# MotionDetectorCamera.net
KiCad netlist of a schematic drawn in EAGLE
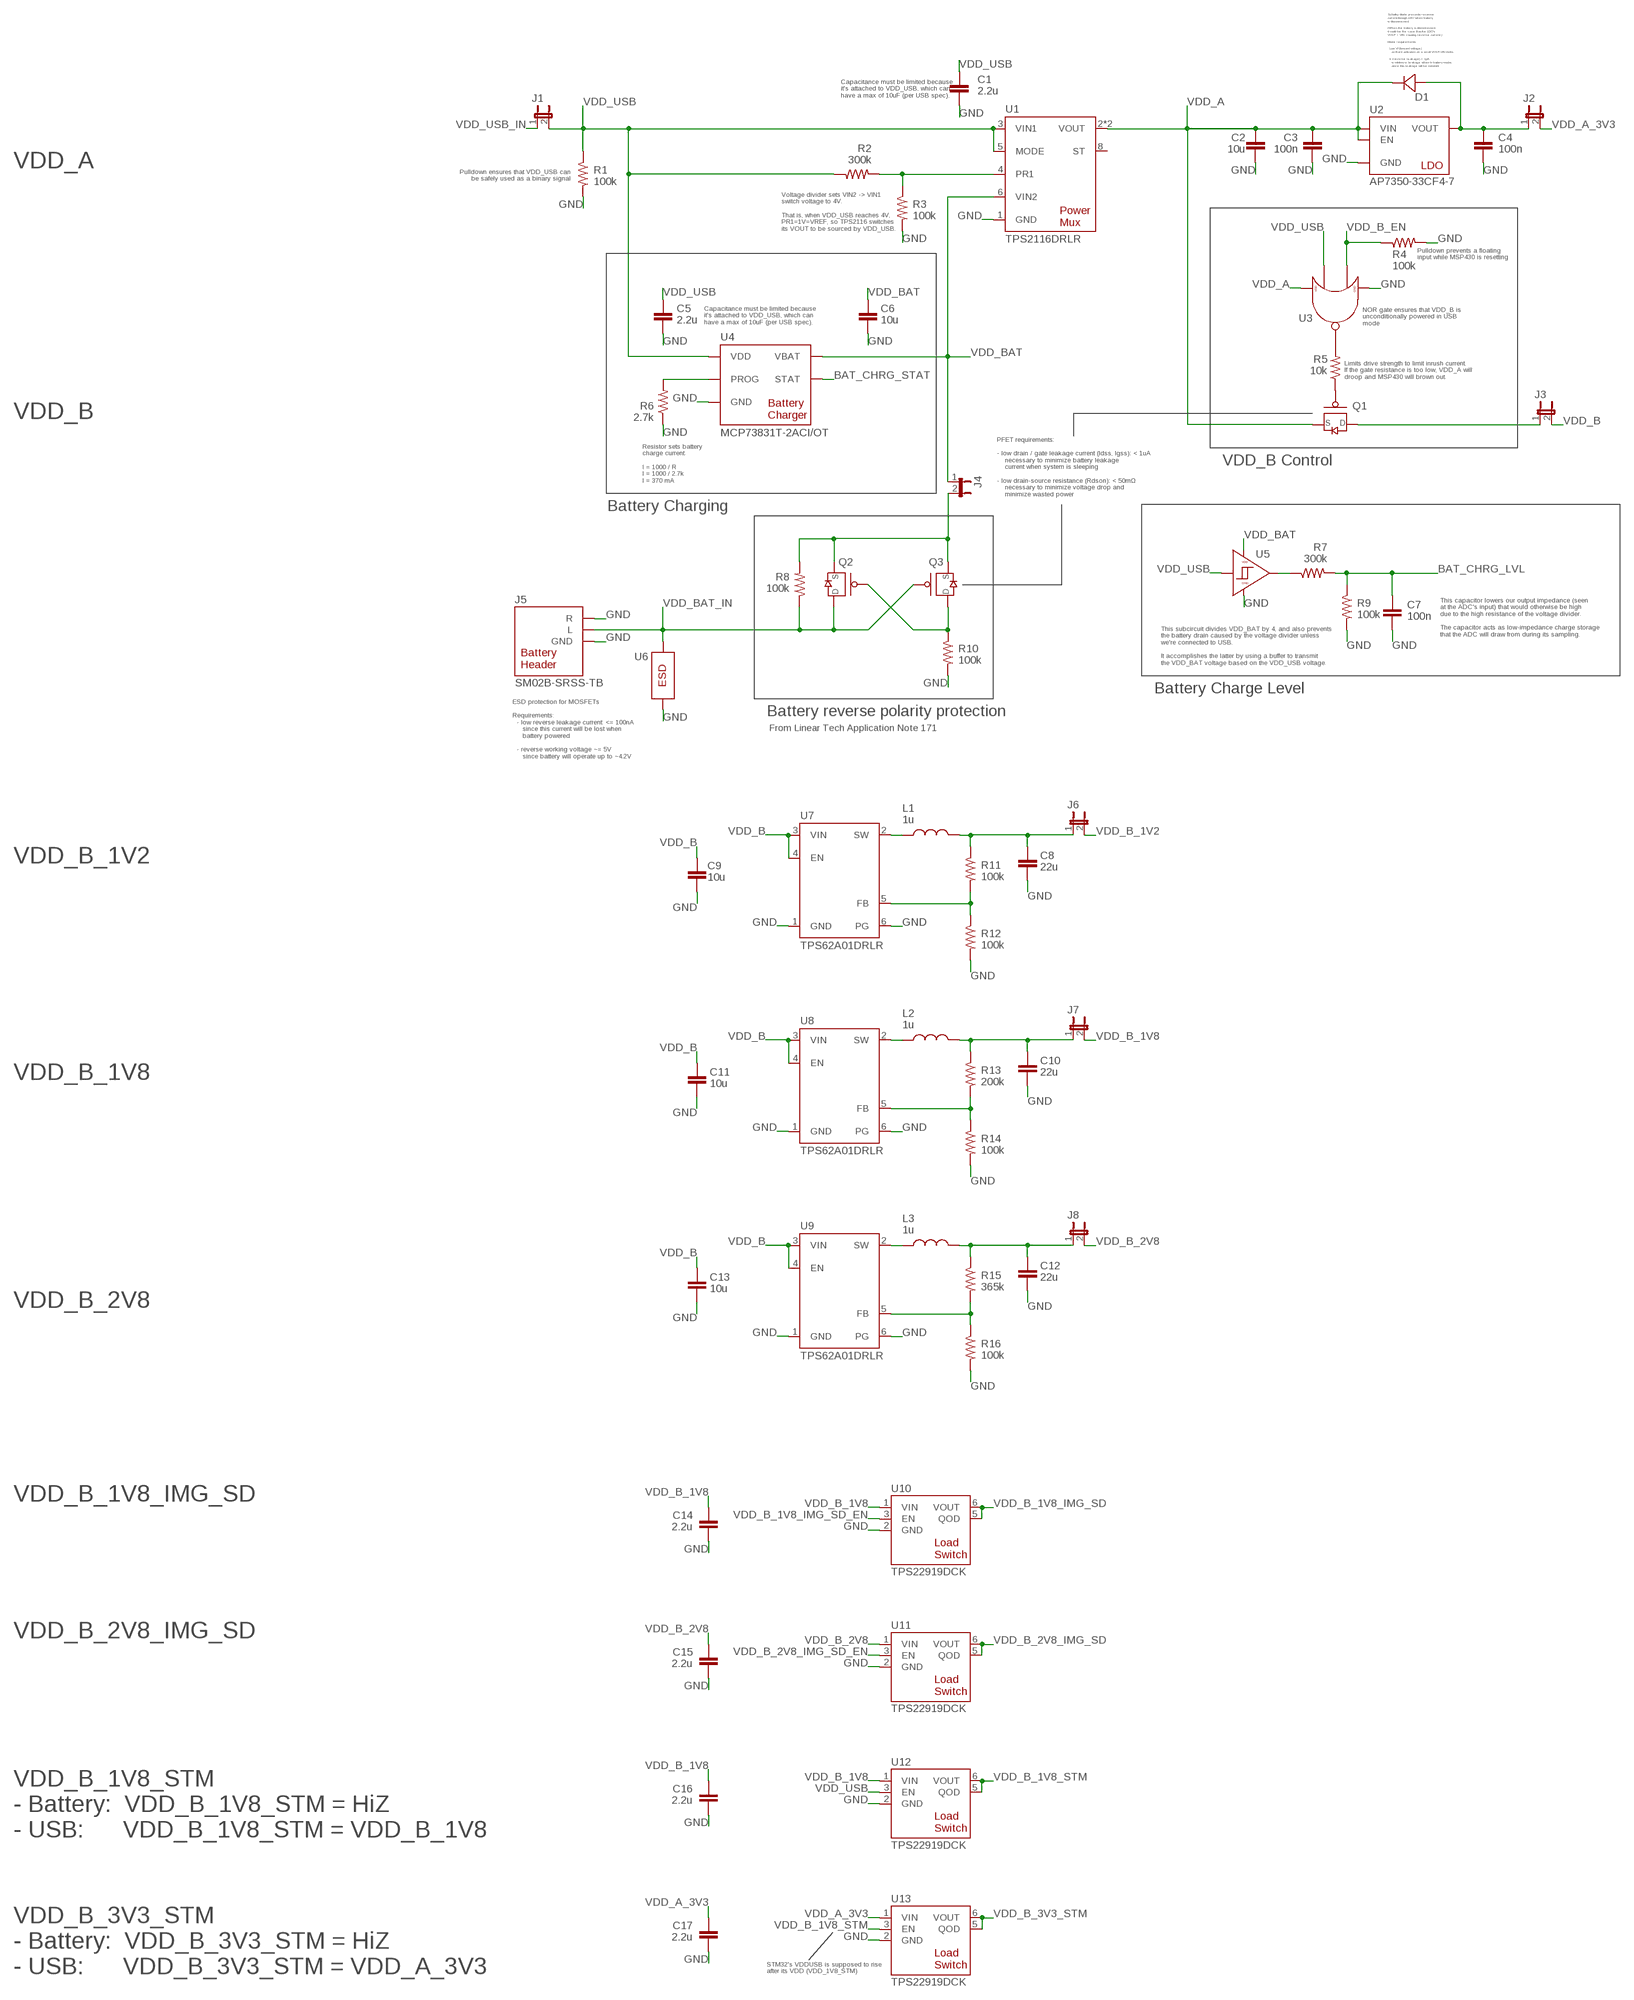
[diagram p0: schematic, sheet 1]
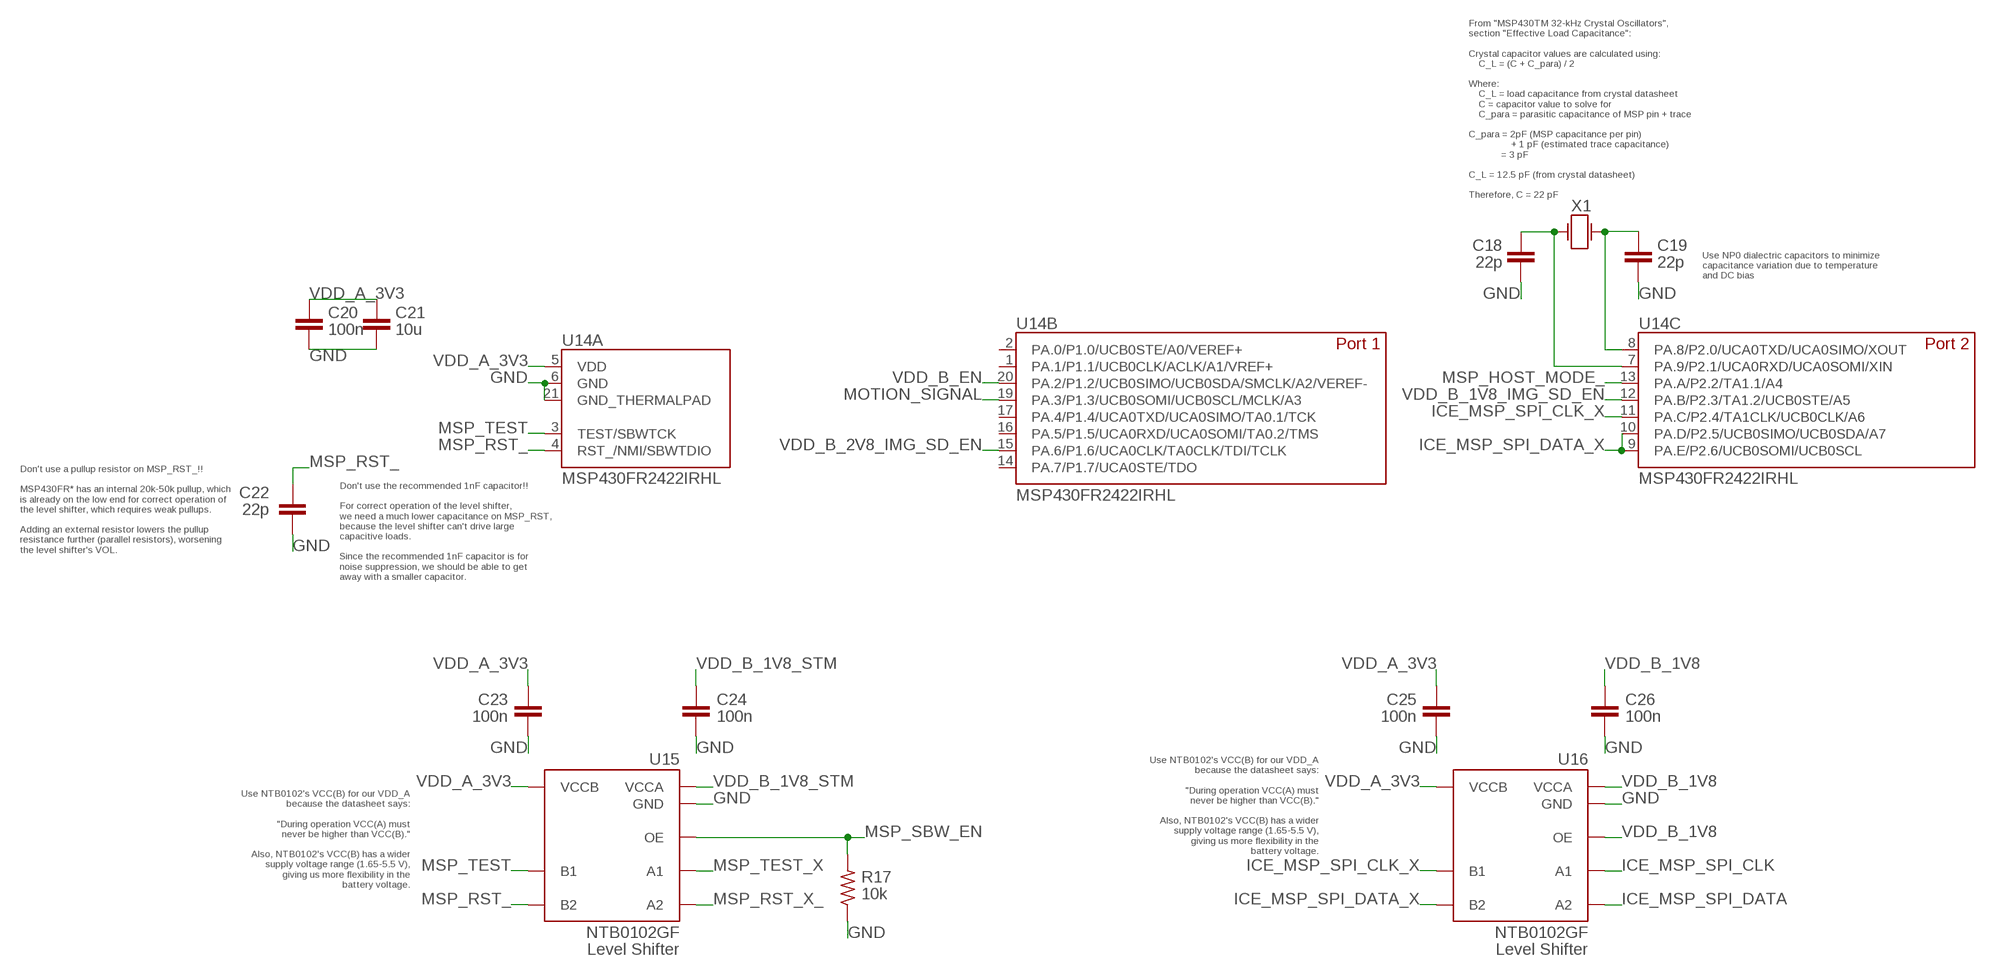
[diagram p1: schematic, sheet 2]
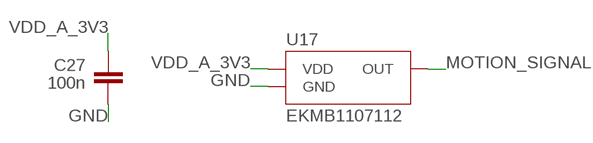
[diagram p2: schematic, sheet 3]
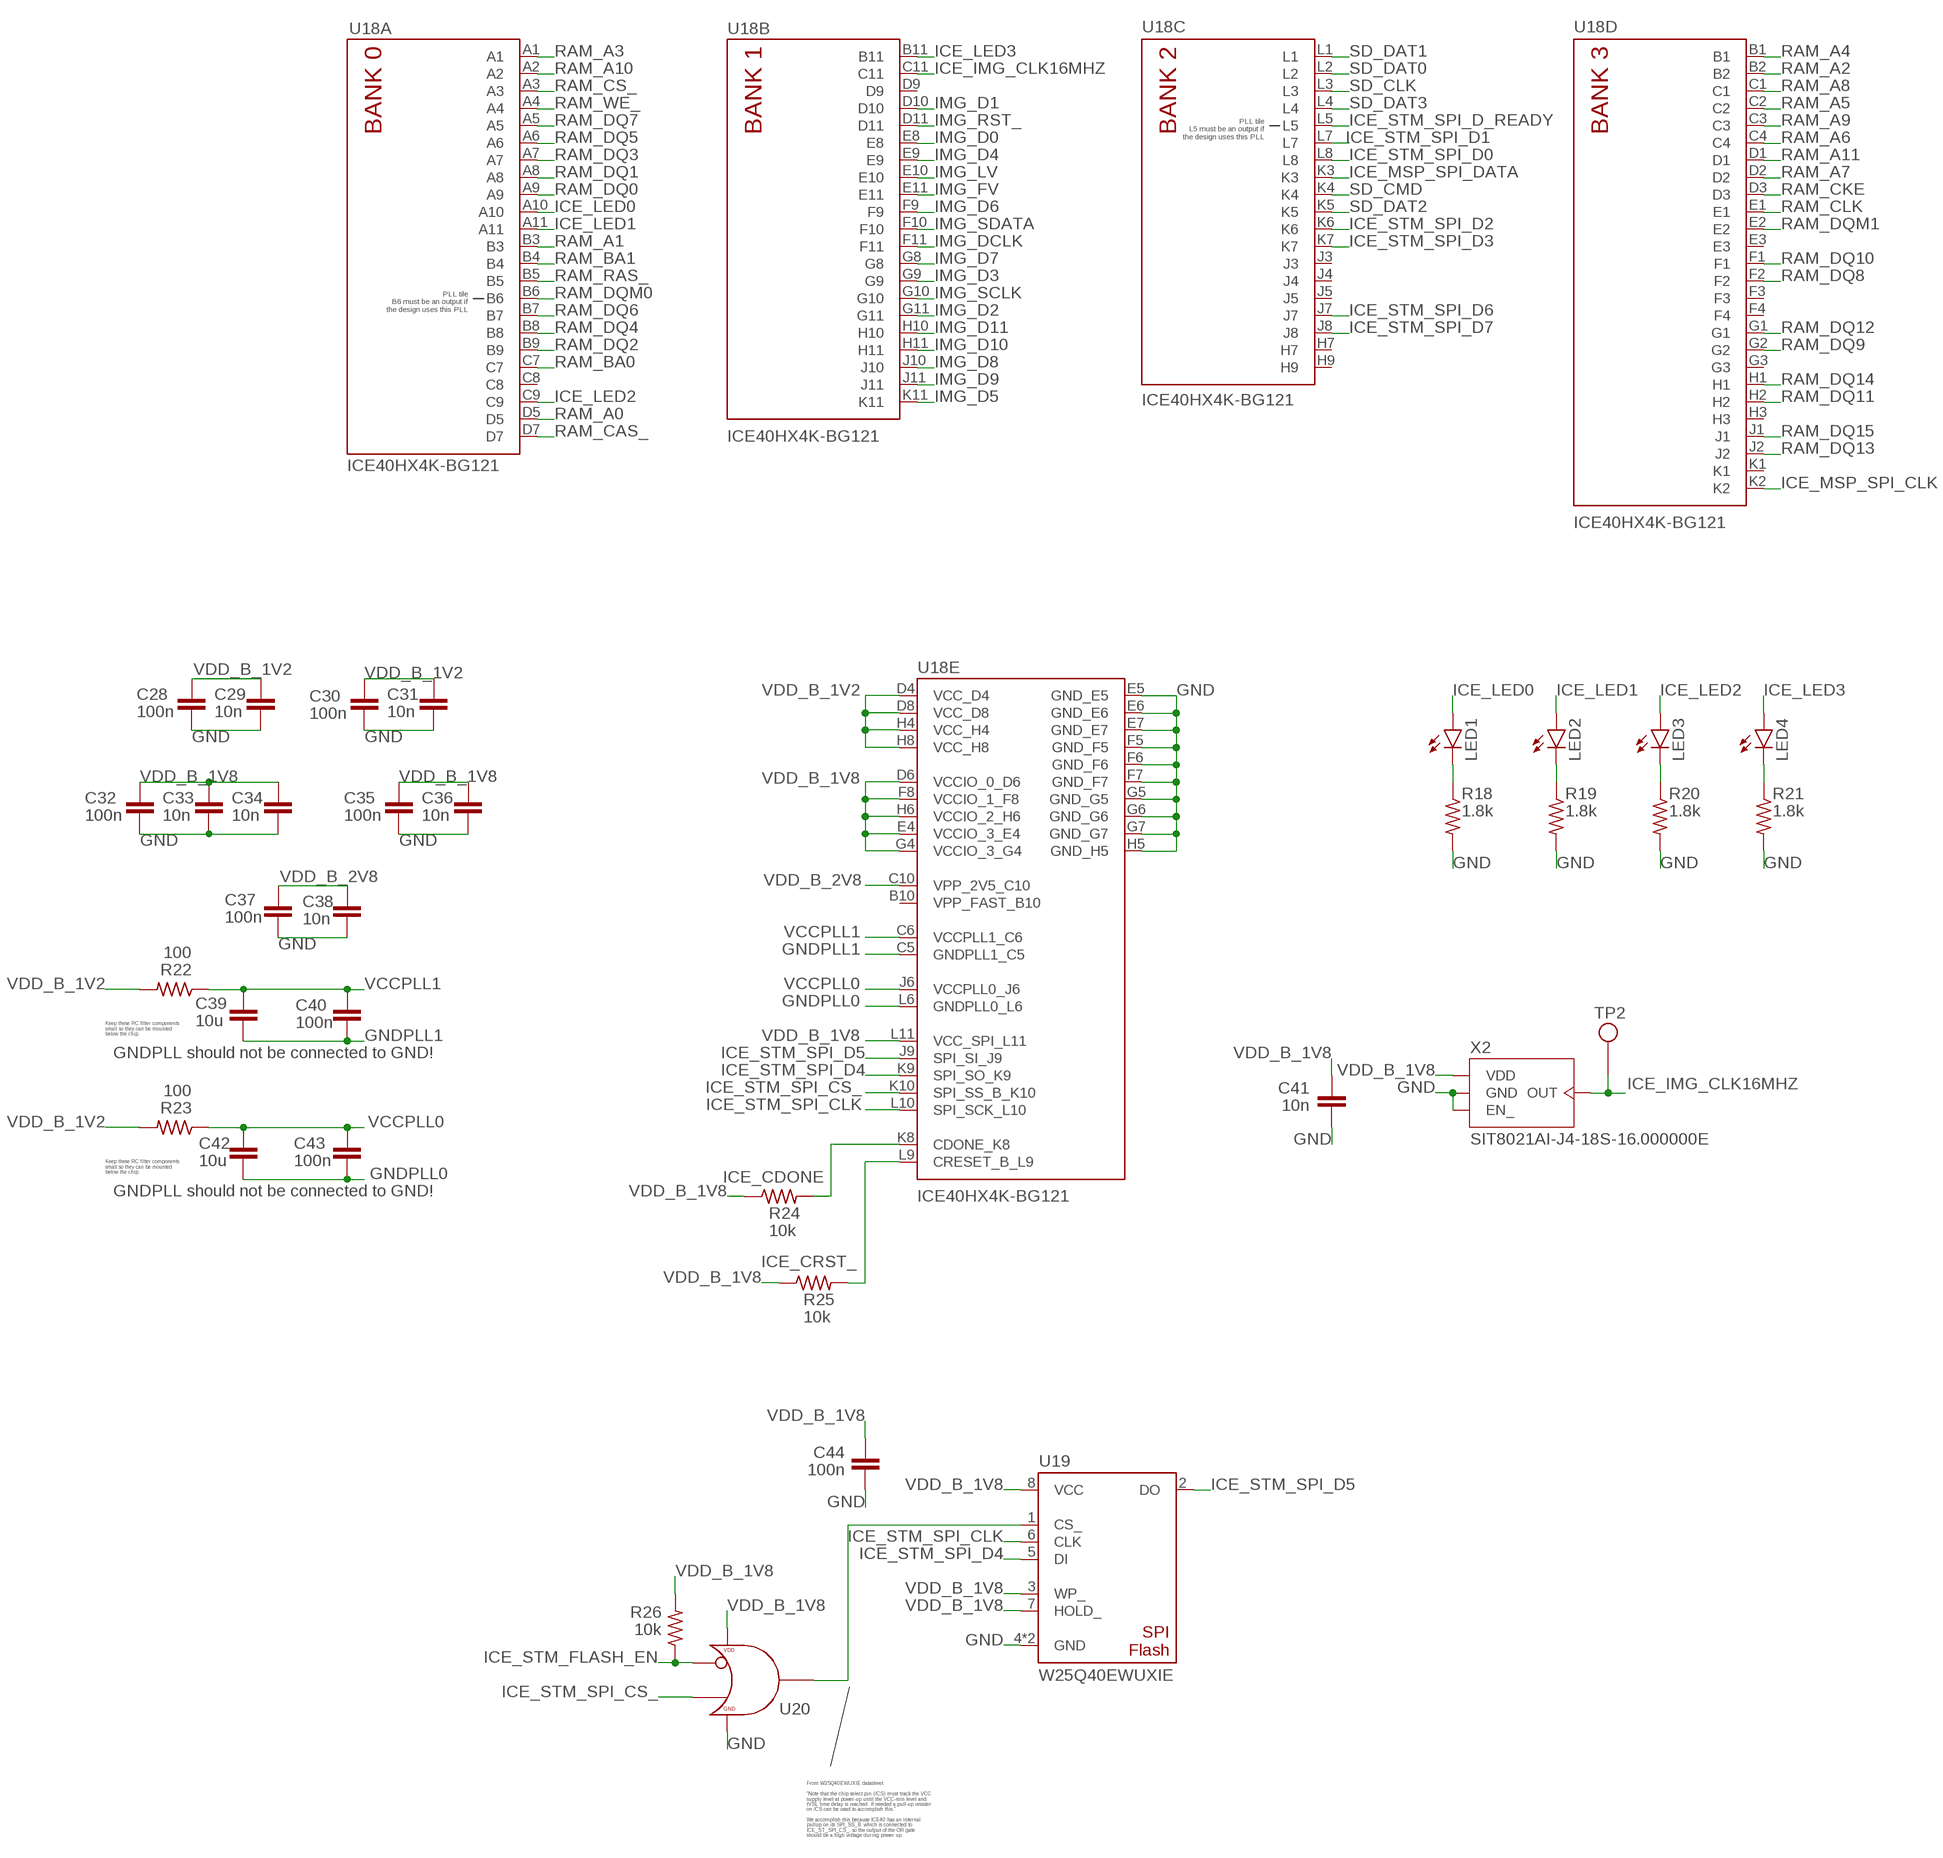
[diagram p3: schematic, sheet 4]
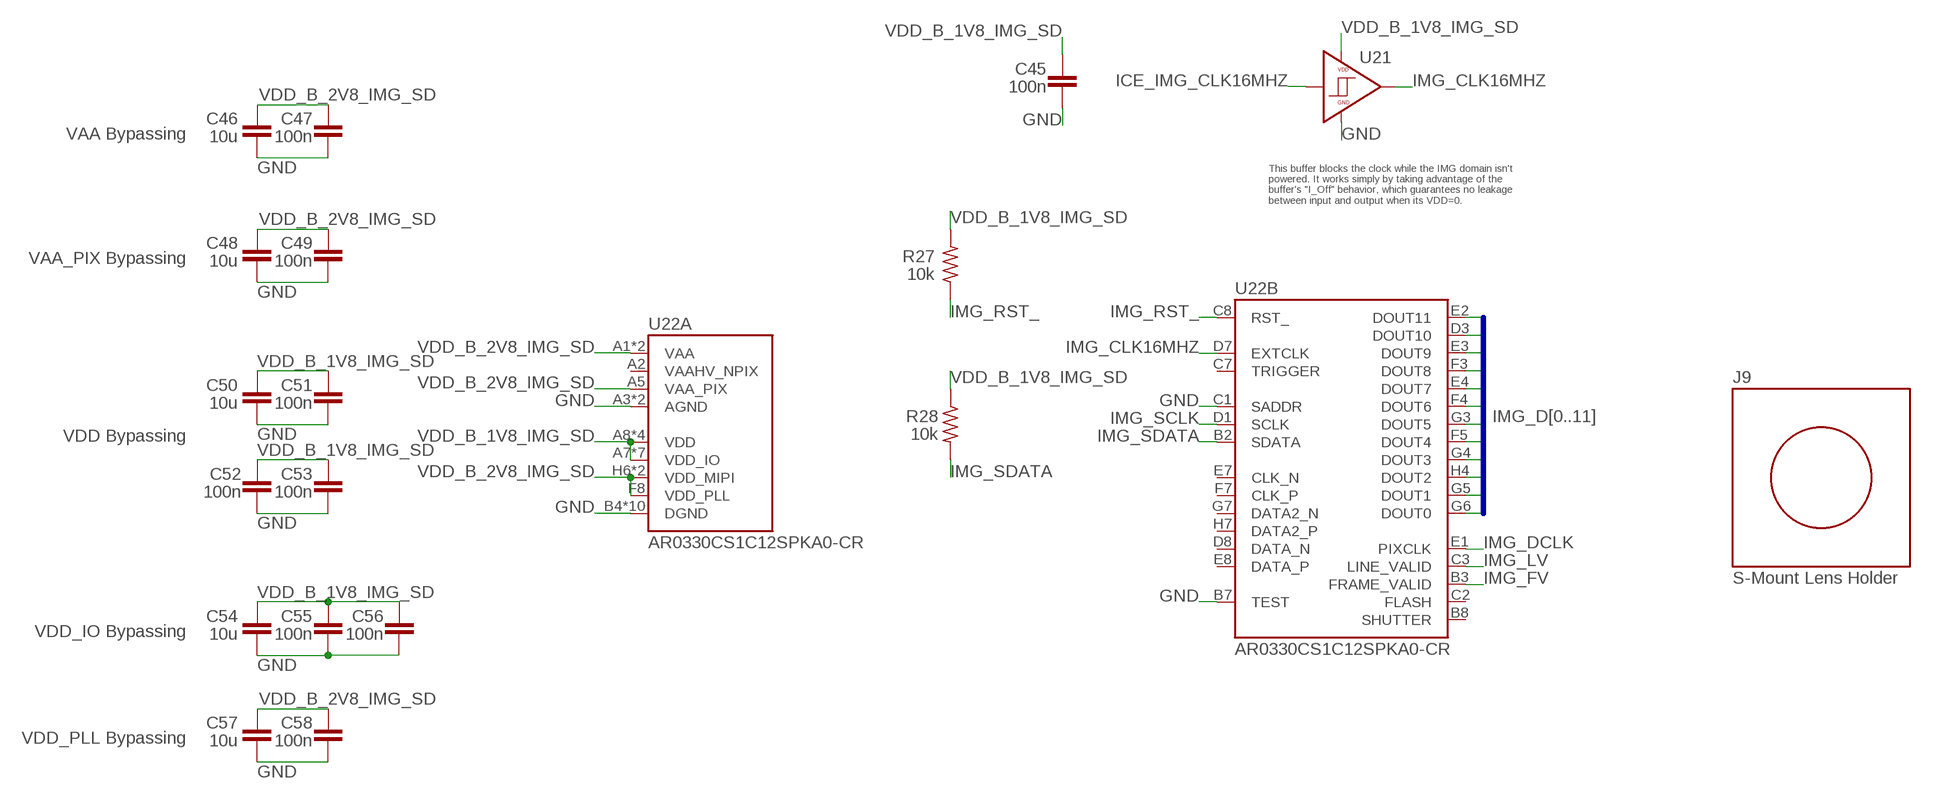
[diagram p4: schematic, sheet 5]
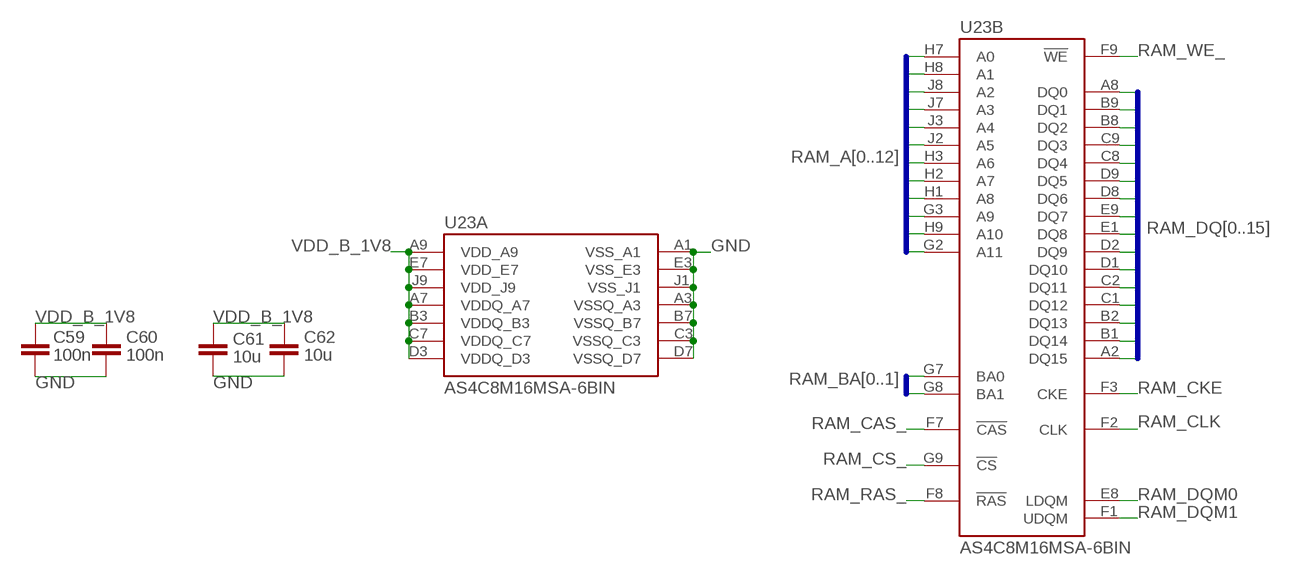
[diagram p5: schematic, sheet 6]
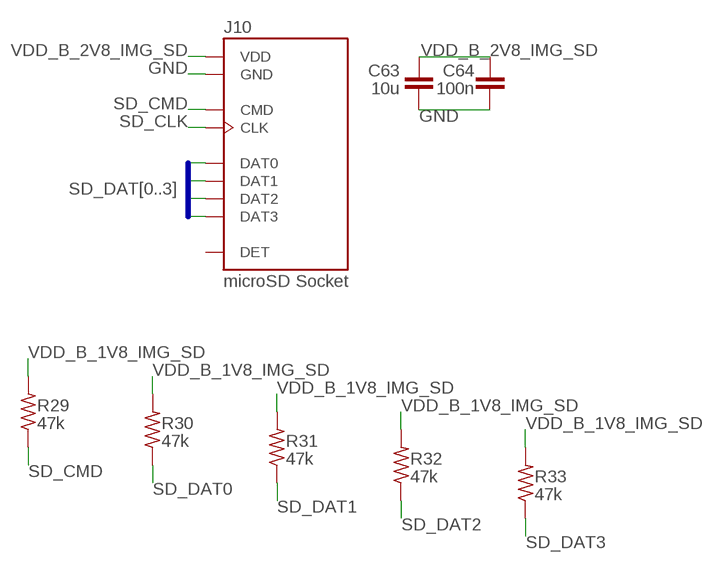
[diagram p6: schematic, sheet 7]
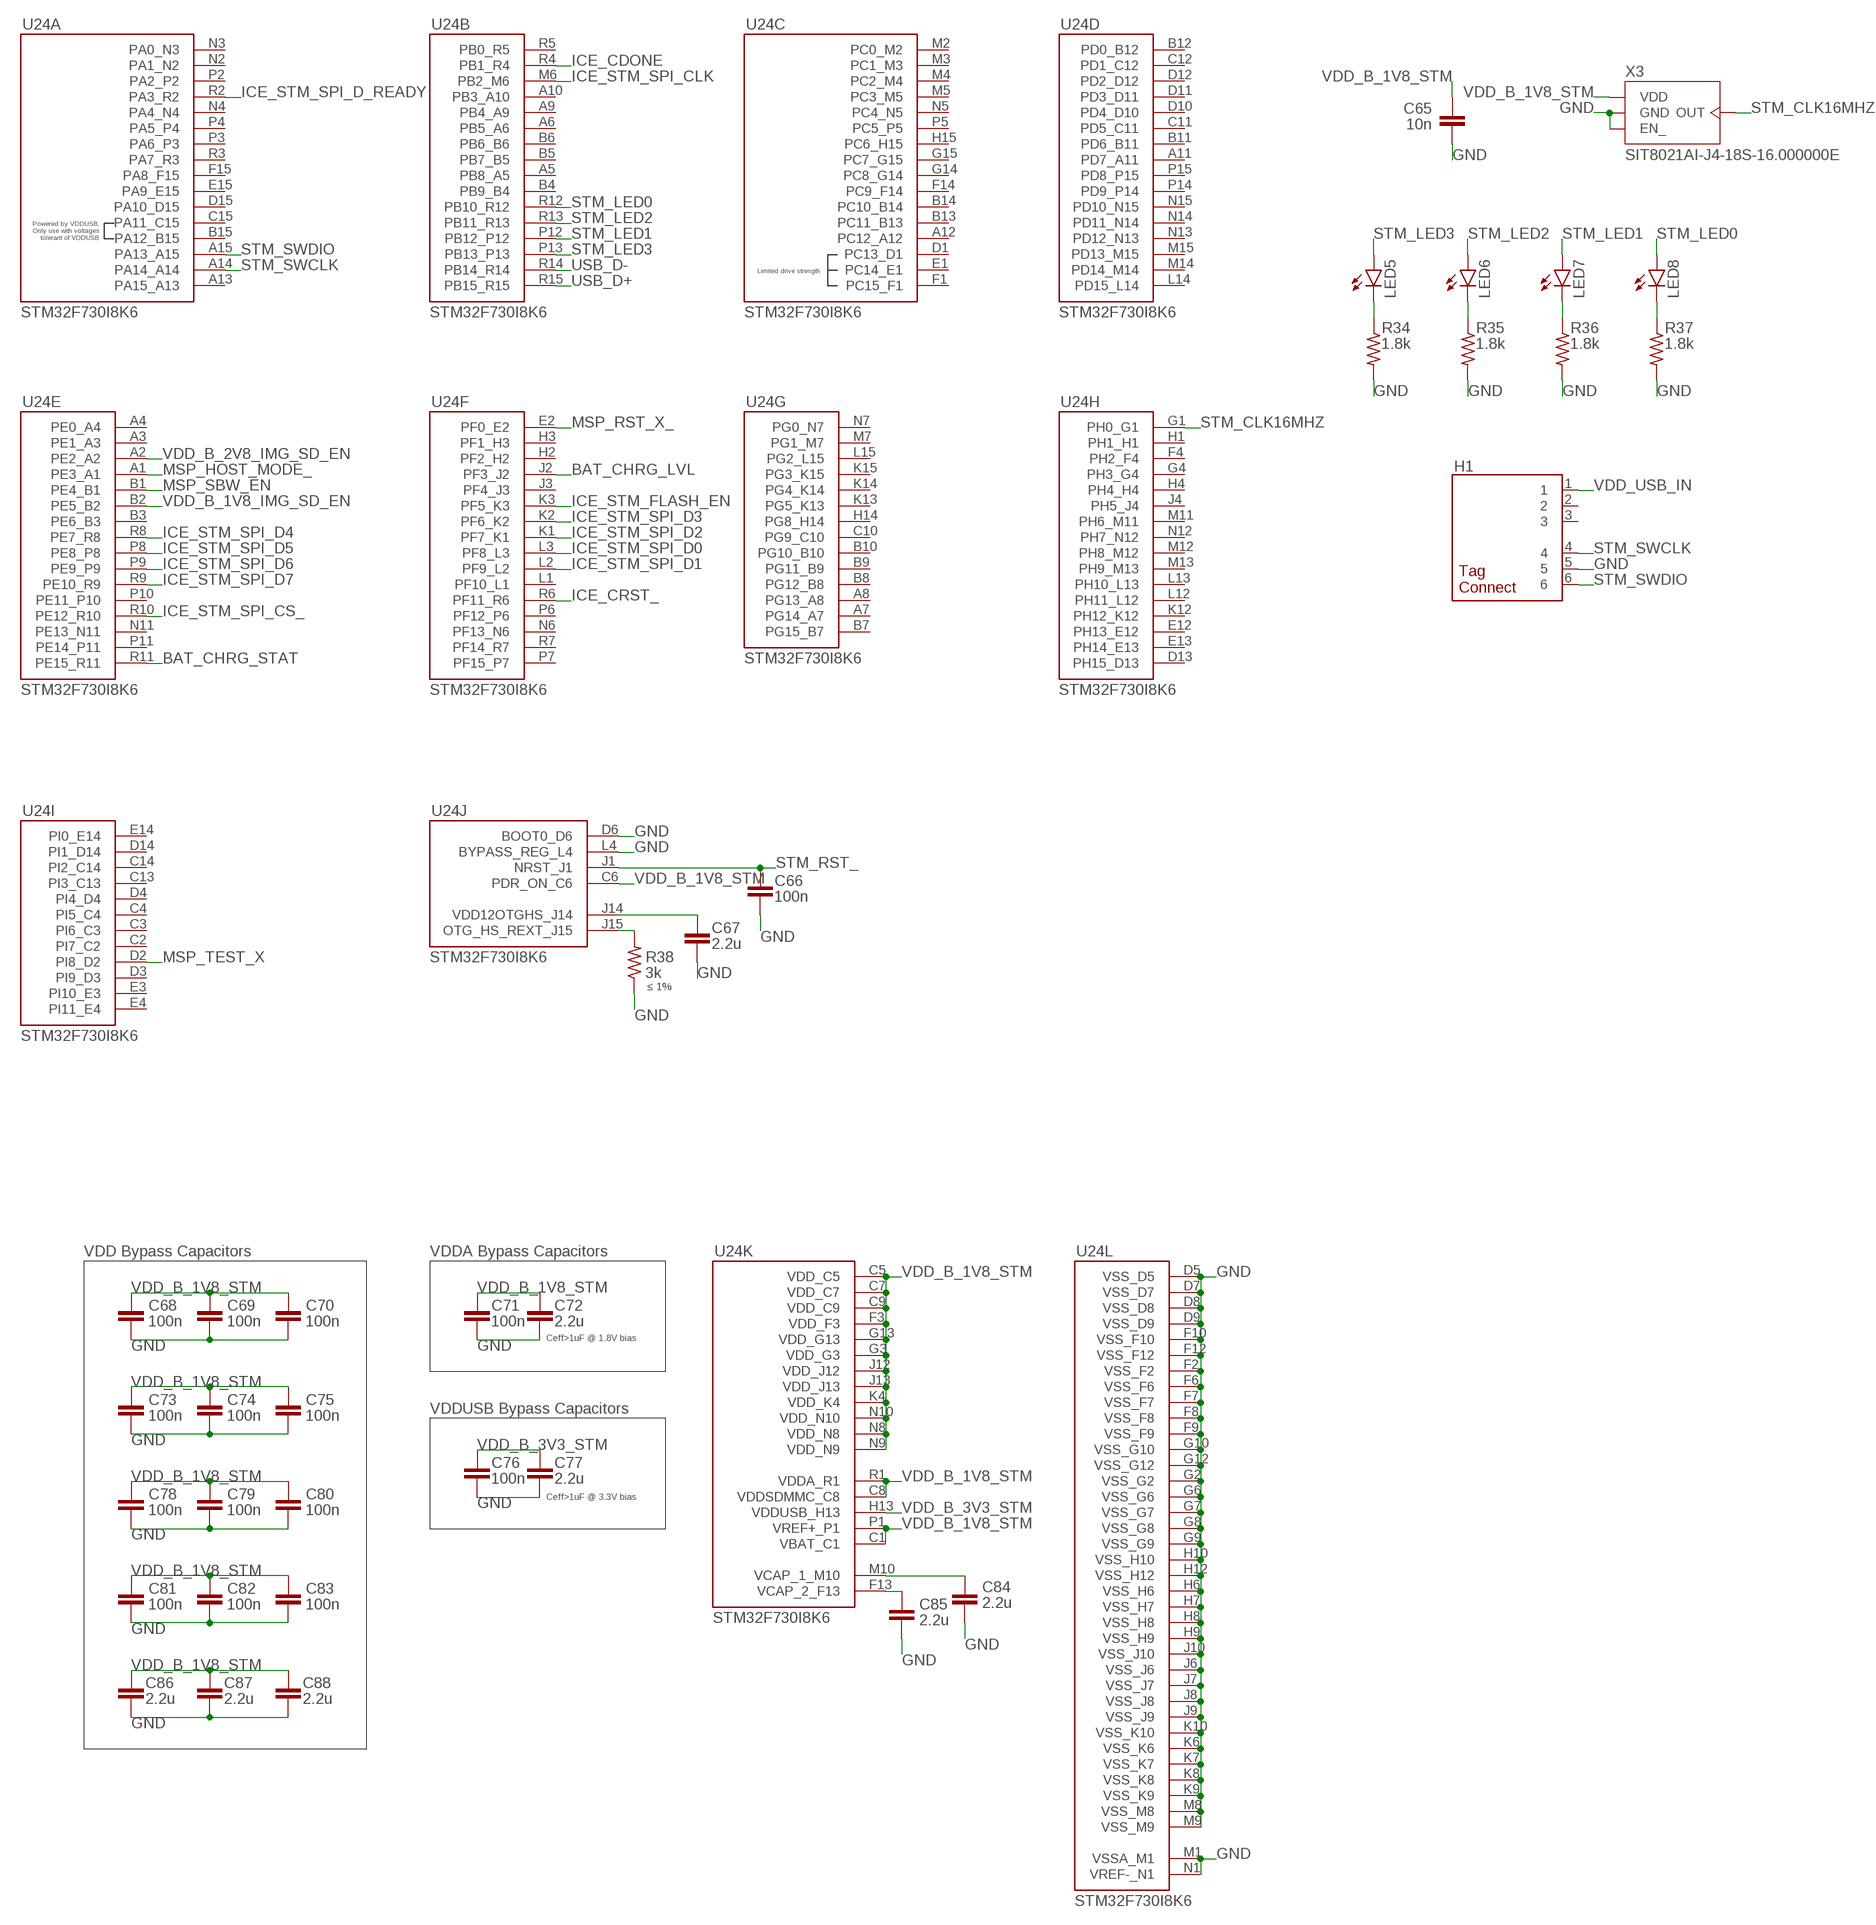
[diagram p7: schematic, sheet 8]
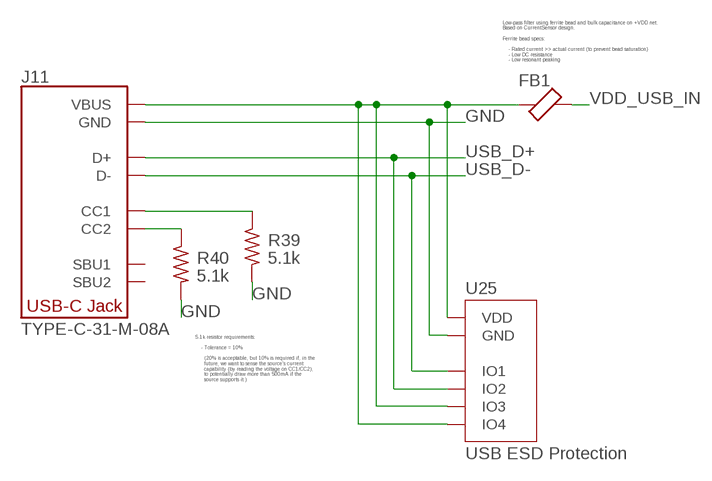
[diagram p8: schematic, sheet 9]

(export (version "E")
  (design (tool "Eeschema 10.0.6"))
  (components
    (comp (ref "C28")
      (value "100n")
      (footprint "eagle-import:0402")
      (fields (field (name "MFG") "Murata"))
      (libsource (lib "eagle-import") (part "CAPACITOR0402"))
    )
    (comp (ref "C29")
      (value "10n")
      (footprint "eagle-import:0402")
      (fields (field (name "MFG") "Samsung"))
      (libsource (lib "eagle-import") (part "CAPACITOR0402"))
    )
    (comp (ref "C30")
      (value "100n")
      (footprint "eagle-import:0402")
      (fields (field (name "MFG") "Murata"))
      (libsource (lib "eagle-import") (part "CAPACITOR0402"))
    )
    (comp (ref "C31")
      (value "10n")
      (footprint "eagle-import:0402")
      (fields (field (name "MFG") "Samsung"))
      (libsource (lib "eagle-import") (part "CAPACITOR0402"))
    )
    (comp (ref "C32")
      (value "100n")
      (footprint "eagle-import:0402")
      (fields (field (name "MFG") "Murata"))
      (libsource (lib "eagle-import") (part "CAPACITOR0402"))
    )
    (comp (ref "C33")
      (value "10n")
      (footprint "eagle-import:0402")
      (fields (field (name "MFG") "Samsung"))
      (libsource (lib "eagle-import") (part "CAPACITOR0402"))
    )
    (comp (ref "C34")
      (value "10n")
      (footprint "eagle-import:0402")
      (fields (field (name "MFG") "Samsung"))
      (libsource (lib "eagle-import") (part "CAPACITOR0402"))
    )
    (comp (ref "C35")
      (value "100n")
      (footprint "eagle-import:0402")
      (fields (field (name "MFG") "Murata"))
      (libsource (lib "eagle-import") (part "CAPACITOR0402"))
    )
    (comp (ref "C36")
      (value "10n")
      (footprint "eagle-import:0402")
      (fields (field (name "MFG") "Samsung"))
      (libsource (lib "eagle-import") (part "CAPACITOR0402"))
    )
    (comp (ref "C37")
      (value "100n")
      (footprint "eagle-import:0402")
      (fields (field (name "MFG") "Murata"))
      (libsource (lib "eagle-import") (part "CAPACITOR0402"))
    )
    (comp (ref "C38")
      (value "10n")
      (footprint "eagle-import:0402")
      (fields (field (name "MFG") "Samsung"))
      (libsource (lib "eagle-import") (part "CAPACITOR0402"))
    )
    (comp (ref "C39")
      (value "10u")
      (footprint "eagle-import:0805")
      (fields (field (name "MFG") "Samsung"))
      (libsource (lib "eagle-import") (part "CAPACITOR0805"))
    )
    (comp (ref "C40")
      (value "100n")
      (footprint "eagle-import:0402")
      (fields (field (name "MFG") "Murata"))
      (libsource (lib "eagle-import") (part "CAPACITOR0402"))
    )
    (comp (ref "C41")
      (value "10n")
      (footprint "eagle-import:0402")
      (fields (field (name "MFG") "Samsung"))
      (libsource (lib "eagle-import") (part "CAPACITOR0402"))
    )
    (comp (ref "C42")
      (value "10u")
      (footprint "eagle-import:0805")
      (fields (field (name "MFG") "Samsung"))
      (libsource (lib "eagle-import") (part "CAPACITOR0805"))
    )
    (comp (ref "C43")
      (value "100n")
      (footprint "eagle-import:0402")
      (fields (field (name "MFG") "Murata"))
      (libsource (lib "eagle-import") (part "CAPACITOR0402"))
    )
    (comp (ref "C44")
      (value "100n")
      (footprint "eagle-import:0402")
      (fields (field (name "MFG") "Murata"))
      (libsource (lib "eagle-import") (part "CAPACITOR0402"))
    )
    (comp (ref "LED1")
      (value "LED")
      (footprint "eagle-import:LED-0603")
      (fields (field (name "MFG") "OSRAM"))
      (libsource (lib "eagle-import") (part "LED"))
    )
    (comp (ref "LED2")
      (value "LED")
      (footprint "eagle-import:LED-0603")
      (fields (field (name "MFG") "OSRAM"))
      (libsource (lib "eagle-import") (part "LED"))
    )
    (comp (ref "LED3")
      (value "LED")
      (footprint "eagle-import:LED-0603")
      (fields (field (name "MFG") "OSRAM"))
      (libsource (lib "eagle-import") (part "LED"))
    )
    (comp (ref "LED4")
      (value "LED")
      (footprint "eagle-import:LED-0603")
      (fields (field (name "MFG") "OSRAM"))
      (libsource (lib "eagle-import") (part "LED"))
    )
    (comp (ref "R18")
      (value "1.8k")
      (footprint "eagle-import:0402")
      (fields (field (name "MFG") "Yageo"))
      (libsource (lib "eagle-import") (part "RESISTOR0402"))
    )
    (comp (ref "R19")
      (value "1.8k")
      (footprint "eagle-import:0402")
      (fields (field (name "MFG") "Yageo"))
      (libsource (lib "eagle-import") (part "RESISTOR0402"))
    )
    (comp (ref "R20")
      (value "1.8k")
      (footprint "eagle-import:0402")
      (fields (field (name "MFG") "Yageo"))
      (libsource (lib "eagle-import") (part "RESISTOR0402"))
    )
    (comp (ref "R21")
      (value "1.8k")
      (footprint "eagle-import:0402")
      (fields (field (name "MFG") "Yageo"))
      (libsource (lib "eagle-import") (part "RESISTOR0402"))
    )
    (comp (ref "R22")
      (value "100")
      (footprint "eagle-import:0402")
      (fields (field (name "MFG") "Walsin"))
      (libsource (lib "eagle-import") (part "RESISTOR0402"))
    )
    (comp (ref "R23")
      (value "100")
      (footprint "eagle-import:0402")
      (fields (field (name "MFG") "Walsin"))
      (libsource (lib "eagle-import") (part "RESISTOR0402"))
    )
    (comp (ref "R24")
      (value "10k")
      (footprint "eagle-import:0402")
      (fields (field (name "MFG") "Yageo"))
      (libsource (lib "eagle-import") (part "RESISTOR0402"))
    )
    (comp (ref "R25")
      (value "10k")
      (footprint "eagle-import:0402")
      (fields (field (name "MFG") "Yageo"))
      (libsource (lib "eagle-import") (part "RESISTOR0402"))
    )
    (comp (ref "R26")
      (value "10k")
      (footprint "eagle-import:0402")
      (fields (field (name "MFG") "Yageo"))
      (libsource (lib "eagle-import") (part "RESISTOR0402"))
    )
    (comp (ref "TP2")
      (value "TEST-POINT")
      (footprint "eagle-import:TEST-POINT")
      (libsource (lib "eagle-import") (part "TEST-POINT"))
    )
    (comp (ref "U18")
      (value "LATTICE-ICE40HX4K-BG121")
      (footprint "eagle-import:LATTICE-ICE40HX4K-BG121")
      (fields (field (name "MFG") "Lattice"))
      (libsource (lib "eagle-import") (part "LATTICE-ICE40HX4K-BG121"))
    )
    (comp (ref "U19")
      (value "WINBOND-W25Q40EW")
      (footprint "eagle-import:WINBOND-W25Q40EWUXIE")
      (fields (field (name "MFG") "Winbond") (field (name "PN") "W25Q40EWUXIE"))
      (libsource (lib "eagle-import") (part "WINBOND-W25Q40EW"))
    )
    (comp (ref "U20")
      (value "NEXPERIA-74LVC1G98-OR-INV-INPUT")
      (footprint "eagle-import:NEXPERIA-SOT363")
      (fields (field (name "MFG") "Nexperia"))
      (libsource (lib "eagle-import") (part "NEXPERIA-74LVC1G98-OR-INV-INPUT"))
    )
    (comp (ref "X2")
      (value "SITIME-SIT8021")
      (footprint "eagle-import:SITIME-SIT8021")
      (fields (field (name "MFG") "SiTime") (field (name "PN") "SIT8021AI-J4-18S-16.000000E"))
      (libsource (lib "eagle-import") (part "SITIME-SIT8021"))
    )
    (comp (ref "C59")
      (value "100n")
      (footprint "eagle-import:0402")
      (fields (field (name "MFG") "Murata"))
      (libsource (lib "eagle-import") (part "CAPACITOR0402"))
    )
    (comp (ref "C60")
      (value "100n")
      (footprint "eagle-import:0402")
      (fields (field (name "MFG") "Murata"))
      (libsource (lib "eagle-import") (part "CAPACITOR0402"))
    )
    (comp (ref "C61")
      (value "10u")
      (footprint "eagle-import:0805")
      (fields (field (name "MFG") "Samsung"))
      (libsource (lib "eagle-import") (part "CAPACITOR0805"))
    )
    (comp (ref "C62")
      (value "10u")
      (footprint "eagle-import:0805")
      (fields (field (name "MFG") "Samsung"))
      (libsource (lib "eagle-import") (part "CAPACITOR0805"))
    )
    (comp (ref "U23")
      (value "ALLIANCE-AS4C8M16MSA-6BIN")
      (footprint "eagle-import:ALLIANCE-AS4C8M16MSA-6BIN")
      (fields (field (name "PN") "AS4C8M16MSA-6BIN") (field (name "MFG") "Alliance Memory"))
      (libsource (lib "eagle-import") (part "ALLIANCE-AS4C8M16MSA-6BIN"))
    )
    (comp (ref "C1")
      (value "2.2u")
      (footprint "eagle-import:0402")
      (fields (field (name "MFG") "Taiyo Yuden"))
      (libsource (lib "eagle-import") (part "CAPACITOR0402"))
    )
    (comp (ref "C2")
      (value "10u")
      (footprint "eagle-import:0805")
      (fields (field (name "MFG") "Samsung"))
      (libsource (lib "eagle-import") (part "CAPACITOR0805"))
    )
    (comp (ref "C3")
      (value "100n")
      (footprint "eagle-import:0402")
      (fields (field (name "MFG") "Murata"))
      (libsource (lib "eagle-import") (part "CAPACITOR0402"))
    )
    (comp (ref "C4")
      (value "100n")
      (footprint "eagle-import:0402")
      (fields (field (name "MFG") "Murata"))
      (libsource (lib "eagle-import") (part "CAPACITOR0402"))
    )
    (comp (ref "C5")
      (value "2.2u")
      (footprint "eagle-import:0402")
      (fields (field (name "MFG") "Taiyo Yuden"))
      (libsource (lib "eagle-import") (part "CAPACITOR0402"))
    )
    (comp (ref "C6")
      (value "10u")
      (footprint "eagle-import:0805")
      (fields (field (name "MFG") "Samsung"))
      (libsource (lib "eagle-import") (part "CAPACITOR0805"))
    )
    (comp (ref "C7")
      (value "100n")
      (footprint "eagle-import:0402")
      (fields (field (name "MFG") "Murata"))
      (libsource (lib "eagle-import") (part "CAPACITOR0402"))
    )
    (comp (ref "C8")
      (value "22u")
      (footprint "eagle-import:0805")
      (fields (field (name "MFG") "Samsung"))
      (libsource (lib "eagle-import") (part "CAPACITOR0805"))
    )
    (comp (ref "C9")
      (value "10u")
      (footprint "eagle-import:0805")
      (fields (field (name "MFG") "Samsung"))
      (libsource (lib "eagle-import") (part "CAPACITOR0805"))
    )
    (comp (ref "C10")
      (value "22u")
      (footprint "eagle-import:0805")
      (fields (field (name "MFG") "Samsung"))
      (libsource (lib "eagle-import") (part "CAPACITOR0805"))
    )
    (comp (ref "C11")
      (value "10u")
      (footprint "eagle-import:0805")
      (fields (field (name "MFG") "Samsung"))
      (libsource (lib "eagle-import") (part "CAPACITOR0805"))
    )
    (comp (ref "C12")
      (value "22u")
      (footprint "eagle-import:0805")
      (fields (field (name "MFG") "Samsung"))
      (libsource (lib "eagle-import") (part "CAPACITOR0805"))
    )
    (comp (ref "C13")
      (value "10u")
      (footprint "eagle-import:0805")
      (fields (field (name "MFG") "Samsung"))
      (libsource (lib "eagle-import") (part "CAPACITOR0805"))
    )
    (comp (ref "C14")
      (value "2.2u")
      (footprint "eagle-import:0402")
      (fields (field (name "MFG") "Taiyo Yuden"))
      (libsource (lib "eagle-import") (part "CAPACITOR0402"))
    )
    (comp (ref "C15")
      (value "2.2u")
      (footprint "eagle-import:0402")
      (fields (field (name "MFG") "Taiyo Yuden"))
      (libsource (lib "eagle-import") (part "CAPACITOR0402"))
    )
    (comp (ref "C16")
      (value "2.2u")
      (footprint "eagle-import:0402")
      (fields (field (name "MFG") "Taiyo Yuden"))
      (libsource (lib "eagle-import") (part "CAPACITOR0402"))
    )
    (comp (ref "C17")
      (value "2.2u")
      (footprint "eagle-import:0402")
      (fields (field (name "MFG") "Taiyo Yuden"))
      (libsource (lib "eagle-import") (part "CAPACITOR0402"))
    )
    (comp (ref "D1")
      (value "ROHM-RB168MM-40")
      (footprint "eagle-import:ROHM-SOD-123FL")
      (fields (field (name "MFG") "ROHM"))
      (libsource (lib "eagle-import") (part "ROHM-RB168MM-40"))
    )
    (comp (ref "J1")
      (value "JUMPER-SOLDER")
      (footprint "eagle-import:JUMPER-SOLDER")
      (libsource (lib "eagle-import") (part "JUMPER-SOLDER"))
    )
    (comp (ref "J2")
      (value "JUMPER-SOLDER")
      (footprint "eagle-import:JUMPER-SOLDER")
      (libsource (lib "eagle-import") (part "JUMPER-SOLDER"))
    )
    (comp (ref "J3")
      (value "JUMPER-SOLDER")
      (footprint "eagle-import:JUMPER-SOLDER")
      (libsource (lib "eagle-import") (part "JUMPER-SOLDER"))
    )
    (comp (ref "J4")
      (value "JUMPER-SOLDER")
      (footprint "eagle-import:JUMPER-SOLDER")
      (libsource (lib "eagle-import") (part "JUMPER-SOLDER"))
    )
    (comp (ref "J5")
      (value "JST-SM02B-SRSS-TB")
      (footprint "eagle-import:JST-SM02B-SRSS-TB")
      (fields (field (name "PN") "SM02B-SRSS-TB") (field (name "MFG") "JST"))
      (libsource (lib "eagle-import") (part "JST-SM02B-SRSS-TB"))
    )
    (comp (ref "J6")
      (value "JUMPER-SOLDER")
      (footprint "eagle-import:JUMPER-SOLDER")
      (libsource (lib "eagle-import") (part "JUMPER-SOLDER"))
    )
    (comp (ref "J7")
      (value "JUMPER-SOLDER")
      (footprint "eagle-import:JUMPER-SOLDER")
      (libsource (lib "eagle-import") (part "JUMPER-SOLDER"))
    )
    (comp (ref "J8")
      (value "JUMPER-SOLDER")
      (footprint "eagle-import:JUMPER-SOLDER")
      (libsource (lib "eagle-import") (part "JUMPER-SOLDER"))
    )
    (comp (ref "L1")
      (value "1u")
      (footprint "eagle-import:0806")
      (fields (field (name "MFG") "Samsung"))
      (libsource (lib "eagle-import") (part "INDUCTOR0806"))
    )
    (comp (ref "L2")
      (value "1u")
      (footprint "eagle-import:0806")
      (fields (field (name "MFG") "Samsung"))
      (libsource (lib "eagle-import") (part "INDUCTOR0806"))
    )
    (comp (ref "L3")
      (value "1u")
      (footprint "eagle-import:0806")
      (fields (field (name "MFG") "Samsung"))
      (libsource (lib "eagle-import") (part "INDUCTOR0806"))
    )
    (comp (ref "Q1")
      (value "PMOS-NEXPERIA-SOT1220")
      (footprint "eagle-import:NEXPERIA-SOT1220")
      (fields (field (name "MFG") "Nexperia"))
      (libsource (lib "eagle-import") (part "PMOS-NEXPERIA-SOT1220"))
    )
    (comp (ref "Q2")
      (value "PMOS-NEXPERIA-SOT1220")
      (footprint "eagle-import:NEXPERIA-SOT1220")
      (fields (field (name "MFG") "Nexperia"))
      (libsource (lib "eagle-import") (part "PMOS-NEXPERIA-SOT1220"))
    )
    (comp (ref "Q3")
      (value "PMOS-NEXPERIA-SOT1220")
      (footprint "eagle-import:NEXPERIA-SOT1220")
      (fields (field (name "MFG") "Nexperia"))
      (libsource (lib "eagle-import") (part "PMOS-NEXPERIA-SOT1220"))
    )
    (comp (ref "R1")
      (value "100k")
      (footprint "eagle-import:0402")
      (fields (field (name "MFG") "Yageo"))
      (libsource (lib "eagle-import") (part "RESISTOR0402"))
    )
    (comp (ref "R2")
      (value "300k")
      (footprint "eagle-import:0402")
      (fields (field (name "MFG") "Walsin"))
      (libsource (lib "eagle-import") (part "RESISTOR0402"))
    )
    (comp (ref "R3")
      (value "100k")
      (footprint "eagle-import:0402")
      (fields (field (name "MFG") "Yageo"))
      (libsource (lib "eagle-import") (part "RESISTOR0402"))
    )
    (comp (ref "R4")
      (value "100k")
      (footprint "eagle-import:0402")
      (fields (field (name "MFG") "Yageo"))
      (libsource (lib "eagle-import") (part "RESISTOR0402"))
    )
    (comp (ref "R5")
      (value "10k")
      (footprint "eagle-import:0402")
      (fields (field (name "MFG") "Yageo"))
      (libsource (lib "eagle-import") (part "RESISTOR0402"))
    )
    (comp (ref "R6")
      (value "2.7k")
      (footprint "eagle-import:0402")
      (fields (field (name "MFG") "Bourns"))
      (libsource (lib "eagle-import") (part "RESISTOR0402"))
    )
    (comp (ref "R7")
      (value "300k")
      (footprint "eagle-import:0402")
      (fields (field (name "MFG") "Walsin"))
      (libsource (lib "eagle-import") (part "RESISTOR0402"))
    )
    (comp (ref "R8")
      (value "100k")
      (footprint "eagle-import:0402")
      (fields (field (name "MFG") "Yageo"))
      (libsource (lib "eagle-import") (part "RESISTOR0402"))
    )
    (comp (ref "R9")
      (value "100k")
      (footprint "eagle-import:0402")
      (fields (field (name "MFG") "Yageo"))
      (libsource (lib "eagle-import") (part "RESISTOR0402"))
    )
    (comp (ref "R10")
      (value "100k")
      (footprint "eagle-import:0402")
      (fields (field (name "MFG") "Yageo"))
      (libsource (lib "eagle-import") (part "RESISTOR0402"))
    )
    (comp (ref "R11")
      (value "100k")
      (footprint "eagle-import:0402")
      (fields (field (name "MFG") "Yageo"))
      (libsource (lib "eagle-import") (part "RESISTOR0402"))
    )
    (comp (ref "R12")
      (value "100k")
      (footprint "eagle-import:0402")
      (fields (field (name "MFG") "Yageo"))
      (libsource (lib "eagle-import") (part "RESISTOR0402"))
    )
    (comp (ref "R13")
      (value "200k")
      (footprint "eagle-import:0402")
      (fields (field (name "MFG") "Yageo"))
      (libsource (lib "eagle-import") (part "RESISTOR0402"))
    )
    (comp (ref "R14")
      (value "100k")
      (footprint "eagle-import:0402")
      (fields (field (name "MFG") "Yageo"))
      (libsource (lib "eagle-import") (part "RESISTOR0402"))
    )
    (comp (ref "R15")
      (value "365k")
      (footprint "eagle-import:0402")
      (fields (field (name "MFG") "Walsin"))
      (libsource (lib "eagle-import") (part "RESISTOR0402"))
    )
    (comp (ref "R16")
      (value "100k")
      (footprint "eagle-import:0402")
      (fields (field (name "MFG") "Yageo"))
      (libsource (lib "eagle-import") (part "RESISTOR0402"))
    )
    (comp (ref "U1")
      (value "TI-TPS2116")
      (footprint "eagle-import:TI-TPS2116DRLR")
      (fields (field (name "MFG") "Texas Instruments") (field (name "PN") "TPS2116DRLR"))
      (libsource (lib "eagle-import") (part "TI-TPS2116"))
    )
    (comp (ref "U2")
      (value "DIODESINC-AP7350")
      (footprint "eagle-import:DIODESINC-AP7350")
      (fields (field (name "MFG") "Diodes Incorporated") (field (name "PN") "AP7350-33CF4-7"))
      (libsource (lib "eagle-import") (part "DIODESINC-AP7350"))
    )
    (comp (ref "U3")
      (value "NEXPERIA-74LVC1G98-NOR")
      (footprint "eagle-import:NEXPERIA-SOT363")
      (fields (field (name "MFG") "Nexperia"))
      (libsource (lib "eagle-import") (part "NEXPERIA-74LVC1G98-NOR"))
    )
    (comp (ref "U4")
      (value "MICROCHIP-MCP7383X")
      (footprint "eagle-import:MICROCHIP-MIC550X-SOT23-5")
      (fields (field (name "MFG") "Microchip") (field (name "PN") "MCP73831T-2ACI/OT"))
      (libsource (lib "eagle-import") (part "MICROCHIP-MCP7383X"))
    )
    (comp (ref "U5")
      (value "NEXPERIA-74LVC1G98-BUFFER")
      (footprint "eagle-import:NEXPERIA-SOT363")
      (fields (field (name "MFG") "Nexperia"))
      (libsource (lib "eagle-import") (part "NEXPERIA-74LVC1G98-BUFFER"))
    )
    (comp (ref "U6")
      (value "EATON-STN101")
      (footprint "eagle-import:EATON-STN101")
      (fields (field (name "MFG") "Eaton"))
      (libsource (lib "eagle-import") (part "EATON-STN101"))
    )
    (comp (ref "U7")
      (value "TI-TPS62A01")
      (footprint "eagle-import:TI-TPS62A01DRLR")
      (fields (field (name "PN") "TPS62A01DRLR") (field (name "MFG") "Texas Instruments"))
      (libsource (lib "eagle-import") (part "TI-TPS62A01"))
    )
    (comp (ref "U8")
      (value "TI-TPS62A01")
      (footprint "eagle-import:TI-TPS62A01DRLR")
      (fields (field (name "PN") "TPS62A01DRLR") (field (name "MFG") "Texas Instruments"))
      (libsource (lib "eagle-import") (part "TI-TPS62A01"))
    )
    (comp (ref "U9")
      (value "TI-TPS62A01")
      (footprint "eagle-import:TI-TPS62A01DRLR")
      (fields (field (name "PN") "TPS62A01DRLR") (field (name "MFG") "Texas Instruments"))
      (libsource (lib "eagle-import") (part "TI-TPS62A01"))
    )
    (comp (ref "U10")
      (value "TI-TPS22919DCK")
      (footprint "eagle-import:TI-TPS22919DCK")
      (fields (field (name "PN") "TPS22919DCK") (field (name "MFG") "Texas Instruments"))
      (libsource (lib "eagle-import") (part "TI-TPS22919DCK"))
    )
    (comp (ref "U11")
      (value "TI-TPS22919DCK")
      (footprint "eagle-import:TI-TPS22919DCK")
      (fields (field (name "PN") "TPS22919DCK") (field (name "MFG") "Texas Instruments"))
      (libsource (lib "eagle-import") (part "TI-TPS22919DCK"))
    )
    (comp (ref "U12")
      (value "TI-TPS22919DCK")
      (footprint "eagle-import:TI-TPS22919DCK")
      (fields (field (name "PN") "TPS22919DCK") (field (name "MFG") "Texas Instruments"))
      (libsource (lib "eagle-import") (part "TI-TPS22919DCK"))
    )
    (comp (ref "U13")
      (value "TI-TPS22919DCK")
      (footprint "eagle-import:TI-TPS22919DCK")
      (fields (field (name "PN") "TPS22919DCK") (field (name "MFG") "Texas Instruments"))
      (libsource (lib "eagle-import") (part "TI-TPS22919DCK"))
    )
    (comp (ref "FB1")
      (value "FERRITE-BEAD0402")
      (footprint "eagle-import:0402")
      (fields (field (name "MFG") "Taiyo Yuden"))
      (libsource (lib "eagle-import") (part "FERRITE-BEAD0402"))
    )
    (comp (ref "J11")
      (value "USB-C-RECEPTACLE-KOREANHRO")
      (footprint "eagle-import:KOREANHRO-TYPE-C-31-M-08A")
      (fields (field (name "PN") "TYPE-C-31-M-08A") (field (name "MFG") "Korean Hroparts Electronics"))
      (libsource (lib "eagle-import") (part "USB-C-RECEPTACLE-KOREANHRO"))
    )
    (comp (ref "R39")
      (value "5.1k")
      (footprint "eagle-import:0402")
      (fields (field (name "MFG") "Yageo"))
      (libsource (lib "eagle-import") (part "RESISTOR0402"))
    )
    (comp (ref "R40")
      (value "5.1k")
      (footprint "eagle-import:0402")
      (fields (field (name "MFG") "Yageo"))
      (libsource (lib "eagle-import") (part "RESISTOR0402"))
    )
    (comp (ref "U25")
      (value "DIODESINC-DT1446-04V-7")
      (footprint "eagle-import:DIODESINC-DT1446-04V-7")
      (fields (field (name "MFG") "Diodes Incorporated"))
      (libsource (lib "eagle-import") (part "DIODESINC-DT1446-04V-7"))
    )
    (comp (ref "C27")
      (value "100n")
      (footprint "eagle-import:0402")
      (fields (field (name "MFG") "Murata"))
      (libsource (lib "eagle-import") (part "CAPACITOR0402"))
    )
    (comp (ref "U17")
      (value "PANASONIC-EKMB110711X")
      (footprint "eagle-import:PANASONIC-EKMB110711X")
      (fields (field (name "MFG") "Panasonic") (field (name "PN") "EKMB1107112"))
      (libsource (lib "eagle-import") (part "PANASONIC-EKMB110711X"))
    )
    (comp (ref "C63")
      (value "10u")
      (footprint "eagle-import:0805")
      (fields (field (name "MFG") "Samsung"))
      (libsource (lib "eagle-import") (part "CAPACITOR0805"))
    )
    (comp (ref "C64")
      (value "100n")
      (footprint "eagle-import:0402")
      (fields (field (name "MFG") "Murata"))
      (libsource (lib "eagle-import") (part "CAPACITOR0402"))
    )
    (comp (ref "J10")
      (value "MICROSD-SOCKET")
      (footprint "eagle-import:MOLEX-1051620001")
      (fields (field (name "MFG") "Molex"))
      (libsource (lib "eagle-import") (part "MICROSD-SOCKET"))
    )
    (comp (ref "R29")
      (value "47k")
      (footprint "eagle-import:0402")
      (fields (field (name "MFG") "Walsin"))
      (libsource (lib "eagle-import") (part "RESISTOR0402"))
    )
    (comp (ref "R30")
      (value "47k")
      (footprint "eagle-import:0402")
      (fields (field (name "MFG") "Walsin"))
      (libsource (lib "eagle-import") (part "RESISTOR0402"))
    )
    (comp (ref "R31")
      (value "47k")
      (footprint "eagle-import:0402")
      (fields (field (name "MFG") "Walsin"))
      (libsource (lib "eagle-import") (part "RESISTOR0402"))
    )
    (comp (ref "R32")
      (value "47k")
      (footprint "eagle-import:0402")
      (fields (field (name "MFG") "Walsin"))
      (libsource (lib "eagle-import") (part "RESISTOR0402"))
    )
    (comp (ref "R33")
      (value "47k")
      (footprint "eagle-import:0402")
      (fields (field (name "MFG") "Walsin"))
      (libsource (lib "eagle-import") (part "RESISTOR0402"))
    )
    (comp (ref "C18")
      (value "22p")
      (footprint "eagle-import:0402")
      (fields (field (name "MFG") "Murata"))
      (libsource (lib "eagle-import") (part "CAPACITOR0402"))
    )
    (comp (ref "C19")
      (value "22p")
      (footprint "eagle-import:0402")
      (fields (field (name "MFG") "Murata"))
      (libsource (lib "eagle-import") (part "CAPACITOR0402"))
    )
    (comp (ref "C20")
      (value "100n")
      (footprint "eagle-import:0402")
      (fields (field (name "MFG") "Murata"))
      (libsource (lib "eagle-import") (part "CAPACITOR0402"))
    )
    (comp (ref "C21")
      (value "10u")
      (footprint "eagle-import:0805")
      (fields (field (name "MFG") "Samsung"))
      (libsource (lib "eagle-import") (part "CAPACITOR0805"))
    )
    (comp (ref "C22")
      (value "22p")
      (footprint "eagle-import:0402")
      (fields (field (name "MFG") "Murata"))
      (libsource (lib "eagle-import") (part "CAPACITOR0402"))
    )
    (comp (ref "C23")
      (value "100n")
      (footprint "eagle-import:0402")
      (fields (field (name "MFG") "Murata"))
      (libsource (lib "eagle-import") (part "CAPACITOR0402"))
    )
    (comp (ref "C24")
      (value "100n")
      (footprint "eagle-import:0402")
      (fields (field (name "MFG") "Murata"))
      (libsource (lib "eagle-import") (part "CAPACITOR0402"))
    )
    (comp (ref "C25")
      (value "100n")
      (footprint "eagle-import:0402")
      (fields (field (name "MFG") "Murata"))
      (libsource (lib "eagle-import") (part "CAPACITOR0402"))
    )
    (comp (ref "C26")
      (value "100n")
      (footprint "eagle-import:0402")
      (fields (field (name "MFG") "Murata"))
      (libsource (lib "eagle-import") (part "CAPACITOR0402"))
    )
    (comp (ref "R17")
      (value "10k")
      (footprint "eagle-import:0402")
      (fields (field (name "MFG") "Yageo"))
      (libsource (lib "eagle-import") (part "RESISTOR0402"))
    )
    (comp (ref "U14")
      (value "TI-MSP430FR2422IRHL")
      (footprint "eagle-import:TI-MSP430FR2422IRHL")
      (fields (field (name "PN") "MSP430FR2422IRHL") (field (name "MFG") "Texas Instruments"))
      (libsource (lib "eagle-import") (part "TI-MSP430FR2422IRHL"))
    )
    (comp (ref "U15")
      (value "NXP-NTB0102")
      (footprint "eagle-import:NXP-NTB0102GF")
      (fields (field (name "PN") "NTB0102GF") (field (name "MFG") "NXP"))
      (libsource (lib "eagle-import") (part "NXP-NTB0102"))
    )
    (comp (ref "U16")
      (value "NXP-NTB0102")
      (footprint "eagle-import:NXP-NTB0102GF")
      (fields (field (name "PN") "NTB0102GF") (field (name "MFG") "NXP"))
      (libsource (lib "eagle-import") (part "NXP-NTB0102"))
    )
    (comp (ref "X1")
      (value "EPSON-FC-135")
      (footprint "eagle-import:EPSON-FC-135")
      (fields (field (name "MFG") "Epson") (field (name "PN") "Q13FC13500005"))
      (libsource (lib "eagle-import") (part "EPSON-FC-135"))
    )
    (comp (ref "C45")
      (value "100n")
      (footprint "eagle-import:0402")
      (fields (field (name "MFG") "Murata"))
      (libsource (lib "eagle-import") (part "CAPACITOR0402"))
    )
    (comp (ref "C46")
      (value "10u")
      (footprint "eagle-import:0805")
      (fields (field (name "MFG") "Samsung"))
      (libsource (lib "eagle-import") (part "CAPACITOR0805"))
    )
    (comp (ref "C47")
      (value "100n")
      (footprint "eagle-import:0402")
      (fields (field (name "MFG") "Murata"))
      (libsource (lib "eagle-import") (part "CAPACITOR0402"))
    )
    (comp (ref "C48")
      (value "10u")
      (footprint "eagle-import:0805")
      (fields (field (name "MFG") "Samsung"))
      (libsource (lib "eagle-import") (part "CAPACITOR0805"))
    )
    (comp (ref "C49")
      (value "100n")
      (footprint "eagle-import:0402")
      (fields (field (name "MFG") "Murata"))
      (libsource (lib "eagle-import") (part "CAPACITOR0402"))
    )
    (comp (ref "C50")
      (value "10u")
      (footprint "eagle-import:0805")
      (fields (field (name "MFG") "Samsung"))
      (libsource (lib "eagle-import") (part "CAPACITOR0805"))
    )
    (comp (ref "C51")
      (value "100n")
      (footprint "eagle-import:0402")
      (fields (field (name "MFG") "Murata"))
      (libsource (lib "eagle-import") (part "CAPACITOR0402"))
    )
    (comp (ref "C52")
      (value "100n")
      (footprint "eagle-import:0402")
      (fields (field (name "MFG") "Murata"))
      (libsource (lib "eagle-import") (part "CAPACITOR0402"))
    )
    (comp (ref "C53")
      (value "100n")
      (footprint "eagle-import:0402")
      (fields (field (name "MFG") "Murata"))
      (libsource (lib "eagle-import") (part "CAPACITOR0402"))
    )
    (comp (ref "C54")
      (value "10u")
      (footprint "eagle-import:0805")
      (fields (field (name "MFG") "Samsung"))
      (libsource (lib "eagle-import") (part "CAPACITOR0805"))
    )
    (comp (ref "C55")
      (value "100n")
      (footprint "eagle-import:0402")
      (fields (field (name "MFG") "Murata"))
      (libsource (lib "eagle-import") (part "CAPACITOR0402"))
    )
    (comp (ref "C56")
      (value "100n")
      (footprint "eagle-import:0402")
      (fields (field (name "MFG") "Murata"))
      (libsource (lib "eagle-import") (part "CAPACITOR0402"))
    )
    (comp (ref "C57")
      (value "10u")
      (footprint "eagle-import:0805")
      (fields (field (name "MFG") "Samsung"))
      (libsource (lib "eagle-import") (part "CAPACITOR0805"))
    )
    (comp (ref "C58")
      (value "100n")
      (footprint "eagle-import:0402")
      (fields (field (name "MFG") "Murata"))
      (libsource (lib "eagle-import") (part "CAPACITOR0402"))
    )
    (comp (ref "J9")
      (value "S-MOUNT-LENS-HOLDERM12LENSES-PT-LH008P")
      (footprint "eagle-import:M12LENSES-PT-LH008P")
      (fields (field (name "MFG") "M12 Lenses"))
      (libsource (lib "eagle-import") (part "S-MOUNT-LENS-HOLDERM12LENSES-PT-LH008P"))
    )
    (comp (ref "R27")
      (value "10k")
      (footprint "eagle-import:0402")
      (fields (field (name "MFG") "Yageo"))
      (libsource (lib "eagle-import") (part "RESISTOR0402"))
    )
    (comp (ref "R28")
      (value "10k")
      (footprint "eagle-import:0402")
      (fields (field (name "MFG") "Yageo"))
      (libsource (lib "eagle-import") (part "RESISTOR0402"))
    )
    (comp (ref "U21")
      (value "NEXPERIA-74LVC1G98-BUFFER")
      (footprint "eagle-import:NEXPERIA-SOT363")
      (fields (field (name "MFG") "Nexperia"))
      (libsource (lib "eagle-import") (part "NEXPERIA-74LVC1G98-BUFFER"))
    )
    (comp (ref "U22")
      (value "ON-AR0330CS1C12SPKA0")
      (footprint "eagle-import:ON-AR0330CS1C12SPKA0")
      (fields (field (name "MFG") "ON Semiconductor") (field (name "PN") "AR0330CS1C12SPKA0-CR"))
      (libsource (lib "eagle-import") (part "ON-AR0330CS1C12SPKA0"))
    )
    (comp (ref "C65")
      (value "10n")
      (footprint "eagle-import:0402")
      (fields (field (name "MFG") "Samsung"))
      (libsource (lib "eagle-import") (part "CAPACITOR0402"))
    )
    (comp (ref "C66")
      (value "100n")
      (footprint "eagle-import:0402")
      (fields (field (name "MFG") "Murata"))
      (libsource (lib "eagle-import") (part "CAPACITOR0402"))
    )
    (comp (ref "C67")
      (value "2.2u")
      (footprint "eagle-import:0402")
      (fields (field (name "MFG") "Taiyo Yuden"))
      (libsource (lib "eagle-import") (part "CAPACITOR0402"))
    )
    (comp (ref "C68")
      (value "100n")
      (footprint "eagle-import:0402")
      (fields (field (name "MFG") "Murata"))
      (libsource (lib "eagle-import") (part "CAPACITOR0402"))
    )
    (comp (ref "C69")
      (value "100n")
      (footprint "eagle-import:0402")
      (fields (field (name "MFG") "Murata"))
      (libsource (lib "eagle-import") (part "CAPACITOR0402"))
    )
    (comp (ref "C70")
      (value "100n")
      (footprint "eagle-import:0402")
      (fields (field (name "MFG") "Murata"))
      (libsource (lib "eagle-import") (part "CAPACITOR0402"))
    )
    (comp (ref "C71")
      (value "100n")
      (footprint "eagle-import:0402")
      (fields (field (name "MFG") "Murata"))
      (libsource (lib "eagle-import") (part "CAPACITOR0402"))
    )
    (comp (ref "C72")
      (value "2.2u")
      (footprint "eagle-import:0402")
      (fields (field (name "MFG") "Taiyo Yuden"))
      (libsource (lib "eagle-import") (part "CAPACITOR0402"))
    )
    (comp (ref "C73")
      (value "100n")
      (footprint "eagle-import:0402")
      (fields (field (name "MFG") "Murata"))
      (libsource (lib "eagle-import") (part "CAPACITOR0402"))
    )
    (comp (ref "C74")
      (value "100n")
      (footprint "eagle-import:0402")
      (fields (field (name "MFG") "Murata"))
      (libsource (lib "eagle-import") (part "CAPACITOR0402"))
    )
    (comp (ref "C75")
      (value "100n")
      (footprint "eagle-import:0402")
      (fields (field (name "MFG") "Murata"))
      (libsource (lib "eagle-import") (part "CAPACITOR0402"))
    )
    (comp (ref "C76")
      (value "100n")
      (footprint "eagle-import:0402")
      (fields (field (name "MFG") "Murata"))
      (libsource (lib "eagle-import") (part "CAPACITOR0402"))
    )
    (comp (ref "C77")
      (value "2.2u")
      (footprint "eagle-import:0402")
      (fields (field (name "MFG") "Taiyo Yuden"))
      (libsource (lib "eagle-import") (part "CAPACITOR0402"))
    )
    (comp (ref "C78")
      (value "100n")
      (footprint "eagle-import:0402")
      (fields (field (name "MFG") "Murata"))
      (libsource (lib "eagle-import") (part "CAPACITOR0402"))
    )
    (comp (ref "C79")
      (value "100n")
      (footprint "eagle-import:0402")
      (fields (field (name "MFG") "Murata"))
      (libsource (lib "eagle-import") (part "CAPACITOR0402"))
    )
    (comp (ref "C80")
      (value "100n")
      (footprint "eagle-import:0402")
      (fields (field (name "MFG") "Murata"))
      (libsource (lib "eagle-import") (part "CAPACITOR0402"))
    )
    (comp (ref "C81")
      (value "100n")
      (footprint "eagle-import:0402")
      (fields (field (name "MFG") "Murata"))
      (libsource (lib "eagle-import") (part "CAPACITOR0402"))
    )
    (comp (ref "C82")
      (value "100n")
      (footprint "eagle-import:0402")
      (fields (field (name "MFG") "Murata"))
      (libsource (lib "eagle-import") (part "CAPACITOR0402"))
    )
    (comp (ref "C83")
      (value "100n")
      (footprint "eagle-import:0402")
      (fields (field (name "MFG") "Murata"))
      (libsource (lib "eagle-import") (part "CAPACITOR0402"))
    )
    (comp (ref "C84")
      (value "2.2u")
      (footprint "eagle-import:0402")
      (fields (field (name "MFG") "Taiyo Yuden"))
      (libsource (lib "eagle-import") (part "CAPACITOR0402"))
    )
    (comp (ref "C85")
      (value "2.2u")
      (footprint "eagle-import:0402")
      (fields (field (name "MFG") "Taiyo Yuden"))
      (libsource (lib "eagle-import") (part "CAPACITOR0402"))
    )
    (comp (ref "C86")
      (value "2.2u")
      (footprint "eagle-import:0402")
      (fields (field (name "MFG") "Taiyo Yuden"))
      (libsource (lib "eagle-import") (part "CAPACITOR0402"))
    )
    (comp (ref "C87")
      (value "2.2u")
      (footprint "eagle-import:0402")
      (fields (field (name "MFG") "Taiyo Yuden"))
      (libsource (lib "eagle-import") (part "CAPACITOR0402"))
    )
    (comp (ref "C88")
      (value "2.2u")
      (footprint "eagle-import:0402")
      (fields (field (name "MFG") "Taiyo Yuden"))
      (libsource (lib "eagle-import") (part "CAPACITOR0402"))
    )
    (comp (ref "H1")
      (value "TAGCONNECT-TC2030-NLEDGE")
      (footprint "eagle-import:TAGCONNECT-TC2030-NL-EDGE")
      (libsource (lib "eagle-import") (part "TAGCONNECT-TC2030-NLEDGE"))
    )
    (comp (ref "LED5")
      (value "LED")
      (footprint "eagle-import:LED-0603")
      (fields (field (name "MFG") "OSRAM"))
      (libsource (lib "eagle-import") (part "LED"))
    )
    (comp (ref "LED6")
      (value "LED")
      (footprint "eagle-import:LED-0603")
      (fields (field (name "MFG") "OSRAM"))
      (libsource (lib "eagle-import") (part "LED"))
    )
    (comp (ref "LED7")
      (value "LED")
      (footprint "eagle-import:LED-0603")
      (fields (field (name "MFG") "OSRAM"))
      (libsource (lib "eagle-import") (part "LED"))
    )
    (comp (ref "LED8")
      (value "LED")
      (footprint "eagle-import:LED-0603")
      (fields (field (name "MFG") "OSRAM"))
      (libsource (lib "eagle-import") (part "LED"))
    )
    (comp (ref "R34")
      (value "1.8k")
      (footprint "eagle-import:0402")
      (fields (field (name "MFG") "Yageo"))
      (libsource (lib "eagle-import") (part "RESISTOR0402"))
    )
    (comp (ref "R35")
      (value "1.8k")
      (footprint "eagle-import:0402")
      (fields (field (name "MFG") "Yageo"))
      (libsource (lib "eagle-import") (part "RESISTOR0402"))
    )
    (comp (ref "R36")
      (value "1.8k")
      (footprint "eagle-import:0402")
      (fields (field (name "MFG") "Yageo"))
      (libsource (lib "eagle-import") (part "RESISTOR0402"))
    )
    (comp (ref "R37")
      (value "1.8k")
      (footprint "eagle-import:0402")
      (fields (field (name "MFG") "Yageo"))
      (libsource (lib "eagle-import") (part "RESISTOR0402"))
    )
    (comp (ref "R38")
      (value "3k")
      (footprint "eagle-import:0402")
      (fields (field (name "MFG") "Yageo"))
      (libsource (lib "eagle-import") (part "RESISTOR0402"))
    )
    (comp (ref "U24")
      (value "STM-STM32F730")
      (footprint "eagle-import:STM-STM32F730I8")
      (fields (field (name "MFG") "STMicroelectronics") (field (name "PN") "STM32F730I8K6"))
      (libsource (lib "eagle-import") (part "STM-STM32F730"))
    )
    (comp (ref "X3")
      (value "SITIME-SIT8021")
      (footprint "eagle-import:SITIME-SIT8021")
      (fields (field (name "MFG") "SiTime") (field (name "PN") "SIT8021AI-J4-18S-16.000000E"))
      (libsource (lib "eagle-import") (part "SITIME-SIT8021"))
    )
  )
  (nets
    (net (code "7") (name "BAT_CHRG_LVL") (class "Default")
      (node (ref "C7") (pin "1") (pinfunction "1_1") (pintype "bidirectional"))
      (node (ref "R7") (pin "2") (pinfunction "2_2") (pintype "bidirectional"))
      (node (ref "R9") (pin "1") (pinfunction "1_1") (pintype "bidirectional"))
      (node (ref "U24") (pin "J2") (pinfunction "PF3_J2_J2") (pintype "bidirectional"))
    )
    (net (code "8") (name "BAT_CHRG_STAT") (class "Default")
      (node (ref "U24") (pin "R11") (pinfunction "PE15_R11_R11") (pintype "bidirectional"))
      (node (ref "U4") (pin "1") (pinfunction "STAT_1") (pintype "bidirectional"))
    )
    (net (code "9") (name "GND") (class "Default")
      (node (ref "C1") (pin "2") (pinfunction "2_2") (pintype "bidirectional"))
      (node (ref "C10") (pin "2") (pinfunction "2_2") (pintype "bidirectional"))
      (node (ref "C11") (pin "2") (pinfunction "2_2") (pintype "bidirectional"))
      (node (ref "C12") (pin "2") (pinfunction "2_2") (pintype "bidirectional"))
      (node (ref "C13") (pin "2") (pinfunction "2_2") (pintype "bidirectional"))
      (node (ref "C14") (pin "2") (pinfunction "2_2") (pintype "bidirectional"))
      (node (ref "C15") (pin "2") (pinfunction "2_2") (pintype "bidirectional"))
      (node (ref "C16") (pin "2") (pinfunction "2_2") (pintype "bidirectional"))
      (node (ref "C17") (pin "2") (pinfunction "2_2") (pintype "bidirectional"))
      (node (ref "C18") (pin "2") (pinfunction "2_2") (pintype "bidirectional"))
      (node (ref "C19") (pin "2") (pinfunction "2_2") (pintype "bidirectional"))
      (node (ref "C2") (pin "2") (pinfunction "2_2") (pintype "bidirectional"))
      (node (ref "C20") (pin "2") (pinfunction "2_2") (pintype "bidirectional"))
      (node (ref "C21") (pin "2") (pinfunction "2_2") (pintype "bidirectional"))
      (node (ref "C22") (pin "2") (pinfunction "2_2") (pintype "bidirectional"))
      (node (ref "C23") (pin "2") (pinfunction "2_2") (pintype "bidirectional"))
      (node (ref "C24") (pin "2") (pinfunction "2_2") (pintype "bidirectional"))
      (node (ref "C25") (pin "2") (pinfunction "2_2") (pintype "bidirectional"))
      (node (ref "C26") (pin "2") (pinfunction "2_2") (pintype "bidirectional"))
      (node (ref "C27") (pin "2") (pinfunction "2_2") (pintype "bidirectional"))
      (node (ref "C28") (pin "2") (pinfunction "2_2") (pintype "bidirectional"))
      (node (ref "C29") (pin "2") (pinfunction "2_2") (pintype "bidirectional"))
      (node (ref "C3") (pin "2") (pinfunction "2_2") (pintype "bidirectional"))
      (node (ref "C30") (pin "2") (pinfunction "2_2") (pintype "bidirectional"))
      (node (ref "C31") (pin "2") (pinfunction "2_2") (pintype "bidirectional"))
      (node (ref "C32") (pin "2") (pinfunction "2_2") (pintype "bidirectional"))
      (node (ref "C33") (pin "2") (pinfunction "2_2") (pintype "bidirectional"))
      (node (ref "C34") (pin "2") (pinfunction "2_2") (pintype "bidirectional"))
      (node (ref "C35") (pin "2") (pinfunction "2_2") (pintype "bidirectional"))
      (node (ref "C36") (pin "2") (pinfunction "2_2") (pintype "bidirectional"))
      (node (ref "C37") (pin "2") (pinfunction "2_2") (pintype "bidirectional"))
      (node (ref "C38") (pin "2") (pinfunction "2_2") (pintype "bidirectional"))
      (node (ref "C4") (pin "2") (pinfunction "2_2") (pintype "bidirectional"))
      (node (ref "C41") (pin "2") (pinfunction "2_2") (pintype "bidirectional"))
      (node (ref "C44") (pin "2") (pinfunction "2_2") (pintype "bidirectional"))
      (node (ref "C45") (pin "2") (pinfunction "2_2") (pintype "bidirectional"))
      (node (ref "C46") (pin "2") (pinfunction "2_2") (pintype "bidirectional"))
      (node (ref "C47") (pin "2") (pinfunction "2_2") (pintype "bidirectional"))
      (node (ref "C48") (pin "2") (pinfunction "2_2") (pintype "bidirectional"))
      (node (ref "C49") (pin "2") (pinfunction "2_2") (pintype "bidirectional"))
      (node (ref "C5") (pin "2") (pinfunction "2_2") (pintype "bidirectional"))
      (node (ref "C50") (pin "2") (pinfunction "2_2") (pintype "bidirectional"))
      (node (ref "C51") (pin "2") (pinfunction "2_2") (pintype "bidirectional"))
      (node (ref "C52") (pin "2") (pinfunction "2_2") (pintype "bidirectional"))
      (node (ref "C53") (pin "2") (pinfunction "2_2") (pintype "bidirectional"))
      (node (ref "C54") (pin "2") (pinfunction "2_2") (pintype "bidirectional"))
      (node (ref "C55") (pin "2") (pinfunction "2_2") (pintype "bidirectional"))
      (node (ref "C56") (pin "2") (pinfunction "2_2") (pintype "bidirectional"))
      (node (ref "C57") (pin "2") (pinfunction "2_2") (pintype "bidirectional"))
      (node (ref "C58") (pin "2") (pinfunction "2_2") (pintype "bidirectional"))
      (node (ref "C59") (pin "2") (pinfunction "2_2") (pintype "bidirectional"))
      (node (ref "C6") (pin "2") (pinfunction "2_2") (pintype "bidirectional"))
      (node (ref "C60") (pin "2") (pinfunction "2_2") (pintype "bidirectional"))
      (node (ref "C61") (pin "2") (pinfunction "2_2") (pintype "bidirectional"))
      (node (ref "C62") (pin "2") (pinfunction "2_2") (pintype "bidirectional"))
      (node (ref "C63") (pin "2") (pinfunction "2_2") (pintype "bidirectional"))
      (node (ref "C64") (pin "2") (pinfunction "2_2") (pintype "bidirectional"))
      (node (ref "C65") (pin "2") (pinfunction "2_2") (pintype "bidirectional"))
      (node (ref "C66") (pin "2") (pinfunction "2_2") (pintype "bidirectional"))
      (node (ref "C67") (pin "2") (pinfunction "2_2") (pintype "bidirectional"))
      (node (ref "C68") (pin "2") (pinfunction "2_2") (pintype "bidirectional"))
      (node (ref "C69") (pin "2") (pinfunction "2_2") (pintype "bidirectional"))
      (node (ref "C7") (pin "2") (pinfunction "2_2") (pintype "bidirectional"))
      (node (ref "C70") (pin "2") (pinfunction "2_2") (pintype "bidirectional"))
      (node (ref "C71") (pin "2") (pinfunction "2_2") (pintype "bidirectional"))
      (node (ref "C72") (pin "2") (pinfunction "2_2") (pintype "bidirectional"))
      (node (ref "C73") (pin "2") (pinfunction "2_2") (pintype "bidirectional"))
      (node (ref "C74") (pin "2") (pinfunction "2_2") (pintype "bidirectional"))
      (node (ref "C75") (pin "2") (pinfunction "2_2") (pintype "bidirectional"))
      (node (ref "C76") (pin "2") (pinfunction "2_2") (pintype "bidirectional"))
      (node (ref "C77") (pin "2") (pinfunction "2_2") (pintype "bidirectional"))
      (node (ref "C78") (pin "2") (pinfunction "2_2") (pintype "bidirectional"))
      (node (ref "C79") (pin "2") (pinfunction "2_2") (pintype "bidirectional"))
      (node (ref "C8") (pin "2") (pinfunction "2_2") (pintype "bidirectional"))
      (node (ref "C80") (pin "2") (pinfunction "2_2") (pintype "bidirectional"))
      (node (ref "C81") (pin "2") (pinfunction "2_2") (pintype "bidirectional"))
      (node (ref "C82") (pin "2") (pinfunction "2_2") (pintype "bidirectional"))
      (node (ref "C83") (pin "2") (pinfunction "2_2") (pintype "bidirectional"))
      (node (ref "C84") (pin "2") (pinfunction "2_2") (pintype "bidirectional"))
      (node (ref "C85") (pin "2") (pinfunction "2_2") (pintype "bidirectional"))
      (node (ref "C86") (pin "2") (pinfunction "2_2") (pintype "bidirectional"))
      (node (ref "C87") (pin "2") (pinfunction "2_2") (pintype "bidirectional"))
      (node (ref "C88") (pin "2") (pinfunction "2_2") (pintype "bidirectional"))
      (node (ref "C9") (pin "2") (pinfunction "2_2") (pintype "bidirectional"))
      (node (ref "H1") (pin "5") (pinfunction "5_5") (pintype "bidirectional"))
      (node (ref "J10") (pin "GND1") (pinfunction "GND_GND1") (pintype "bidirectional"))
      (node (ref "J10") (pin "GND2") (pinfunction "GND_GND2") (pintype "bidirectional"))
      (node (ref "J10") (pin "GND3") (pinfunction "GND_GND3") (pintype "bidirectional"))
      (node (ref "J10") (pin "GND4") (pinfunction "GND_GND4") (pintype "bidirectional"))
      (node (ref "J10") (pin "VSS") (pinfunction "GND_VSS") (pintype "bidirectional"))
      (node (ref "J11") (pin "A1") (pinfunction "GND_A1") (pintype "bidirectional"))
      (node (ref "J11") (pin "A12") (pinfunction "GND_A12") (pintype "bidirectional"))
      (node (ref "J11") (pin "B1") (pinfunction "GND_B1") (pintype "bidirectional"))
      (node (ref "J11") (pin "B12") (pinfunction "GND_B12") (pintype "bidirectional"))
      (node (ref "J11") (pin "GND1") (pinfunction "GND_GND1") (pintype "bidirectional"))
      (node (ref "J11") (pin "GND2") (pinfunction "GND_GND2") (pintype "bidirectional"))
      (node (ref "J11") (pin "GND3") (pinfunction "GND_GND3") (pintype "bidirectional"))
      (node (ref "J11") (pin "GND4") (pinfunction "GND_GND4") (pintype "bidirectional"))
      (node (ref "J11") (pin "GND5") (pinfunction "GND_GND5") (pintype "bidirectional"))
      (node (ref "J11") (pin "GND6") (pinfunction "GND_GND6") (pintype "bidirectional"))
      (node (ref "J11") (pin "GND7") (pinfunction "GND_GND7") (pintype "bidirectional"))
      (node (ref "J11") (pin "GND8") (pinfunction "GND_GND8") (pintype "bidirectional"))
      (node (ref "J5") (pin "GND1") (pinfunction "GND_GND1") (pintype "bidirectional"))
      (node (ref "J5") (pin "GND2") (pinfunction "GND_GND2") (pintype "bidirectional"))
      (node (ref "J5") (pin "R") (pinfunction "R_R") (pintype "bidirectional"))
      (node (ref "R1") (pin "2") (pinfunction "2_2") (pintype "bidirectional"))
      (node (ref "R10") (pin "2") (pinfunction "2_2") (pintype "bidirectional"))
      (node (ref "R12") (pin "2") (pinfunction "2_2") (pintype "bidirectional"))
      (node (ref "R14") (pin "2") (pinfunction "2_2") (pintype "bidirectional"))
      (node (ref "R16") (pin "2") (pinfunction "2_2") (pintype "bidirectional"))
      (node (ref "R17") (pin "1") (pinfunction "1_1") (pintype "bidirectional"))
      (node (ref "R18") (pin "2") (pinfunction "2_2") (pintype "bidirectional"))
      (node (ref "R19") (pin "2") (pinfunction "2_2") (pintype "bidirectional"))
      (node (ref "R20") (pin "2") (pinfunction "2_2") (pintype "bidirectional"))
      (node (ref "R21") (pin "2") (pinfunction "2_2") (pintype "bidirectional"))
      (node (ref "R3") (pin "2") (pinfunction "2_2") (pintype "bidirectional"))
      (node (ref "R34") (pin "2") (pinfunction "2_2") (pintype "bidirectional"))
      (node (ref "R35") (pin "2") (pinfunction "2_2") (pintype "bidirectional"))
      (node (ref "R36") (pin "2") (pinfunction "2_2") (pintype "bidirectional"))
      (node (ref "R37") (pin "2") (pinfunction "2_2") (pintype "bidirectional"))
      (node (ref "R38") (pin "1") (pinfunction "1_1") (pintype "bidirectional"))
      (node (ref "R39") (pin "2") (pinfunction "2_2") (pintype "bidirectional"))
      (node (ref "R4") (pin "2") (pinfunction "2_2") (pintype "bidirectional"))
      (node (ref "R40") (pin "2") (pinfunction "2_2") (pintype "bidirectional"))
      (node (ref "R6") (pin "1") (pinfunction "1_1") (pintype "bidirectional"))
      (node (ref "R9") (pin "2") (pinfunction "2_2") (pintype "bidirectional"))
      (node (ref "U1") (pin "1") (pinfunction "GND_1") (pintype "bidirectional"))
      (node (ref "U10") (pin "2") (pinfunction "GND_2") (pintype "bidirectional"))
      (node (ref "U11") (pin "2") (pinfunction "GND_2") (pintype "bidirectional"))
      (node (ref "U12") (pin "2") (pinfunction "GND_2") (pintype "bidirectional"))
      (node (ref "U13") (pin "2") (pinfunction "GND_2") (pintype "bidirectional"))
      (node (ref "U14") (pin "21") (pinfunction "GND_THERMALPAD_21") (pintype "bidirectional"))
      (node (ref "U14") (pin "6") (pinfunction "GND_6") (pintype "bidirectional"))
      (node (ref "U15") (pin "2") (pinfunction "GND_2") (pintype "bidirectional"))
      (node (ref "U16") (pin "2") (pinfunction "GND_2") (pintype "bidirectional"))
      (node (ref "U17") (pin "3") (pinfunction "GND_3") (pintype "bidirectional"))
      (node (ref "U18") (pin "E5") (pinfunction "GND_E5_E5") (pintype "bidirectional"))
      (node (ref "U18") (pin "E6") (pinfunction "GND_E6_E6") (pintype "bidirectional"))
      (node (ref "U18") (pin "E7") (pinfunction "GND_E7_E7") (pintype "bidirectional"))
      (node (ref "U18") (pin "F5") (pinfunction "GND_F5_F5") (pintype "bidirectional"))
      (node (ref "U18") (pin "F6") (pinfunction "GND_F6_F6") (pintype "bidirectional"))
      (node (ref "U18") (pin "F7") (pinfunction "GND_F7_F7") (pintype "bidirectional"))
      (node (ref "U18") (pin "G5") (pinfunction "GND_G5_G5") (pintype "bidirectional"))
      (node (ref "U18") (pin "G6") (pinfunction "GND_G6_G6") (pintype "bidirectional"))
      (node (ref "U18") (pin "G7") (pinfunction "GND_G7_G7") (pintype "bidirectional"))
      (node (ref "U18") (pin "H5") (pinfunction "GND_H5_H5") (pintype "bidirectional"))
      (node (ref "U19") (pin "4") (pinfunction "GND_4") (pintype "bidirectional"))
      (node (ref "U19") (pin "9") (pinfunction "GND_9") (pintype "bidirectional"))
      (node (ref "U2") (pin "2") (pinfunction "GND_2") (pintype "bidirectional"))
      (node (ref "U20") (pin "2") (pinfunction "GND_2") (pintype "bidirectional"))
      (node (ref "U20") (pin "3") (pinfunction "GND_3") (pintype "bidirectional"))
      (node (ref "U21") (pin "2") (pinfunction "GND_2") (pintype "bidirectional"))
      (node (ref "U21") (pin "3") (pinfunction "GND_3") (pintype "bidirectional"))
      (node (ref "U22") (pin "A3") (pinfunction "AGND_A3") (pintype "bidirectional"))
      (node (ref "U22") (pin "B4") (pinfunction "DGND_B4") (pintype "bidirectional"))
      (node (ref "U22") (pin "B5") (pinfunction "AGND_B5") (pintype "bidirectional"))
      (node (ref "U22") (pin "B6") (pinfunction "DGND_B6") (pintype "bidirectional"))
      (node (ref "U22") (pin "B7") (pinfunction "TEST_B7") (pintype "bidirectional"))
      (node (ref "U22") (pin "C1") (pinfunction "SADDR_C1") (pintype "bidirectional"))
      (node (ref "U22") (pin "C4") (pinfunction "DGND_C4") (pintype "bidirectional"))
      (node (ref "U22") (pin "C5") (pinfunction "DGND_C5") (pintype "bidirectional"))
      (node (ref "U22") (pin "C6") (pinfunction "DGND_C6") (pintype "bidirectional"))
      (node (ref "U22") (pin "D4") (pinfunction "DGND_D4") (pintype "bidirectional"))
      (node (ref "U22") (pin "E6") (pinfunction "DGND_E6") (pintype "bidirectional"))
      (node (ref "U22") (pin "G1") (pinfunction "DGND_G1") (pintype "bidirectional"))
      (node (ref "U22") (pin "H2") (pinfunction "DGND_H2") (pintype "bidirectional"))
      (node (ref "U22") (pin "H3") (pinfunction "DGND_H3") (pintype "bidirectional"))
      (node (ref "U23") (pin "A1") (pinfunction "VSS_A1_A1") (pintype "bidirectional"))
      (node (ref "U23") (pin "A3") (pinfunction "VSSQ_A3_A3") (pintype "bidirectional"))
      (node (ref "U23") (pin "B7") (pinfunction "VSSQ_B7_B7") (pintype "bidirectional"))
      (node (ref "U23") (pin "C3") (pinfunction "VSSQ_C3_C3") (pintype "bidirectional"))
      (node (ref "U23") (pin "D7") (pinfunction "VSSQ_D7_D7") (pintype "bidirectional"))
      (node (ref "U23") (pin "E3") (pinfunction "VSS_E3_E3") (pintype "bidirectional"))
      (node (ref "U23") (pin "J1") (pinfunction "VSS_J1_J1") (pintype "bidirectional"))
      (node (ref "U24") (pin "D5") (pinfunction "VSS_D5_D5") (pintype "bidirectional"))
      (node (ref "U24") (pin "D6") (pinfunction "BOOT0_D6_D6") (pintype "bidirectional"))
      (node (ref "U24") (pin "D7") (pinfunction "VSS_D7_D7") (pintype "bidirectional"))
      (node (ref "U24") (pin "D8") (pinfunction "VSS_D8_D8") (pintype "bidirectional"))
      (node (ref "U24") (pin "D9") (pinfunction "VSS_D9_D9") (pintype "bidirectional"))
      (node (ref "U24") (pin "F10") (pinfunction "VSS_F10_F10") (pintype "bidirectional"))
      (node (ref "U24") (pin "F12") (pinfunction "VSS_F12_F12") (pintype "bidirectional"))
      (node (ref "U24") (pin "F2") (pinfunction "VSS_F2_F2") (pintype "bidirectional"))
      (node (ref "U24") (pin "F6") (pinfunction "VSS_F6_F6") (pintype "bidirectional"))
      (node (ref "U24") (pin "F7") (pinfunction "VSS_F7_F7") (pintype "bidirectional"))
      (node (ref "U24") (pin "F8") (pinfunction "VSS_F8_F8") (pintype "bidirectional"))
      (node (ref "U24") (pin "F9") (pinfunction "VSS_F9_F9") (pintype "bidirectional"))
      (node (ref "U24") (pin "G10") (pinfunction "VSS_G10_G10") (pintype "bidirectional"))
      (node (ref "U24") (pin "G12") (pinfunction "VSS_G12_G12") (pintype "bidirectional"))
      (node (ref "U24") (pin "G2") (pinfunction "VSS_G2_G2") (pintype "bidirectional"))
      (node (ref "U24") (pin "G6") (pinfunction "VSS_G6_G6") (pintype "bidirectional"))
      (node (ref "U24") (pin "G7") (pinfunction "VSS_G7_G7") (pintype "bidirectional"))
      (node (ref "U24") (pin "G8") (pinfunction "VSS_G8_G8") (pintype "bidirectional"))
      (node (ref "U24") (pin "G9") (pinfunction "VSS_G9_G9") (pintype "bidirectional"))
      (node (ref "U24") (pin "H10") (pinfunction "VSS_H10_H10") (pintype "bidirectional"))
      (node (ref "U24") (pin "H12") (pinfunction "VSS_H12_H12") (pintype "bidirectional"))
      (node (ref "U24") (pin "H6") (pinfunction "VSS_H6_H6") (pintype "bidirectional"))
      (node (ref "U24") (pin "H7") (pinfunction "VSS_H7_H7") (pintype "bidirectional"))
      (node (ref "U24") (pin "H8") (pinfunction "VSS_H8_H8") (pintype "bidirectional"))
      (node (ref "U24") (pin "H9") (pinfunction "VSS_H9_H9") (pintype "bidirectional"))
      (node (ref "U24") (pin "J10") (pinfunction "VSS_J10_J10") (pintype "bidirectional"))
      (node (ref "U24") (pin "J6") (pinfunction "VSS_J6_J6") (pintype "bidirectional"))
      (node (ref "U24") (pin "J7") (pinfunction "VSS_J7_J7") (pintype "bidirectional"))
      (node (ref "U24") (pin "J8") (pinfunction "VSS_J8_J8") (pintype "bidirectional"))
      (node (ref "U24") (pin "J9") (pinfunction "VSS_J9_J9") (pintype "bidirectional"))
      (node (ref "U24") (pin "K10") (pinfunction "VSS_K10_K10") (pintype "bidirectional"))
      (node (ref "U24") (pin "K6") (pinfunction "VSS_K6_K6") (pintype "bidirectional"))
      (node (ref "U24") (pin "K7") (pinfunction "VSS_K7_K7") (pintype "bidirectional"))
      (node (ref "U24") (pin "K8") (pinfunction "VSS_K8_K8") (pintype "bidirectional"))
      (node (ref "U24") (pin "K9") (pinfunction "VSS_K9_K9") (pintype "bidirectional"))
      (node (ref "U24") (pin "L4") (pinfunction "BYPASS_REG_L4_L4") (pintype "bidirectional"))
      (node (ref "U24") (pin "M1") (pinfunction "VSSA_M1_M1") (pintype "bidirectional"))
      (node (ref "U24") (pin "M8") (pinfunction "VSS_M8_M8") (pintype "bidirectional"))
      (node (ref "U24") (pin "M9") (pinfunction "VSS_M9_M9") (pintype "bidirectional"))
      (node (ref "U24") (pin "N1") (pinfunction "VREF-_N1_N1") (pintype "bidirectional"))
      (node (ref "U25") (pin "2") (pinfunction "GND_2") (pintype "bidirectional"))
      (node (ref "U3") (pin "2") (pinfunction "GND_2") (pintype "bidirectional"))
      (node (ref "U4") (pin "2") (pinfunction "GND_2") (pintype "bidirectional"))
      (node (ref "U5") (pin "2") (pinfunction "GND_2") (pintype "bidirectional"))
      (node (ref "U5") (pin "3") (pinfunction "GND_3") (pintype "bidirectional"))
      (node (ref "U6") (pin "2") (pinfunction "2_2") (pintype "bidirectional"))
      (node (ref "U7") (pin "1") (pinfunction "GND_1") (pintype "bidirectional"))
      (node (ref "U7") (pin "6") (pinfunction "PG_6") (pintype "bidirectional"))
      (node (ref "U8") (pin "1") (pinfunction "GND_1") (pintype "bidirectional"))
      (node (ref "U8") (pin "6") (pinfunction "PG_6") (pintype "bidirectional"))
      (node (ref "U9") (pin "1") (pinfunction "GND_1") (pintype "bidirectional"))
      (node (ref "U9") (pin "6") (pinfunction "PG_6") (pintype "bidirectional"))
      (node (ref "X2") (pin "1") (pinfunction "EN__1") (pintype "input"))
      (node (ref "X2") (pin "4") (pinfunction "GND_4") (pintype "bidirectional"))
      (node (ref "X3") (pin "1") (pinfunction "EN__1") (pintype "input"))
      (node (ref "X3") (pin "4") (pinfunction "GND_4") (pintype "bidirectional"))
    )
    (net (code "10") (name "GNDPLL0") (class "Default")
      (node (ref "C42") (pin "2") (pinfunction "2_2") (pintype "bidirectional"))
      (node (ref "C43") (pin "2") (pinfunction "2_2") (pintype "bidirectional"))
      (node (ref "U18") (pin "L6") (pinfunction "GNDPLL0_L6_L6") (pintype "bidirectional"))
    )
    (net (code "11") (name "GNDPLL1") (class "Default")
      (node (ref "C39") (pin "2") (pinfunction "2_2") (pintype "bidirectional"))
      (node (ref "C40") (pin "2") (pinfunction "2_2") (pintype "bidirectional"))
      (node (ref "U18") (pin "C5") (pinfunction "GNDPLL1_C5_C5") (pintype "bidirectional"))
    )
    (net (code "12") (name "ICE_CDONE") (class "Default")
      (node (ref "R24") (pin "2") (pinfunction "2_2") (pintype "bidirectional"))
      (node (ref "U18") (pin "K8") (pinfunction "CDONE_K8_K8") (pintype "bidirectional"))
      (node (ref "U24") (pin "R4") (pinfunction "PB1_R4_R4") (pintype "bidirectional"))
    )
    (net (code "13") (name "ICE_CRST_") (class "Default")
      (node (ref "R25") (pin "2") (pinfunction "2_2") (pintype "bidirectional"))
      (node (ref "U18") (pin "L9") (pinfunction "CRESET_B_L9_L9") (pintype "bidirectional"))
      (node (ref "U24") (pin "R6") (pinfunction "PF11_R6_R6") (pintype "bidirectional"))
    )
    (net (code "14") (name "ICE_IMG_CLK16MHZ") (class "Default")
      (node (ref "TP2") (pin "X") (pinfunction "X_X") (pintype "bidirectional"))
      (node (ref "U18") (pin "C11") (pinfunction "C11_C11") (pintype "bidirectional"))
      (node (ref "U21") (pin "6") (pinfunction "IN_6") (pintype "bidirectional"))
      (node (ref "X2") (pin "2") (pinfunction "OUT_2") (pintype "bidirectional"))
    )
    (net (code "15") (name "ICE_LED0") (class "Default")
      (node (ref "LED1") (pin "A") (pinfunction "A_A") (pintype "bidirectional"))
      (node (ref "U18") (pin "A10") (pinfunction "A10_A10") (pintype "bidirectional"))
    )
    (net (code "16") (name "ICE_LED1") (class "Default")
      (node (ref "LED2") (pin "A") (pinfunction "A_A") (pintype "bidirectional"))
      (node (ref "U18") (pin "A11") (pinfunction "A11_A11") (pintype "bidirectional"))
    )
    (net (code "17") (name "ICE_LED2") (class "Default")
      (node (ref "LED3") (pin "A") (pinfunction "A_A") (pintype "bidirectional"))
      (node (ref "U18") (pin "C9") (pinfunction "C9_C9") (pintype "bidirectional"))
    )
    (net (code "18") (name "ICE_LED3") (class "Default")
      (node (ref "LED4") (pin "A") (pinfunction "A_A") (pintype "bidirectional"))
      (node (ref "U18") (pin "B11") (pinfunction "B11_B11") (pintype "bidirectional"))
    )
    (net (code "19") (name "ICE_MSP_SPI_CLK") (class "Default")
      (node (ref "U16") (pin "5") (pinfunction "A1_5") (pintype "bidirectional"))
      (node (ref "U18") (pin "K2") (pinfunction "K2_K2") (pintype "bidirectional"))
    )
    (net (code "20") (name "ICE_MSP_SPI_CLK_X") (class "Default")
      (node (ref "U14") (pin "11") (pinfunction "PA.C/P2.4/TA1CLK/UCB0CLK/A6_11") (pintype "bidirectional"))
      (node (ref "U16") (pin "8") (pinfunction "B1_8") (pintype "bidirectional"))
    )
    (net (code "21") (name "ICE_MSP_SPI_DATA") (class "Default")
      (node (ref "U16") (pin "4") (pinfunction "A2_4") (pintype "bidirectional"))
      (node (ref "U18") (pin "K3") (pinfunction "K3_K3") (pintype "bidirectional"))
    )
    (net (code "22") (name "ICE_MSP_SPI_DATA_X") (class "Default")
      (node (ref "U14") (pin "10") (pinfunction "PA.D/P2.5/UCB0SIMO/UCB0SDA/A7_10") (pintype "bidirectional"))
      (node (ref "U14") (pin "9") (pinfunction "PA.E/P2.6/UCB0SOMI/UCB0SCL_9") (pintype "bidirectional"))
      (node (ref "U16") (pin "1") (pinfunction "B2_1") (pintype "bidirectional"))
    )
    (net (code "23") (name "ICE_STM_FLASH_EN") (class "Default")
      (node (ref "R26") (pin "1") (pinfunction "1_1") (pintype "bidirectional"))
      (node (ref "U20") (pin "1") (pinfunction "IN1_1") (pintype "bidirectional"))
      (node (ref "U24") (pin "K3") (pinfunction "PF5_K3_K3") (pintype "bidirectional"))
    )
    (net (code "24") (name "ICE_STM_SPI_CLK") (class "Default")
      (node (ref "U18") (pin "L10") (pinfunction "SPI_SCK_L10_L10") (pintype "bidirectional"))
      (node (ref "U19") (pin "6") (pinfunction "CLK_6") (pintype "bidirectional"))
      (node (ref "U24") (pin "M6") (pinfunction "PB2_M6_M6") (pintype "bidirectional"))
    )
    (net (code "25") (name "ICE_STM_SPI_CS_") (class "Default")
      (node (ref "U18") (pin "K10") (pinfunction "SPI_SS_B_K10_K10") (pintype "bidirectional"))
      (node (ref "U20") (pin "6") (pinfunction "IN2_6") (pintype "bidirectional"))
      (node (ref "U24") (pin "R10") (pinfunction "PE12_R10_R10") (pintype "bidirectional"))
    )
    (net (code "26") (name "ICE_STM_SPI_D0") (class "Default")
      (node (ref "U18") (pin "L8") (pinfunction "L8_L8") (pintype "bidirectional"))
      (node (ref "U24") (pin "L3") (pinfunction "PF8_L3_L3") (pintype "bidirectional"))
    )
    (net (code "27") (name "ICE_STM_SPI_D1") (class "Default")
      (node (ref "U18") (pin "L7") (pinfunction "L7_L7") (pintype "bidirectional"))
      (node (ref "U24") (pin "L2") (pinfunction "PF9_L2_L2") (pintype "bidirectional"))
    )
    (net (code "28") (name "ICE_STM_SPI_D2") (class "Default")
      (node (ref "U18") (pin "K6") (pinfunction "K6_K6") (pintype "bidirectional"))
      (node (ref "U24") (pin "K1") (pinfunction "PF7_K1_K1") (pintype "bidirectional"))
    )
    (net (code "29") (name "ICE_STM_SPI_D3") (class "Default")
      (node (ref "U18") (pin "K7") (pinfunction "K7_K7") (pintype "bidirectional"))
      (node (ref "U24") (pin "K2") (pinfunction "PF6_K2_K2") (pintype "bidirectional"))
    )
    (net (code "30") (name "ICE_STM_SPI_D4") (class "Default")
      (node (ref "U18") (pin "K9") (pinfunction "SPI_SO_K9_K9") (pintype "bidirectional"))
      (node (ref "U19") (pin "5") (pinfunction "DI_5") (pintype "bidirectional"))
      (node (ref "U24") (pin "R8") (pinfunction "PE7_R8_R8") (pintype "bidirectional"))
    )
    (net (code "31") (name "ICE_STM_SPI_D5") (class "Default")
      (node (ref "U18") (pin "J9") (pinfunction "SPI_SI_J9_J9") (pintype "bidirectional"))
      (node (ref "U19") (pin "2") (pinfunction "DO_2") (pintype "bidirectional"))
      (node (ref "U24") (pin "P8") (pinfunction "PE8_P8_P8") (pintype "bidirectional"))
    )
    (net (code "32") (name "ICE_STM_SPI_D6") (class "Default")
      (node (ref "U18") (pin "J7") (pinfunction "J7_J7") (pintype "bidirectional"))
      (node (ref "U24") (pin "P9") (pinfunction "PE9_P9_P9") (pintype "bidirectional"))
    )
    (net (code "33") (name "ICE_STM_SPI_D7") (class "Default")
      (node (ref "U18") (pin "J8") (pinfunction "J8_J8") (pintype "bidirectional"))
      (node (ref "U24") (pin "R9") (pinfunction "PE10_R9_R9") (pintype "bidirectional"))
    )
    (net (code "34") (name "ICE_STM_SPI_D_READY") (class "Default")
      (node (ref "U18") (pin "L5") (pinfunction "L5_L5") (pintype "bidirectional"))
      (node (ref "U24") (pin "R2") (pinfunction "PA3_R2_R2") (pintype "bidirectional"))
    )
    (net (code "35") (name "IMG_CLK16MHZ") (class "Default")
      (node (ref "U21") (pin "4") (pinfunction "OUT_4") (pintype "bidirectional"))
      (node (ref "U22") (pin "D7") (pinfunction "EXTCLK_D7") (pintype "bidirectional"))
    )
    (net (code "36") (name "IMG_D0") (class "Default")
      (node (ref "U18") (pin "E8") (pinfunction "E8_E8") (pintype "bidirectional"))
      (node (ref "U22") (pin "G6") (pinfunction "DOUT0_G6") (pintype "bidirectional"))
    )
    (net (code "37") (name "IMG_D1") (class "Default")
      (node (ref "U18") (pin "D10") (pinfunction "D10_D10") (pintype "bidirectional"))
      (node (ref "U22") (pin "G5") (pinfunction "DOUT1_G5") (pintype "bidirectional"))
    )
    (net (code "38") (name "IMG_D2") (class "Default")
      (node (ref "U18") (pin "G11") (pinfunction "G11_G11") (pintype "bidirectional"))
      (node (ref "U22") (pin "H4") (pinfunction "DOUT2_H4") (pintype "bidirectional"))
    )
    (net (code "39") (name "IMG_D3") (class "Default")
      (node (ref "U18") (pin "G9") (pinfunction "G9_G9") (pintype "bidirectional"))
      (node (ref "U22") (pin "G4") (pinfunction "DOUT3_G4") (pintype "bidirectional"))
    )
    (net (code "40") (name "IMG_D4") (class "Default")
      (node (ref "U18") (pin "E9") (pinfunction "E9_E9") (pintype "bidirectional"))
      (node (ref "U22") (pin "F5") (pinfunction "DOUT4_F5") (pintype "bidirectional"))
    )
    (net (code "41") (name "IMG_D5") (class "Default")
      (node (ref "U18") (pin "K11") (pinfunction "K11_K11") (pintype "bidirectional"))
      (node (ref "U22") (pin "G3") (pinfunction "DOUT5_G3") (pintype "bidirectional"))
    )
    (net (code "42") (name "IMG_D6") (class "Default")
      (node (ref "U18") (pin "F9") (pinfunction "F9_F9") (pintype "bidirectional"))
      (node (ref "U22") (pin "F4") (pinfunction "DOUT6_F4") (pintype "bidirectional"))
    )
    (net (code "43") (name "IMG_D7") (class "Default")
      (node (ref "U18") (pin "G8") (pinfunction "G8_G8") (pintype "bidirectional"))
      (node (ref "U22") (pin "E4") (pinfunction "DOUT7_E4") (pintype "bidirectional"))
    )
    (net (code "44") (name "IMG_D8") (class "Default")
      (node (ref "U18") (pin "J10") (pinfunction "J10_J10") (pintype "bidirectional"))
      (node (ref "U22") (pin "F3") (pinfunction "DOUT8_F3") (pintype "bidirectional"))
    )
    (net (code "45") (name "IMG_D9") (class "Default")
      (node (ref "U18") (pin "J11") (pinfunction "J11_J11") (pintype "bidirectional"))
      (node (ref "U22") (pin "E3") (pinfunction "DOUT9_E3") (pintype "bidirectional"))
    )
    (net (code "46") (name "IMG_D10") (class "Default")
      (node (ref "U18") (pin "H11") (pinfunction "H11_H11") (pintype "bidirectional"))
      (node (ref "U22") (pin "D3") (pinfunction "DOUT10_D3") (pintype "bidirectional"))
    )
    (net (code "47") (name "IMG_D11") (class "Default")
      (node (ref "U18") (pin "H10") (pinfunction "H10_H10") (pintype "bidirectional"))
      (node (ref "U22") (pin "E2") (pinfunction "DOUT11_E2") (pintype "bidirectional"))
    )
    (net (code "48") (name "IMG_DCLK") (class "Default")
      (node (ref "U18") (pin "F11") (pinfunction "F11_F11") (pintype "bidirectional"))
      (node (ref "U22") (pin "E1") (pinfunction "PIXCLK_E1") (pintype "bidirectional"))
    )
    (net (code "49") (name "IMG_FV") (class "Default")
      (node (ref "U18") (pin "E11") (pinfunction "E11_E11") (pintype "bidirectional"))
      (node (ref "U22") (pin "B3") (pinfunction "FRAME_VALID_B3") (pintype "bidirectional"))
    )
    (net (code "50") (name "IMG_LV") (class "Default")
      (node (ref "U18") (pin "E10") (pinfunction "E10_E10") (pintype "bidirectional"))
      (node (ref "U22") (pin "C3") (pinfunction "LINE_VALID_C3") (pintype "bidirectional"))
    )
    (net (code "51") (name "IMG_RST_") (class "Default")
      (node (ref "R27") (pin "1") (pinfunction "1_1") (pintype "bidirectional"))
      (node (ref "U18") (pin "D11") (pinfunction "D11_D11") (pintype "bidirectional"))
      (node (ref "U22") (pin "C8") (pinfunction "RST__C8") (pintype "bidirectional"))
    )
    (net (code "52") (name "IMG_SCLK") (class "Default")
      (node (ref "U18") (pin "G10") (pinfunction "G10_G10") (pintype "bidirectional"))
      (node (ref "U22") (pin "D1") (pinfunction "SCLK_D1") (pintype "bidirectional"))
    )
    (net (code "53") (name "IMG_SDATA") (class "Default")
      (node (ref "R28") (pin "2") (pinfunction "2_2") (pintype "bidirectional"))
      (node (ref "U18") (pin "F10") (pinfunction "F10_F10") (pintype "bidirectional"))
      (node (ref "U22") (pin "B2") (pinfunction "SDATA_B2") (pintype "bidirectional"))
    )
    (net (code "54") (name "MOTION_SIGNAL") (class "Default")
      (node (ref "U14") (pin "19") (pinfunction "PA.3/P1.3/UCB0SOMI/UCB0SCL/MCLK/A3_19") (pintype "bidirectional"))
      (node (ref "U17") (pin "2") (pinfunction "OUT_2") (pintype "bidirectional"))
    )
    (net (code "55") (name "MSP_HOST_MODE_") (class "Default")
      (node (ref "U14") (pin "13") (pinfunction "PA.A/P2.2/TA1.1/A4_13") (pintype "bidirectional"))
      (node (ref "U24") (pin "A1") (pinfunction "PE3_A1_A1") (pintype "bidirectional"))
    )
    (net (code "56") (name "MSP_RST_") (class "Default")
      (node (ref "C22") (pin "1") (pinfunction "1_1") (pintype "bidirectional"))
      (node (ref "U14") (pin "4") (pinfunction "RST_/NMI/SBWTDIO_4") (pintype "bidirectional"))
      (node (ref "U15") (pin "1") (pinfunction "B2_1") (pintype "bidirectional"))
    )
    (net (code "57") (name "MSP_RST_X_") (class "Default")
      (node (ref "U15") (pin "4") (pinfunction "A2_4") (pintype "bidirectional"))
      (node (ref "U24") (pin "E2") (pinfunction "PF0_E2_E2") (pintype "bidirectional"))
    )
    (net (code "58") (name "MSP_SBW_EN") (class "Default")
      (node (ref "R17") (pin "2") (pinfunction "2_2") (pintype "bidirectional"))
      (node (ref "U15") (pin "6") (pinfunction "OE_6") (pintype "bidirectional"))
      (node (ref "U24") (pin "B1") (pinfunction "PE4_B1_B1") (pintype "bidirectional"))
    )
    (net (code "59") (name "MSP_TEST") (class "Default")
      (node (ref "U14") (pin "3") (pinfunction "TEST/SBWTCK_3") (pintype "bidirectional"))
      (node (ref "U15") (pin "8") (pinfunction "B1_8") (pintype "bidirectional"))
    )
    (net (code "60") (name "MSP_TEST_X") (class "Default")
      (node (ref "U15") (pin "5") (pinfunction "A1_5") (pintype "bidirectional"))
      (node (ref "U24") (pin "D2") (pinfunction "PI8_D2_D2") (pintype "bidirectional"))
    )
    (net (code "61") (name "Net-(C8-Pad1)") (class "Default")
      (node (ref "C8") (pin "1") (pinfunction "1_1") (pintype "bidirectional"))
      (node (ref "J6") (pin "1") (pinfunction "1_1") (pintype "bidirectional"))
      (node (ref "L1") (pin "2") (pinfunction "2_2") (pintype "bidirectional"))
      (node (ref "R11") (pin "1") (pinfunction "1_1") (pintype "bidirectional"))
    )
    (net (code "62") (name "Net-(C10-Pad1)") (class "Default")
      (node (ref "C10") (pin "1") (pinfunction "1_1") (pintype "bidirectional"))
      (node (ref "J7") (pin "1") (pinfunction "1_1") (pintype "bidirectional"))
      (node (ref "L2") (pin "2") (pinfunction "2_2") (pintype "bidirectional"))
      (node (ref "R13") (pin "1") (pinfunction "1_1") (pintype "bidirectional"))
    )
    (net (code "63") (name "Net-(C12-Pad1)") (class "Default")
      (node (ref "C12") (pin "1") (pinfunction "1_1") (pintype "bidirectional"))
      (node (ref "J8") (pin "1") (pinfunction "1_1") (pintype "bidirectional"))
      (node (ref "L3") (pin "2") (pinfunction "2_2") (pintype "bidirectional"))
      (node (ref "R15") (pin "1") (pinfunction "1_1") (pintype "bidirectional"))
    )
    (net (code "64") (name "Net-(D1-A)") (class "Default")
      (node (ref "C4") (pin "1") (pinfunction "1_1") (pintype "bidirectional"))
      (node (ref "D1") (pin "1") (pinfunction "A_1") (pintype "bidirectional"))
      (node (ref "J2") (pin "1") (pinfunction "1_1") (pintype "bidirectional"))
      (node (ref "U2") (pin "3") (pinfunction "VOUT_3") (pintype "bidirectional"))
    )
    (net (code "65") (name "Net-(FB1-P$1)") (class "Default")
      (node (ref "FB1") (pin "1") (pinfunction "P$1_1") (pintype "bidirectional"))
      (node (ref "J11") (pin "A4") (pinfunction "VBUS_A4") (pintype "bidirectional"))
      (node (ref "J11") (pin "A9") (pinfunction "VBUS_A9") (pintype "bidirectional"))
      (node (ref "J11") (pin "B4") (pinfunction "VBUS_B4") (pintype "bidirectional"))
      (node (ref "J11") (pin "B9") (pinfunction "VBUS_B9") (pintype "bidirectional"))
      (node (ref "U25") (pin "4") (pinfunction "IO3_4") (pintype "bidirectional"))
      (node (ref "U25") (pin "5") (pinfunction "VDD_5") (pintype "bidirectional"))
      (node (ref "U25") (pin "6") (pinfunction "IO4_6") (pintype "bidirectional"))
    )
    (net (code "66") (name "Net-(J3-Pad1)") (class "Default")
      (node (ref "J3") (pin "1") (pinfunction "1_1") (pintype "bidirectional"))
      (node (ref "Q1") (pin "1") (pinfunction "D_1") (pintype "bidirectional"))
      (node (ref "Q1") (pin "2") (pinfunction "D_2") (pintype "bidirectional"))
      (node (ref "Q1") (pin "5") (pinfunction "D_5") (pintype "bidirectional"))
      (node (ref "Q1") (pin "6") (pinfunction "D_6") (pintype "bidirectional"))
      (node (ref "Q1") (pin "7") (pinfunction "D_7") (pintype "bidirectional"))
    )
    (net (code "67") (name "Net-(J4-Pad2)") (class "Default")
      (node (ref "J4") (pin "2") (pinfunction "2_2") (pintype "bidirectional"))
      (node (ref "Q2") (pin "4") (pinfunction "S_4") (pintype "bidirectional"))
      (node (ref "Q2") (pin "8") (pinfunction "S_8") (pintype "bidirectional"))
      (node (ref "Q3") (pin "4") (pinfunction "S_4") (pintype "bidirectional"))
      (node (ref "Q3") (pin "8") (pinfunction "S_8") (pintype "bidirectional"))
      (node (ref "R8") (pin "2") (pinfunction "2_2") (pintype "bidirectional"))
    )
    (net (code "68") (name "Net-(J11-CC1)") (class "Default")
      (node (ref "J11") (pin "A5") (pinfunction "CC1_A5") (pintype "bidirectional"))
      (node (ref "R39") (pin "1") (pinfunction "1_1") (pintype "bidirectional"))
    )
    (net (code "69") (name "Net-(J11-CC2)") (class "Default")
      (node (ref "J11") (pin "B5") (pinfunction "CC2_B5") (pintype "bidirectional"))
      (node (ref "R40") (pin "1") (pinfunction "1_1") (pintype "bidirectional"))
    )
    (net (code "70") (name "Net-(LED1-PadC)") (class "Default")
      (node (ref "LED1") (pin "C") (pinfunction "C_C") (pintype "bidirectional"))
      (node (ref "R18") (pin "1") (pinfunction "1_1") (pintype "bidirectional"))
    )
    (net (code "71") (name "Net-(LED2-PadC)") (class "Default")
      (node (ref "LED2") (pin "C") (pinfunction "C_C") (pintype "bidirectional"))
      (node (ref "R19") (pin "1") (pinfunction "1_1") (pintype "bidirectional"))
    )
    (net (code "72") (name "Net-(LED3-PadC)") (class "Default")
      (node (ref "LED3") (pin "C") (pinfunction "C_C") (pintype "bidirectional"))
      (node (ref "R20") (pin "1") (pinfunction "1_1") (pintype "bidirectional"))
    )
    (net (code "73") (name "Net-(LED4-PadC)") (class "Default")
      (node (ref "LED4") (pin "C") (pinfunction "C_C") (pintype "bidirectional"))
      (node (ref "R21") (pin "1") (pinfunction "1_1") (pintype "bidirectional"))
    )
    (net (code "74") (name "Net-(LED5-PadC)") (class "Default")
      (node (ref "LED5") (pin "C") (pinfunction "C_C") (pintype "bidirectional"))
      (node (ref "R34") (pin "1") (pinfunction "1_1") (pintype "bidirectional"))
    )
    (net (code "75") (name "Net-(LED6-PadC)") (class "Default")
      (node (ref "LED6") (pin "C") (pinfunction "C_C") (pintype "bidirectional"))
      (node (ref "R35") (pin "1") (pinfunction "1_1") (pintype "bidirectional"))
    )
    (net (code "76") (name "Net-(LED7-PadC)") (class "Default")
      (node (ref "LED7") (pin "C") (pinfunction "C_C") (pintype "bidirectional"))
      (node (ref "R36") (pin "1") (pinfunction "1_1") (pintype "bidirectional"))
    )
    (net (code "77") (name "Net-(LED8-PadC)") (class "Default")
      (node (ref "LED8") (pin "C") (pinfunction "C_C") (pintype "bidirectional"))
      (node (ref "R37") (pin "1") (pinfunction "1_1") (pintype "bidirectional"))
    )
    (net (code "78") (name "Net-(Q1-G)") (class "Default")
      (node (ref "Q1") (pin "3") (pinfunction "G_3") (pintype "bidirectional"))
      (node (ref "R5") (pin "1") (pinfunction "1_1") (pintype "bidirectional"))
    )
    (net (code "79") (name "Net-(Q2-G)") (class "Default")
      (node (ref "Q2") (pin "3") (pinfunction "G_3") (pintype "bidirectional"))
      (node (ref "Q3") (pin "1") (pinfunction "D_1") (pintype "bidirectional"))
      (node (ref "Q3") (pin "2") (pinfunction "D_2") (pintype "bidirectional"))
      (node (ref "Q3") (pin "5") (pinfunction "D_5") (pintype "bidirectional"))
      (node (ref "Q3") (pin "6") (pinfunction "D_6") (pintype "bidirectional"))
      (node (ref "Q3") (pin "7") (pinfunction "D_7") (pintype "bidirectional"))
      (node (ref "R10") (pin "1") (pinfunction "1_1") (pintype "bidirectional"))
    )
    (net (code "80") (name "Net-(U1-PR1)") (class "Default")
      (node (ref "R2") (pin "2") (pinfunction "2_2") (pintype "bidirectional"))
      (node (ref "R3") (pin "1") (pinfunction "1_1") (pintype "bidirectional"))
      (node (ref "U1") (pin "4") (pinfunction "PR1_4") (pintype "bidirectional"))
    )
    (net (code "81") (name "Net-(U3-OUT)") (class "Default")
      (node (ref "R5") (pin "2") (pinfunction "2_2") (pintype "bidirectional"))
      (node (ref "U3") (pin "4") (pinfunction "OUT_4") (pintype "bidirectional"))
    )
    (net (code "82") (name "Net-(U4-PROG)") (class "Default")
      (node (ref "R6") (pin "2") (pinfunction "2_2") (pintype "bidirectional"))
      (node (ref "U4") (pin "5") (pinfunction "PROG_5") (pintype "bidirectional"))
    )
    (net (code "83") (name "Net-(U5-OUT)") (class "Default")
      (node (ref "R7") (pin "1") (pinfunction "1_1") (pintype "bidirectional"))
      (node (ref "U5") (pin "4") (pinfunction "OUT_4") (pintype "bidirectional"))
    )
    (net (code "84") (name "Net-(U7-FB)") (class "Default")
      (node (ref "R11") (pin "2") (pinfunction "2_2") (pintype "bidirectional"))
      (node (ref "R12") (pin "1") (pinfunction "1_1") (pintype "bidirectional"))
      (node (ref "U7") (pin "5") (pinfunction "FB_5") (pintype "bidirectional"))
    )
    (net (code "85") (name "Net-(U7-SW)") (class "Default")
      (node (ref "L1") (pin "1") (pinfunction "1_1") (pintype "bidirectional"))
      (node (ref "U7") (pin "2") (pinfunction "SW_2") (pintype "bidirectional"))
    )
    (net (code "86") (name "Net-(U8-FB)") (class "Default")
      (node (ref "R13") (pin "2") (pinfunction "2_2") (pintype "bidirectional"))
      (node (ref "R14") (pin "1") (pinfunction "1_1") (pintype "bidirectional"))
      (node (ref "U8") (pin "5") (pinfunction "FB_5") (pintype "bidirectional"))
    )
    (net (code "87") (name "Net-(U8-SW)") (class "Default")
      (node (ref "L2") (pin "1") (pinfunction "1_1") (pintype "bidirectional"))
      (node (ref "U8") (pin "2") (pinfunction "SW_2") (pintype "bidirectional"))
    )
    (net (code "88") (name "Net-(U9-FB)") (class "Default")
      (node (ref "R15") (pin "2") (pinfunction "2_2") (pintype "bidirectional"))
      (node (ref "R16") (pin "1") (pinfunction "1_1") (pintype "bidirectional"))
      (node (ref "U9") (pin "5") (pinfunction "FB_5") (pintype "bidirectional"))
    )
    (net (code "89") (name "Net-(U9-SW)") (class "Default")
      (node (ref "L3") (pin "1") (pinfunction "1_1") (pintype "bidirectional"))
      (node (ref "U9") (pin "2") (pinfunction "SW_2") (pintype "bidirectional"))
    )
    (net (code "90") (name "Net-(U14C-PA.8{slash}P2.0{slash}UCA0TXD{slash}UCA0SIMO{slash}XOUT)") (class "Default")
      (node (ref "C19") (pin "1") (pinfunction "1_1") (pintype "bidirectional"))
      (node (ref "U14") (pin "8") (pinfunction "PA.8/P2.0/UCA0TXD/UCA0SIMO/XOUT_8") (pintype "bidirectional"))
      (node (ref "X1") (pin "2") (pinfunction "B_2") (pintype "bidirectional"))
    )
    (net (code "91") (name "Net-(U14C-PA.9{slash}P2.1{slash}UCA0RXD{slash}UCA0SOMI{slash}XIN)") (class "Default")
      (node (ref "C18") (pin "1") (pinfunction "1_1") (pintype "bidirectional"))
      (node (ref "U14") (pin "7") (pinfunction "PA.9/P2.1/UCA0RXD/UCA0SOMI/XIN_7") (pintype "bidirectional"))
      (node (ref "X1") (pin "1") (pinfunction "A_1") (pintype "bidirectional"))
    )
    (net (code "92") (name "Net-(U19-CS_)") (class "Default")
      (node (ref "U19") (pin "1") (pinfunction "CS__1") (pintype "bidirectional"))
      (node (ref "U20") (pin "4") (pinfunction "OUT_4") (pintype "bidirectional"))
    )
    (net (code "93") (name "Net-(U24J-OTG_HS_REXT_J15)") (class "Default")
      (node (ref "R38") (pin "2") (pinfunction "2_2") (pintype "bidirectional"))
      (node (ref "U24") (pin "J15") (pinfunction "OTG_HS_REXT_J15_J15") (pintype "bidirectional"))
    )
    (net (code "94") (name "Net-(U24J-VDD12OTGHS_J14)") (class "Default")
      (node (ref "C67") (pin "1") (pinfunction "1_1") (pintype "bidirectional"))
      (node (ref "U24") (pin "J14") (pinfunction "VDD12OTGHS_J14_J14") (pintype "bidirectional"))
    )
    (net (code "95") (name "Net-(U24K-VCAP_1_M10)") (class "Default")
      (node (ref "C84") (pin "1") (pinfunction "1_1") (pintype "bidirectional"))
      (node (ref "U24") (pin "M10") (pinfunction "VCAP_1_M10_M10") (pintype "bidirectional"))
    )
    (net (code "96") (name "Net-(U24K-VCAP_2_F13)") (class "Default")
      (node (ref "C85") (pin "1") (pinfunction "1_1") (pintype "bidirectional"))
      (node (ref "U24") (pin "F13") (pinfunction "VCAP_2_F13_F13") (pintype "bidirectional"))
    )
    (net (code "97") (name "RAM_A0") (class "Default")
      (node (ref "U18") (pin "D5") (pinfunction "D5_D5") (pintype "bidirectional"))
      (node (ref "U23") (pin "H7") (pinfunction "A0_H7") (pintype "bidirectional"))
    )
    (net (code "98") (name "RAM_A1") (class "Default")
      (node (ref "U18") (pin "B3") (pinfunction "B3_B3") (pintype "bidirectional"))
      (node (ref "U23") (pin "H8") (pinfunction "A1_H8") (pintype "bidirectional"))
    )
    (net (code "99") (name "RAM_A2") (class "Default")
      (node (ref "U18") (pin "B2") (pinfunction "B2_B2") (pintype "bidirectional"))
      (node (ref "U23") (pin "J8") (pinfunction "A2_J8") (pintype "bidirectional"))
    )
    (net (code "100") (name "RAM_A3") (class "Default")
      (node (ref "U18") (pin "A1") (pinfunction "A1_A1") (pintype "bidirectional"))
      (node (ref "U23") (pin "J7") (pinfunction "A3_J7") (pintype "bidirectional"))
    )
    (net (code "101") (name "RAM_A4") (class "Default")
      (node (ref "U18") (pin "B1") (pinfunction "B1_B1") (pintype "bidirectional"))
      (node (ref "U23") (pin "J3") (pinfunction "A4_J3") (pintype "bidirectional"))
    )
    (net (code "102") (name "RAM_A5") (class "Default")
      (node (ref "U18") (pin "C2") (pinfunction "C2_C2") (pintype "bidirectional"))
      (node (ref "U23") (pin "J2") (pinfunction "A5_J2") (pintype "bidirectional"))
    )
    (net (code "103") (name "RAM_A6") (class "Default")
      (node (ref "U18") (pin "C4") (pinfunction "C4_C4") (pintype "bidirectional"))
      (node (ref "U23") (pin "H3") (pinfunction "A6_H3") (pintype "bidirectional"))
    )
    (net (code "104") (name "RAM_A7") (class "Default")
      (node (ref "U18") (pin "D2") (pinfunction "D2_D2") (pintype "bidirectional"))
      (node (ref "U23") (pin "H2") (pinfunction "A7_H2") (pintype "bidirectional"))
    )
    (net (code "105") (name "RAM_A8") (class "Default")
      (node (ref "U18") (pin "C1") (pinfunction "C1_C1") (pintype "bidirectional"))
      (node (ref "U23") (pin "H1") (pinfunction "A8_H1") (pintype "bidirectional"))
    )
    (net (code "106") (name "RAM_A9") (class "Default")
      (node (ref "U18") (pin "C3") (pinfunction "C3_C3") (pintype "bidirectional"))
      (node (ref "U23") (pin "G3") (pinfunction "A9_G3") (pintype "bidirectional"))
    )
    (net (code "107") (name "RAM_A10") (class "Default")
      (node (ref "U18") (pin "A2") (pinfunction "A2_A2") (pintype "bidirectional"))
      (node (ref "U23") (pin "H9") (pinfunction "A10_H9") (pintype "bidirectional"))
    )
    (net (code "108") (name "RAM_A11") (class "Default")
      (node (ref "U18") (pin "D1") (pinfunction "D1_D1") (pintype "bidirectional"))
      (node (ref "U23") (pin "G2") (pinfunction "A11_G2") (pintype "bidirectional"))
    )
    (net (code "109") (name "RAM_BA0") (class "Default")
      (node (ref "U18") (pin "C7") (pinfunction "C7_C7") (pintype "bidirectional"))
      (node (ref "U23") (pin "G7") (pinfunction "BA0_G7") (pintype "bidirectional"))
    )
    (net (code "110") (name "RAM_BA1") (class "Default")
      (node (ref "U18") (pin "B4") (pinfunction "B4_B4") (pintype "bidirectional"))
      (node (ref "U23") (pin "G8") (pinfunction "BA1_G8") (pintype "bidirectional"))
    )
    (net (code "111") (name "RAM_CAS_") (class "Default")
      (node (ref "U18") (pin "D7") (pinfunction "D7_D7") (pintype "bidirectional"))
      (node (ref "U23") (pin "F7") (pinfunction "~{CAS}_F7") (pintype "bidirectional"))
    )
    (net (code "112") (name "RAM_CKE") (class "Default")
      (node (ref "U18") (pin "D3") (pinfunction "D3_D3") (pintype "bidirectional"))
      (node (ref "U23") (pin "F3") (pinfunction "CKE_F3") (pintype "bidirectional"))
    )
    (net (code "113") (name "RAM_CLK") (class "Default")
      (node (ref "U18") (pin "E1") (pinfunction "E1_E1") (pintype "bidirectional"))
      (node (ref "U23") (pin "F2") (pinfunction "CLK_F2") (pintype "bidirectional"))
    )
    (net (code "114") (name "RAM_CS_") (class "Default")
      (node (ref "U18") (pin "A3") (pinfunction "A3_A3") (pintype "bidirectional"))
      (node (ref "U23") (pin "G9") (pinfunction "~{CS}_G9") (pintype "bidirectional"))
    )
    (net (code "115") (name "RAM_DQ0") (class "Default")
      (node (ref "U18") (pin "A9") (pinfunction "A9_A9") (pintype "bidirectional"))
      (node (ref "U23") (pin "A8") (pinfunction "DQ0_A8") (pintype "bidirectional"))
    )
    (net (code "116") (name "RAM_DQ1") (class "Default")
      (node (ref "U18") (pin "A8") (pinfunction "A8_A8") (pintype "bidirectional"))
      (node (ref "U23") (pin "B9") (pinfunction "DQ1_B9") (pintype "bidirectional"))
    )
    (net (code "117") (name "RAM_DQ2") (class "Default")
      (node (ref "U18") (pin "B9") (pinfunction "B9_B9") (pintype "bidirectional"))
      (node (ref "U23") (pin "B8") (pinfunction "DQ2_B8") (pintype "bidirectional"))
    )
    (net (code "118") (name "RAM_DQ3") (class "Default")
      (node (ref "U18") (pin "A7") (pinfunction "A7_A7") (pintype "bidirectional"))
      (node (ref "U23") (pin "C9") (pinfunction "DQ3_C9") (pintype "bidirectional"))
    )
    (net (code "119") (name "RAM_DQ4") (class "Default")
      (node (ref "U18") (pin "B8") (pinfunction "B8_B8") (pintype "bidirectional"))
      (node (ref "U23") (pin "C8") (pinfunction "DQ4_C8") (pintype "bidirectional"))
    )
    (net (code "120") (name "RAM_DQ5") (class "Default")
      (node (ref "U18") (pin "A6") (pinfunction "A6_A6") (pintype "bidirectional"))
      (node (ref "U23") (pin "D9") (pinfunction "DQ5_D9") (pintype "bidirectional"))
    )
    (net (code "121") (name "RAM_DQ6") (class "Default")
      (node (ref "U18") (pin "B7") (pinfunction "B7_B7") (pintype "bidirectional"))
      (node (ref "U23") (pin "D8") (pinfunction "DQ6_D8") (pintype "bidirectional"))
    )
    (net (code "122") (name "RAM_DQ7") (class "Default")
      (node (ref "U18") (pin "A5") (pinfunction "A5_A5") (pintype "bidirectional"))
      (node (ref "U23") (pin "E9") (pinfunction "DQ7_E9") (pintype "bidirectional"))
    )
    (net (code "123") (name "RAM_DQ8") (class "Default")
      (node (ref "U18") (pin "F2") (pinfunction "F2_F2") (pintype "bidirectional"))
      (node (ref "U23") (pin "E1") (pinfunction "DQ8_E1") (pintype "bidirectional"))
    )
    (net (code "124") (name "RAM_DQ9") (class "Default")
      (node (ref "U18") (pin "G2") (pinfunction "G2_G2") (pintype "bidirectional"))
      (node (ref "U23") (pin "D2") (pinfunction "DQ9_D2") (pintype "bidirectional"))
    )
    (net (code "125") (name "RAM_DQ10") (class "Default")
      (node (ref "U18") (pin "F1") (pinfunction "F1_F1") (pintype "bidirectional"))
      (node (ref "U23") (pin "D1") (pinfunction "DQ10_D1") (pintype "bidirectional"))
    )
    (net (code "126") (name "RAM_DQ11") (class "Default")
      (node (ref "U18") (pin "H2") (pinfunction "H2_H2") (pintype "bidirectional"))
      (node (ref "U23") (pin "C2") (pinfunction "DQ11_C2") (pintype "bidirectional"))
    )
    (net (code "127") (name "RAM_DQ12") (class "Default")
      (node (ref "U18") (pin "G1") (pinfunction "G1_G1") (pintype "bidirectional"))
      (node (ref "U23") (pin "C1") (pinfunction "DQ12_C1") (pintype "bidirectional"))
    )
    (net (code "128") (name "RAM_DQ13") (class "Default")
      (node (ref "U18") (pin "J2") (pinfunction "J2_J2") (pintype "bidirectional"))
      (node (ref "U23") (pin "B2") (pinfunction "DQ13_B2") (pintype "bidirectional"))
    )
    (net (code "129") (name "RAM_DQ14") (class "Default")
      (node (ref "U18") (pin "H1") (pinfunction "H1_H1") (pintype "bidirectional"))
      (node (ref "U23") (pin "B1") (pinfunction "DQ14_B1") (pintype "bidirectional"))
    )
    (net (code "130") (name "RAM_DQ15") (class "Default")
      (node (ref "U18") (pin "J1") (pinfunction "J1_J1") (pintype "bidirectional"))
      (node (ref "U23") (pin "A2") (pinfunction "DQ15_A2") (pintype "bidirectional"))
    )
    (net (code "131") (name "RAM_DQM0") (class "Default")
      (node (ref "U18") (pin "B6") (pinfunction "B6_B6") (pintype "bidirectional"))
      (node (ref "U23") (pin "E8") (pinfunction "LDQM_E8") (pintype "bidirectional"))
    )
    (net (code "132") (name "RAM_DQM1") (class "Default")
      (node (ref "U18") (pin "E2") (pinfunction "E2_E2") (pintype "bidirectional"))
      (node (ref "U23") (pin "F1") (pinfunction "UDQM_F1") (pintype "bidirectional"))
    )
    (net (code "133") (name "RAM_RAS_") (class "Default")
      (node (ref "U18") (pin "B5") (pinfunction "B5_B5") (pintype "bidirectional"))
      (node (ref "U23") (pin "F8") (pinfunction "~{RAS}_F8") (pintype "bidirectional"))
    )
    (net (code "134") (name "RAM_WE_") (class "Default")
      (node (ref "U18") (pin "A4") (pinfunction "A4_A4") (pintype "bidirectional"))
      (node (ref "U23") (pin "F9") (pinfunction "~{WE}_F9") (pintype "bidirectional"))
    )
    (net (code "135") (name "SD_CLK") (class "Default")
      (node (ref "J10") (pin "CLK") (pinfunction "CLK_CLK") (pintype "bidirectional"))
      (node (ref "U18") (pin "L3") (pinfunction "L3_L3") (pintype "bidirectional"))
    )
    (net (code "136") (name "SD_CMD") (class "Default")
      (node (ref "J10") (pin "CMD") (pinfunction "CMD_CMD") (pintype "bidirectional"))
      (node (ref "R29") (pin "1") (pinfunction "1_1") (pintype "bidirectional"))
      (node (ref "U18") (pin "K4") (pinfunction "K4_K4") (pintype "bidirectional"))
    )
    (net (code "137") (name "SD_DAT0") (class "Default")
      (node (ref "J10") (pin "DAT0") (pinfunction "DAT0_DAT0") (pintype "bidirectional"))
      (node (ref "R30") (pin "1") (pinfunction "1_1") (pintype "bidirectional"))
      (node (ref "U18") (pin "L2") (pinfunction "L2_L2") (pintype "bidirectional"))
    )
    (net (code "138") (name "SD_DAT1") (class "Default")
      (node (ref "J10") (pin "DAT1") (pinfunction "DAT1_DAT1") (pintype "bidirectional"))
      (node (ref "R31") (pin "1") (pinfunction "1_1") (pintype "bidirectional"))
      (node (ref "U18") (pin "L1") (pinfunction "L1_L1") (pintype "bidirectional"))
    )
    (net (code "139") (name "SD_DAT2") (class "Default")
      (node (ref "J10") (pin "DAT2") (pinfunction "DAT2_DAT2") (pintype "bidirectional"))
      (node (ref "R32") (pin "1") (pinfunction "1_1") (pintype "bidirectional"))
      (node (ref "U18") (pin "K5") (pinfunction "K5_K5") (pintype "bidirectional"))
    )
    (net (code "140") (name "SD_DAT3") (class "Default")
      (node (ref "J10") (pin "DAT3") (pinfunction "DAT3_DAT3") (pintype "bidirectional"))
      (node (ref "R33") (pin "1") (pinfunction "1_1") (pintype "bidirectional"))
      (node (ref "U18") (pin "L4") (pinfunction "L4_L4") (pintype "bidirectional"))
    )
    (net (code "141") (name "STM_CLK16MHZ") (class "Default")
      (node (ref "U24") (pin "G1") (pinfunction "PH0_G1_G1") (pintype "bidirectional"))
      (node (ref "X3") (pin "2") (pinfunction "OUT_2") (pintype "bidirectional"))
    )
    (net (code "142") (name "STM_LED0") (class "Default")
      (node (ref "LED8") (pin "A") (pinfunction "A_A") (pintype "bidirectional"))
      (node (ref "U24") (pin "R12") (pinfunction "PB10_R12_R12") (pintype "bidirectional"))
    )
    (net (code "143") (name "STM_LED1") (class "Default")
      (node (ref "LED7") (pin "A") (pinfunction "A_A") (pintype "bidirectional"))
      (node (ref "U24") (pin "P12") (pinfunction "PB12_P12_P12") (pintype "bidirectional"))
    )
    (net (code "144") (name "STM_LED2") (class "Default")
      (node (ref "LED6") (pin "A") (pinfunction "A_A") (pintype "bidirectional"))
      (node (ref "U24") (pin "R13") (pinfunction "PB11_R13_R13") (pintype "bidirectional"))
    )
    (net (code "145") (name "STM_LED3") (class "Default")
      (node (ref "LED5") (pin "A") (pinfunction "A_A") (pintype "bidirectional"))
      (node (ref "U24") (pin "P13") (pinfunction "PB13_P13_P13") (pintype "bidirectional"))
    )
    (net (code "146") (name "STM_RST_") (class "Default")
      (node (ref "C66") (pin "1") (pinfunction "1_1") (pintype "bidirectional"))
      (node (ref "U24") (pin "J1") (pinfunction "NRST_J1_J1") (pintype "bidirectional"))
    )
    (net (code "147") (name "STM_SWCLK") (class "Default")
      (node (ref "H1") (pin "4") (pinfunction "4_4") (pintype "bidirectional"))
      (node (ref "U24") (pin "A14") (pinfunction "PA14_A14_A14") (pintype "bidirectional"))
    )
    (net (code "148") (name "STM_SWDIO") (class "Default")
      (node (ref "H1") (pin "6") (pinfunction "6_6") (pintype "bidirectional"))
      (node (ref "U24") (pin "A15") (pinfunction "PA13_A15_A15") (pintype "bidirectional"))
    )
    (net (code "149") (name "USB_D+") (class "Default")
      (node (ref "J11") (pin "A6") (pinfunction "D+_A6") (pintype "bidirectional"))
      (node (ref "J11") (pin "B6") (pinfunction "D+_B6") (pintype "bidirectional"))
      (node (ref "U24") (pin "R15") (pinfunction "PB15_R15_R15") (pintype "bidirectional"))
      (node (ref "U25") (pin "3") (pinfunction "IO2_3") (pintype "bidirectional"))
    )
    (net (code "150") (name "USB_D-") (class "Default")
      (node (ref "J11") (pin "A7") (pinfunction "D-_A7") (pintype "bidirectional"))
      (node (ref "J11") (pin "B7") (pinfunction "D-_B7") (pintype "bidirectional"))
      (node (ref "U24") (pin "R14") (pinfunction "PB14_R14_R14") (pintype "bidirectional"))
      (node (ref "U25") (pin "1") (pinfunction "IO1_1") (pintype "bidirectional"))
    )
    (net (code "151") (name "VCCPLL0") (class "Default")
      (node (ref "C42") (pin "1") (pinfunction "1_1") (pintype "bidirectional"))
      (node (ref "C43") (pin "1") (pinfunction "1_1") (pintype "bidirectional"))
      (node (ref "R23") (pin "1") (pinfunction "1_1") (pintype "bidirectional"))
      (node (ref "U18") (pin "J6") (pinfunction "VCCPLL0_J6_J6") (pintype "bidirectional"))
    )
    (net (code "152") (name "VCCPLL1") (class "Default")
      (node (ref "C39") (pin "1") (pinfunction "1_1") (pintype "bidirectional"))
      (node (ref "C40") (pin "1") (pinfunction "1_1") (pintype "bidirectional"))
      (node (ref "R22") (pin "1") (pinfunction "1_1") (pintype "bidirectional"))
      (node (ref "U18") (pin "C6") (pinfunction "VCCPLL1_C6_C6") (pintype "bidirectional"))
    )
    (net (code "153") (name "VDD_A") (class "Default")
      (node (ref "C2") (pin "1") (pinfunction "1_1") (pintype "bidirectional"))
      (node (ref "C3") (pin "1") (pinfunction "1_1") (pintype "bidirectional"))
      (node (ref "D1") (pin "2") (pinfunction "C_2") (pintype "bidirectional"))
      (node (ref "Q1") (pin "4") (pinfunction "S_4") (pintype "bidirectional"))
      (node (ref "Q1") (pin "8") (pinfunction "S_8") (pintype "bidirectional"))
      (node (ref "U1") (pin "2") (pinfunction "VOUT_2") (pintype "bidirectional"))
      (node (ref "U1") (pin "7") (pinfunction "VOUT_7") (pintype "bidirectional"))
      (node (ref "U2") (pin "1") (pinfunction "EN_1") (pintype "bidirectional"))
      (node (ref "U2") (pin "4") (pinfunction "VIN_4") (pintype "bidirectional"))
      (node (ref "U3") (pin "3") (pinfunction "VDD_3") (pintype "bidirectional"))
      (node (ref "U3") (pin "5") (pinfunction "VDD_5") (pintype "bidirectional"))
    )
    (net (code "154") (name "VDD_A_3V3") (class "Default")
      (node (ref "C17") (pin "1") (pinfunction "1_1") (pintype "bidirectional"))
      (node (ref "C20") (pin "1") (pinfunction "1_1") (pintype "bidirectional"))
      (node (ref "C21") (pin "1") (pinfunction "1_1") (pintype "bidirectional"))
      (node (ref "C23") (pin "1") (pinfunction "1_1") (pintype "bidirectional"))
      (node (ref "C25") (pin "1") (pinfunction "1_1") (pintype "bidirectional"))
      (node (ref "C27") (pin "1") (pinfunction "1_1") (pintype "bidirectional"))
      (node (ref "J2") (pin "2") (pinfunction "2_2") (pintype "bidirectional"))
      (node (ref "U13") (pin "1") (pinfunction "VIN_1") (pintype "bidirectional"))
      (node (ref "U14") (pin "5") (pinfunction "VDD_5") (pintype "bidirectional"))
      (node (ref "U15") (pin "7") (pinfunction "VCCB_7") (pintype "bidirectional"))
      (node (ref "U16") (pin "7") (pinfunction "VCCB_7") (pintype "bidirectional"))
      (node (ref "U17") (pin "1") (pinfunction "VDD_1") (pintype "bidirectional"))
    )
    (net (code "155") (name "VDD_B") (class "Default")
      (node (ref "C11") (pin "1") (pinfunction "1_1") (pintype "bidirectional"))
      (node (ref "C13") (pin "1") (pinfunction "1_1") (pintype "bidirectional"))
      (node (ref "C9") (pin "1") (pinfunction "1_1") (pintype "bidirectional"))
      (node (ref "J3") (pin "2") (pinfunction "2_2") (pintype "bidirectional"))
      (node (ref "U7") (pin "3") (pinfunction "VIN_3") (pintype "bidirectional"))
      (node (ref "U7") (pin "4") (pinfunction "EN_4") (pintype "bidirectional"))
      (node (ref "U8") (pin "3") (pinfunction "VIN_3") (pintype "bidirectional"))
      (node (ref "U8") (pin "4") (pinfunction "EN_4") (pintype "bidirectional"))
      (node (ref "U9") (pin "3") (pinfunction "VIN_3") (pintype "bidirectional"))
      (node (ref "U9") (pin "4") (pinfunction "EN_4") (pintype "bidirectional"))
    )
    (net (code "156") (name "VDD_BAT") (class "Default")
      (node (ref "C6") (pin "1") (pinfunction "1_1") (pintype "bidirectional"))
      (node (ref "J4") (pin "1") (pinfunction "1_1") (pintype "bidirectional"))
      (node (ref "U1") (pin "6") (pinfunction "VIN2_6") (pintype "bidirectional"))
      (node (ref "U4") (pin "3") (pinfunction "VBAT_3") (pintype "bidirectional"))
      (node (ref "U5") (pin "1") (pinfunction "VDD_1") (pintype "bidirectional"))
      (node (ref "U5") (pin "5") (pinfunction "VDD_5") (pintype "bidirectional"))
    )
    (net (code "157") (name "VDD_BAT_IN") (class "Default")
      (node (ref "J5") (pin "L") (pinfunction "L_L") (pintype "bidirectional"))
      (node (ref "Q2") (pin "1") (pinfunction "D_1") (pintype "bidirectional"))
      (node (ref "Q2") (pin "2") (pinfunction "D_2") (pintype "bidirectional"))
      (node (ref "Q2") (pin "5") (pinfunction "D_5") (pintype "bidirectional"))
      (node (ref "Q2") (pin "6") (pinfunction "D_6") (pintype "bidirectional"))
      (node (ref "Q2") (pin "7") (pinfunction "D_7") (pintype "bidirectional"))
      (node (ref "Q3") (pin "3") (pinfunction "G_3") (pintype "bidirectional"))
      (node (ref "R8") (pin "1") (pinfunction "1_1") (pintype "bidirectional"))
      (node (ref "U6") (pin "1") (pinfunction "1_1") (pintype "bidirectional"))
    )
    (net (code "158") (name "VDD_B_1V2") (class "Default")
      (node (ref "C28") (pin "1") (pinfunction "1_1") (pintype "bidirectional"))
      (node (ref "C29") (pin "1") (pinfunction "1_1") (pintype "bidirectional"))
      (node (ref "C30") (pin "1") (pinfunction "1_1") (pintype "bidirectional"))
      (node (ref "C31") (pin "1") (pinfunction "1_1") (pintype "bidirectional"))
      (node (ref "J6") (pin "2") (pinfunction "2_2") (pintype "bidirectional"))
      (node (ref "R22") (pin "2") (pinfunction "2_2") (pintype "bidirectional"))
      (node (ref "R23") (pin "2") (pinfunction "2_2") (pintype "bidirectional"))
      (node (ref "U18") (pin "D4") (pinfunction "VCC_D4_D4") (pintype "bidirectional"))
      (node (ref "U18") (pin "D8") (pinfunction "VCC_D8_D8") (pintype "bidirectional"))
      (node (ref "U18") (pin "H4") (pinfunction "VCC_H4_H4") (pintype "bidirectional"))
      (node (ref "U18") (pin "H8") (pinfunction "VCC_H8_H8") (pintype "bidirectional"))
    )
    (net (code "159") (name "VDD_B_1V8") (class "Default")
      (node (ref "C14") (pin "1") (pinfunction "1_1") (pintype "bidirectional"))
      (node (ref "C16") (pin "1") (pinfunction "1_1") (pintype "bidirectional"))
      (node (ref "C26") (pin "1") (pinfunction "1_1") (pintype "bidirectional"))
      (node (ref "C32") (pin "1") (pinfunction "1_1") (pintype "bidirectional"))
      (node (ref "C33") (pin "1") (pinfunction "1_1") (pintype "bidirectional"))
      (node (ref "C34") (pin "1") (pinfunction "1_1") (pintype "bidirectional"))
      (node (ref "C35") (pin "1") (pinfunction "1_1") (pintype "bidirectional"))
      (node (ref "C36") (pin "1") (pinfunction "1_1") (pintype "bidirectional"))
      (node (ref "C41") (pin "1") (pinfunction "1_1") (pintype "bidirectional"))
      (node (ref "C44") (pin "1") (pinfunction "1_1") (pintype "bidirectional"))
      (node (ref "C59") (pin "1") (pinfunction "1_1") (pintype "bidirectional"))
      (node (ref "C60") (pin "1") (pinfunction "1_1") (pintype "bidirectional"))
      (node (ref "C61") (pin "1") (pinfunction "1_1") (pintype "bidirectional"))
      (node (ref "C62") (pin "1") (pinfunction "1_1") (pintype "bidirectional"))
      (node (ref "J7") (pin "2") (pinfunction "2_2") (pintype "bidirectional"))
      (node (ref "R24") (pin "1") (pinfunction "1_1") (pintype "bidirectional"))
      (node (ref "R25") (pin "1") (pinfunction "1_1") (pintype "bidirectional"))
      (node (ref "R26") (pin "2") (pinfunction "2_2") (pintype "bidirectional"))
      (node (ref "U10") (pin "1") (pinfunction "VIN_1") (pintype "bidirectional"))
      (node (ref "U12") (pin "1") (pinfunction "VIN_1") (pintype "bidirectional"))
      (node (ref "U16") (pin "3") (pinfunction "VCCA_3") (pintype "bidirectional"))
      (node (ref "U16") (pin "6") (pinfunction "OE_6") (pintype "bidirectional"))
      (node (ref "U18") (pin "D6") (pinfunction "VCCIO_0_D6_D6") (pintype "bidirectional"))
      (node (ref "U18") (pin "E4") (pinfunction "VCCIO_3_E4_E4") (pintype "bidirectional"))
      (node (ref "U18") (pin "F8") (pinfunction "VCCIO_1_F8_F8") (pintype "bidirectional"))
      (node (ref "U18") (pin "G4") (pinfunction "VCCIO_3_G4_G4") (pintype "bidirectional"))
      (node (ref "U18") (pin "H6") (pinfunction "VCCIO_2_H6_H6") (pintype "bidirectional"))
      (node (ref "U18") (pin "L11") (pinfunction "VCC_SPI_L11_L11") (pintype "bidirectional"))
      (node (ref "U19") (pin "3") (pinfunction "WP__3") (pintype "bidirectional"))
      (node (ref "U19") (pin "7") (pinfunction "HOLD__7") (pintype "bidirectional"))
      (node (ref "U19") (pin "8") (pinfunction "VCC_8") (pintype "bidirectional"))
      (node (ref "U20") (pin "5") (pinfunction "VDD_5") (pintype "bidirectional"))
      (node (ref "U23") (pin "A7") (pinfunction "VDDQ_A7_A7") (pintype "bidirectional"))
      (node (ref "U23") (pin "A9") (pinfunction "VDD_A9_A9") (pintype "bidirectional"))
      (node (ref "U23") (pin "B3") (pinfunction "VDDQ_B3_B3") (pintype "bidirectional"))
      (node (ref "U23") (pin "C7") (pinfunction "VDDQ_C7_C7") (pintype "bidirectional"))
      (node (ref "U23") (pin "D3") (pinfunction "VDDQ_D3_D3") (pintype "bidirectional"))
      (node (ref "U23") (pin "E7") (pinfunction "VDD_E7_E7") (pintype "bidirectional"))
      (node (ref "U23") (pin "J9") (pinfunction "VDD_J9_J9") (pintype "bidirectional"))
      (node (ref "X2") (pin "3") (pinfunction "VDD_3") (pintype "bidirectional"))
    )
    (net (code "160") (name "VDD_B_1V8_IMG_SD") (class "Default")
      (node (ref "C45") (pin "1") (pinfunction "1_1") (pintype "bidirectional"))
      (node (ref "C50") (pin "1") (pinfunction "1_1") (pintype "bidirectional"))
      (node (ref "C51") (pin "1") (pinfunction "1_1") (pintype "bidirectional"))
      (node (ref "C52") (pin "1") (pinfunction "1_1") (pintype "bidirectional"))
      (node (ref "C53") (pin "1") (pinfunction "1_1") (pintype "bidirectional"))
      (node (ref "C54") (pin "1") (pinfunction "1_1") (pintype "bidirectional"))
      (node (ref "C55") (pin "1") (pinfunction "1_1") (pintype "bidirectional"))
      (node (ref "C56") (pin "1") (pinfunction "1_1") (pintype "bidirectional"))
      (node (ref "R27") (pin "2") (pinfunction "2_2") (pintype "bidirectional"))
      (node (ref "R28") (pin "1") (pinfunction "1_1") (pintype "bidirectional"))
      (node (ref "R29") (pin "2") (pinfunction "2_2") (pintype "bidirectional"))
      (node (ref "R30") (pin "2") (pinfunction "2_2") (pintype "bidirectional"))
      (node (ref "R31") (pin "2") (pinfunction "2_2") (pintype "bidirectional"))
      (node (ref "R32") (pin "2") (pinfunction "2_2") (pintype "bidirectional"))
      (node (ref "R33") (pin "2") (pinfunction "2_2") (pintype "bidirectional"))
      (node (ref "U10") (pin "5") (pinfunction "QOD_5") (pintype "bidirectional"))
      (node (ref "U10") (pin "6") (pinfunction "VOUT_6") (pintype "bidirectional"))
      (node (ref "U21") (pin "1") (pinfunction "VDD_1") (pintype "bidirectional"))
      (node (ref "U21") (pin "5") (pinfunction "VDD_5") (pintype "bidirectional"))
      (node (ref "U22") (pin "A7") (pinfunction "VDD_IO_A7") (pintype "bidirectional"))
      (node (ref "U22") (pin "A8") (pinfunction "VDD_A8") (pintype "bidirectional"))
      (node (ref "U22") (pin "B1") (pinfunction "VDD_B1") (pintype "bidirectional"))
      (node (ref "U22") (pin "D2") (pinfunction "VDD_IO_D2") (pintype "bidirectional"))
      (node (ref "U22") (pin "D5") (pinfunction "VDD_IO_D5") (pintype "bidirectional"))
      (node (ref "U22") (pin "D6") (pinfunction "VDD_IO_D6") (pintype "bidirectional"))
      (node (ref "U22") (pin "E5") (pinfunction "VDD_IO_E5") (pintype "bidirectional"))
      (node (ref "U22") (pin "F6") (pinfunction "VDD_IO_F6") (pintype "bidirectional"))
      (node (ref "U22") (pin "G2") (pinfunction "VDD_G2") (pintype "bidirectional"))
      (node (ref "U22") (pin "G8") (pinfunction "VDD_G8") (pintype "bidirectional"))
      (node (ref "U22") (pin "H5") (pinfunction "VDD_IO_H5") (pintype "bidirectional"))
    )
    (net (code "161") (name "VDD_B_1V8_IMG_SD_EN") (class "Default")
      (node (ref "U10") (pin "3") (pinfunction "EN_3") (pintype "bidirectional"))
      (node (ref "U14") (pin "12") (pinfunction "PA.B/P2.3/TA1.2/UCB0STE/A5_12") (pintype "bidirectional"))
      (node (ref "U24") (pin "B2") (pinfunction "PE5_B2_B2") (pintype "bidirectional"))
    )
    (net (code "162") (name "VDD_B_1V8_STM") (class "Default")
      (node (ref "C24") (pin "1") (pinfunction "1_1") (pintype "bidirectional"))
      (node (ref "C65") (pin "1") (pinfunction "1_1") (pintype "bidirectional"))
      (node (ref "C68") (pin "1") (pinfunction "1_1") (pintype "bidirectional"))
      (node (ref "C69") (pin "1") (pinfunction "1_1") (pintype "bidirectional"))
      (node (ref "C70") (pin "1") (pinfunction "1_1") (pintype "bidirectional"))
      (node (ref "C71") (pin "1") (pinfunction "1_1") (pintype "bidirectional"))
      (node (ref "C72") (pin "1") (pinfunction "1_1") (pintype "bidirectional"))
      (node (ref "C73") (pin "1") (pinfunction "1_1") (pintype "bidirectional"))
      (node (ref "C74") (pin "1") (pinfunction "1_1") (pintype "bidirectional"))
      (node (ref "C75") (pin "1") (pinfunction "1_1") (pintype "bidirectional"))
      (node (ref "C78") (pin "1") (pinfunction "1_1") (pintype "bidirectional"))
      (node (ref "C79") (pin "1") (pinfunction "1_1") (pintype "bidirectional"))
      (node (ref "C80") (pin "1") (pinfunction "1_1") (pintype "bidirectional"))
      (node (ref "C81") (pin "1") (pinfunction "1_1") (pintype "bidirectional"))
      (node (ref "C82") (pin "1") (pinfunction "1_1") (pintype "bidirectional"))
      (node (ref "C83") (pin "1") (pinfunction "1_1") (pintype "bidirectional"))
      (node (ref "C86") (pin "1") (pinfunction "1_1") (pintype "bidirectional"))
      (node (ref "C87") (pin "1") (pinfunction "1_1") (pintype "bidirectional"))
      (node (ref "C88") (pin "1") (pinfunction "1_1") (pintype "bidirectional"))
      (node (ref "U12") (pin "5") (pinfunction "QOD_5") (pintype "bidirectional"))
      (node (ref "U12") (pin "6") (pinfunction "VOUT_6") (pintype "bidirectional"))
      (node (ref "U13") (pin "3") (pinfunction "EN_3") (pintype "bidirectional"))
      (node (ref "U15") (pin "3") (pinfunction "VCCA_3") (pintype "bidirectional"))
      (node (ref "U24") (pin "C1") (pinfunction "VBAT_C1_C1") (pintype "bidirectional"))
      (node (ref "U24") (pin "C5") (pinfunction "VDD_C5_C5") (pintype "bidirectional"))
      (node (ref "U24") (pin "C6") (pinfunction "PDR_ON_C6_C6") (pintype "bidirectional"))
      (node (ref "U24") (pin "C7") (pinfunction "VDD_C7_C7") (pintype "bidirectional"))
      (node (ref "U24") (pin "C8") (pinfunction "VDDSDMMC_C8_C8") (pintype "bidirectional"))
      (node (ref "U24") (pin "C9") (pinfunction "VDD_C9_C9") (pintype "bidirectional"))
      (node (ref "U24") (pin "F3") (pinfunction "VDD_F3_F3") (pintype "bidirectional"))
      (node (ref "U24") (pin "G13") (pinfunction "VDD_G13_G13") (pintype "bidirectional"))
      (node (ref "U24") (pin "G3") (pinfunction "VDD_G3_G3") (pintype "bidirectional"))
      (node (ref "U24") (pin "J12") (pinfunction "VDD_J12_J12") (pintype "bidirectional"))
      (node (ref "U24") (pin "J13") (pinfunction "VDD_J13_J13") (pintype "bidirectional"))
      (node (ref "U24") (pin "K4") (pinfunction "VDD_K4_K4") (pintype "bidirectional"))
      (node (ref "U24") (pin "N10") (pinfunction "VDD_N10_N10") (pintype "bidirectional"))
      (node (ref "U24") (pin "N8") (pinfunction "VDD_N8_N8") (pintype "bidirectional"))
      (node (ref "U24") (pin "N9") (pinfunction "VDD_N9_N9") (pintype "bidirectional"))
      (node (ref "U24") (pin "P1") (pinfunction "VREF+_P1_P1") (pintype "bidirectional"))
      (node (ref "U24") (pin "R1") (pinfunction "VDDA_R1_R1") (pintype "bidirectional"))
      (node (ref "X3") (pin "3") (pinfunction "VDD_3") (pintype "bidirectional"))
    )
    (net (code "163") (name "VDD_B_2V8") (class "Default")
      (node (ref "C15") (pin "1") (pinfunction "1_1") (pintype "bidirectional"))
      (node (ref "C37") (pin "1") (pinfunction "1_1") (pintype "bidirectional"))
      (node (ref "C38") (pin "1") (pinfunction "1_1") (pintype "bidirectional"))
      (node (ref "J8") (pin "2") (pinfunction "2_2") (pintype "bidirectional"))
      (node (ref "U11") (pin "1") (pinfunction "VIN_1") (pintype "bidirectional"))
      (node (ref "U18") (pin "C10") (pinfunction "VPP_2V5_C10_C10") (pintype "bidirectional"))
    )
    (net (code "164") (name "VDD_B_2V8_IMG_SD") (class "Default")
      (node (ref "C46") (pin "1") (pinfunction "1_1") (pintype "bidirectional"))
      (node (ref "C47") (pin "1") (pinfunction "1_1") (pintype "bidirectional"))
      (node (ref "C48") (pin "1") (pinfunction "1_1") (pintype "bidirectional"))
      (node (ref "C49") (pin "1") (pinfunction "1_1") (pintype "bidirectional"))
      (node (ref "C57") (pin "1") (pinfunction "1_1") (pintype "bidirectional"))
      (node (ref "C58") (pin "1") (pinfunction "1_1") (pintype "bidirectional"))
      (node (ref "C63") (pin "1") (pinfunction "1_1") (pintype "bidirectional"))
      (node (ref "C64") (pin "1") (pinfunction "1_1") (pintype "bidirectional"))
      (node (ref "J10") (pin "VDD") (pinfunction "VDD_VDD") (pintype "bidirectional"))
      (node (ref "U11") (pin "5") (pinfunction "QOD_5") (pintype "bidirectional"))
      (node (ref "U11") (pin "6") (pinfunction "VOUT_6") (pintype "bidirectional"))
      (node (ref "U22") (pin "A1") (pinfunction "VAA_A1") (pintype "bidirectional"))
      (node (ref "U22") (pin "A5") (pinfunction "VAA_PIX_A5") (pintype "bidirectional"))
      (node (ref "U22") (pin "A6") (pinfunction "VAA_A6") (pintype "bidirectional"))
      (node (ref "U22") (pin "F8") (pinfunction "VDD_PLL_F8") (pintype "bidirectional"))
      (node (ref "U22") (pin "H6") (pinfunction "VDD_MIPI_H6") (pintype "bidirectional"))
      (node (ref "U22") (pin "H8") (pinfunction "VDD_MIPI_H8") (pintype "bidirectional"))
    )
    (net (code "165") (name "VDD_B_2V8_IMG_SD_EN") (class "Default")
      (node (ref "U11") (pin "3") (pinfunction "EN_3") (pintype "bidirectional"))
      (node (ref "U14") (pin "15") (pinfunction "PA.6/P1.6/UCA0CLK/TA0CLK/TDI/TCLK_15") (pintype "bidirectional"))
      (node (ref "U24") (pin "A2") (pinfunction "PE2_A2_A2") (pintype "bidirectional"))
    )
    (net (code "166") (name "VDD_B_3V3_STM") (class "Default")
      (node (ref "C76") (pin "1") (pinfunction "1_1") (pintype "bidirectional"))
      (node (ref "C77") (pin "1") (pinfunction "1_1") (pintype "bidirectional"))
      (node (ref "U13") (pin "5") (pinfunction "QOD_5") (pintype "bidirectional"))
      (node (ref "U13") (pin "6") (pinfunction "VOUT_6") (pintype "bidirectional"))
      (node (ref "U24") (pin "H13") (pinfunction "VDDUSB_H13_H13") (pintype "bidirectional"))
    )
    (net (code "167") (name "VDD_B_EN") (class "Default")
      (node (ref "R4") (pin "1") (pinfunction "1_1") (pintype "bidirectional"))
      (node (ref "U14") (pin "20") (pinfunction "PA.2/P1.2/UCB0SIMO/UCB0SDA/SMCLK/A2/VEREF-_20") (pintype "bidirectional"))
      (node (ref "U3") (pin "6") (pinfunction "IN2_6") (pintype "bidirectional"))
    )
    (net (code "168") (name "VDD_USB") (class "Default")
      (node (ref "C1") (pin "1") (pinfunction "1_1") (pintype "bidirectional"))
      (node (ref "C5") (pin "1") (pinfunction "1_1") (pintype "bidirectional"))
      (node (ref "J1") (pin "2") (pinfunction "2_2") (pintype "bidirectional"))
      (node (ref "R1") (pin "1") (pinfunction "1_1") (pintype "bidirectional"))
      (node (ref "R2") (pin "1") (pinfunction "1_1") (pintype "bidirectional"))
      (node (ref "U1") (pin "3") (pinfunction "VIN1_3") (pintype "bidirectional"))
      (node (ref "U1") (pin "5") (pinfunction "MODE_5") (pintype "bidirectional"))
      (node (ref "U12") (pin "3") (pinfunction "EN_3") (pintype "bidirectional"))
      (node (ref "U3") (pin "1") (pinfunction "IN1_1") (pintype "bidirectional"))
      (node (ref "U4") (pin "4") (pinfunction "VDD_4") (pintype "bidirectional"))
      (node (ref "U5") (pin "6") (pinfunction "IN_6") (pintype "bidirectional"))
    )
    (net (code "169") (name "VDD_USB_IN") (class "Default")
      (node (ref "FB1") (pin "2") (pinfunction "P$2_2") (pintype "bidirectional"))
      (node (ref "H1") (pin "1") (pinfunction "1_1") (pintype "bidirectional"))
      (node (ref "J1") (pin "1") (pinfunction "1_1") (pintype "bidirectional"))
    )
    (net (code "170") (name "unconnected-(H1-Pad2)") (class "Default")
      (node (ref "H1") (pin "2") (pinfunction "2_2") (pintype "bidirectional"))
    )
    (net (code "171") (name "unconnected-(H1-Pad3)") (class "Default")
      (node (ref "H1") (pin "3") (pinfunction "3_3") (pintype "bidirectional"))
    )
    (net (code "172") (name "unconnected-(J10-PadDET)") (class "Default")
      (node (ref "J10") (pin "DET") (pinfunction "DET_DET") (pintype "bidirectional"))
    )
    (net (code "173") (name "unconnected-(J11-SBU1-PadA8)") (class "Default")
      (node (ref "J11") (pin "A8") (pinfunction "SBU1_A8") (pintype "bidirectional"))
    )
    (net (code "174") (name "unconnected-(J11-SBU2-PadB8)") (class "Default")
      (node (ref "J11") (pin "B8") (pinfunction "SBU2_B8") (pintype "bidirectional"))
    )
    (net (code "175") (name "unconnected-(U1-ST-Pad8)") (class "Default")
      (node (ref "U1") (pin "8") (pinfunction "ST_8") (pintype "bidirectional"))
    )
    (net (code "176") (name "unconnected-(U14B-PA.0{slash}P1.0{slash}UCB0STE{slash}A0{slash}VEREF+-Pad2)") (class "Default")
      (node (ref "U14") (pin "2") (pinfunction "PA.0/P1.0/UCB0STE/A0/VEREF+_2") (pintype "bidirectional"))
    )
    (net (code "177") (name "unconnected-(U14B-PA.1{slash}P1.1{slash}UCB0CLK{slash}ACLK{slash}A1{slash}VREF+-Pad1)") (class "Default")
      (node (ref "U14") (pin "1") (pinfunction "PA.1/P1.1/UCB0CLK/ACLK/A1/VREF+_1") (pintype "bidirectional"))
    )
    (net (code "178") (name "unconnected-(U14B-PA.4{slash}P1.4{slash}UCA0TXD{slash}UCA0SIMO{slash}TA0.1{slash}TCK-Pad17)") (class "Default")
      (node (ref "U14") (pin "17") (pinfunction "PA.4/P1.4/UCA0TXD/UCA0SIMO/TA0.1/TCK_17") (pintype "bidirectional"))
    )
    (net (code "179") (name "unconnected-(U14B-PA.5{slash}P1.5{slash}UCA0RXD{slash}UCA0SOMI{slash}TA0.2{slash}TMS-Pad16)") (class "Default")
      (node (ref "U14") (pin "16") (pinfunction "PA.5/P1.5/UCA0RXD/UCA0SOMI/TA0.2/TMS_16") (pintype "bidirectional"))
    )
    (net (code "180") (name "unconnected-(U14B-PA.7{slash}P1.7{slash}UCA0STE{slash}TDO-Pad14)") (class "Default")
      (node (ref "U14") (pin "14") (pinfunction "PA.7/P1.7/UCA0STE/TDO_14") (pintype "bidirectional"))
    )
    (net (code "181") (name "unconnected-(U18-PadC8)") (class "Default")
      (node (ref "U18") (pin "C8") (pinfunction "C8_C8") (pintype "bidirectional"))
    )
    (net (code "182") (name "unconnected-(U18-PadD9)") (class "Default")
      (node (ref "U18") (pin "D9") (pinfunction "D9_D9") (pintype "bidirectional"))
    )
    (net (code "183") (name "unconnected-(U18-PadE3)") (class "Default")
      (node (ref "U18") (pin "E3") (pinfunction "E3_E3") (pintype "bidirectional"))
    )
    (net (code "184") (name "unconnected-(U18-PadF3)") (class "Default")
      (node (ref "U18") (pin "F3") (pinfunction "F3_F3") (pintype "bidirectional"))
    )
    (net (code "185") (name "unconnected-(U18-PadF4)") (class "Default")
      (node (ref "U18") (pin "F4") (pinfunction "F4_F4") (pintype "bidirectional"))
    )
    (net (code "186") (name "unconnected-(U18-PadG3)") (class "Default")
      (node (ref "U18") (pin "G3") (pinfunction "G3_G3") (pintype "bidirectional"))
    )
    (net (code "187") (name "unconnected-(U18-PadH3)") (class "Default")
      (node (ref "U18") (pin "H3") (pinfunction "H3_H3") (pintype "bidirectional"))
    )
    (net (code "188") (name "unconnected-(U18-PadH7)") (class "Default")
      (node (ref "U18") (pin "H7") (pinfunction "H7_H7") (pintype "bidirectional"))
    )
    (net (code "189") (name "unconnected-(U18-PadH9)") (class "Default")
      (node (ref "U18") (pin "H9") (pinfunction "H9_H9") (pintype "bidirectional"))
    )
    (net (code "190") (name "unconnected-(U18-PadJ3)") (class "Default")
      (node (ref "U18") (pin "J3") (pinfunction "J3_J3") (pintype "bidirectional"))
    )
    (net (code "191") (name "unconnected-(U18-PadJ4)") (class "Default")
      (node (ref "U18") (pin "J4") (pinfunction "J4_J4") (pintype "bidirectional"))
    )
    (net (code "192") (name "unconnected-(U18-PadJ5)") (class "Default")
      (node (ref "U18") (pin "J5") (pinfunction "J5_J5") (pintype "bidirectional"))
    )
    (net (code "193") (name "unconnected-(U18-PadK1)") (class "Default")
      (node (ref "U18") (pin "K1") (pinfunction "K1_K1") (pintype "bidirectional"))
    )
    (net (code "194") (name "unconnected-(U18E-VPP_FAST_B10-PadB10)") (class "Default")
      (node (ref "U18") (pin "B10") (pinfunction "VPP_FAST_B10_B10") (pintype "bidirectional"))
    )
    (net (code "195") (name "unconnected-(U22A-VAAHV_NPIX-PadA2)") (class "Default")
      (node (ref "U22") (pin "A2") (pinfunction "VAAHV_NPIX_A2") (pintype "bidirectional"))
    )
    (net (code "196") (name "unconnected-(U22B-CLK_N-PadE7)") (class "Default")
      (node (ref "U22") (pin "E7") (pinfunction "CLK_N_E7") (pintype "bidirectional"))
    )
    (net (code "197") (name "unconnected-(U22B-CLK_P-PadF7)") (class "Default")
      (node (ref "U22") (pin "F7") (pinfunction "CLK_P_F7") (pintype "bidirectional"))
    )
    (net (code "198") (name "unconnected-(U22B-DATA2_N-PadG7)") (class "Default")
      (node (ref "U22") (pin "G7") (pinfunction "DATA2_N_G7") (pintype "bidirectional"))
    )
    (net (code "199") (name "unconnected-(U22B-DATA2_P-PadH7)") (class "Default")
      (node (ref "U22") (pin "H7") (pinfunction "DATA2_P_H7") (pintype "bidirectional"))
    )
    (net (code "200") (name "unconnected-(U22B-DATA_N-PadD8)") (class "Default")
      (node (ref "U22") (pin "D8") (pinfunction "DATA_N_D8") (pintype "bidirectional"))
    )
    (net (code "201") (name "unconnected-(U22B-DATA_P-PadE8)") (class "Default")
      (node (ref "U22") (pin "E8") (pinfunction "DATA_P_E8") (pintype "bidirectional"))
    )
    (net (code "202") (name "unconnected-(U22B-FLASH-PadC2)") (class "Default")
      (node (ref "U22") (pin "C2") (pinfunction "FLASH_C2") (pintype "bidirectional"))
    )
    (net (code "203") (name "unconnected-(U22B-SHUTTER-PadB8)") (class "Default")
      (node (ref "U22") (pin "B8") (pinfunction "SHUTTER_B8") (pintype "bidirectional"))
    )
    (net (code "204") (name "unconnected-(U22B-TRIGGER-PadC7)") (class "Default")
      (node (ref "U22") (pin "C7") (pinfunction "TRIGGER_C7") (pintype "bidirectional"))
    )
    (net (code "205") (name "unconnected-(U24A-PA0_N3-PadN3)") (class "Default")
      (node (ref "U24") (pin "N3") (pinfunction "PA0_N3_N3") (pintype "bidirectional"))
    )
    (net (code "206") (name "unconnected-(U24A-PA1_N2-PadN2)") (class "Default")
      (node (ref "U24") (pin "N2") (pinfunction "PA1_N2_N2") (pintype "bidirectional"))
    )
    (net (code "207") (name "unconnected-(U24A-PA2_P2-PadP2)") (class "Default")
      (node (ref "U24") (pin "P2") (pinfunction "PA2_P2_P2") (pintype "bidirectional"))
    )
    (net (code "208") (name "unconnected-(U24A-PA4_N4-PadN4)") (class "Default")
      (node (ref "U24") (pin "N4") (pinfunction "PA4_N4_N4") (pintype "bidirectional"))
    )
    (net (code "209") (name "unconnected-(U24A-PA5_P4-PadP4)") (class "Default")
      (node (ref "U24") (pin "P4") (pinfunction "PA5_P4_P4") (pintype "bidirectional"))
    )
    (net (code "210") (name "unconnected-(U24A-PA6_P3-PadP3)") (class "Default")
      (node (ref "U24") (pin "P3") (pinfunction "PA6_P3_P3") (pintype "bidirectional"))
    )
    (net (code "211") (name "unconnected-(U24A-PA7_R3-PadR3)") (class "Default")
      (node (ref "U24") (pin "R3") (pinfunction "PA7_R3_R3") (pintype "bidirectional"))
    )
    (net (code "212") (name "unconnected-(U24A-PA8_F15-PadF15)") (class "Default")
      (node (ref "U24") (pin "F15") (pinfunction "PA8_F15_F15") (pintype "bidirectional"))
    )
    (net (code "213") (name "unconnected-(U24A-PA9_E15-PadE15)") (class "Default")
      (node (ref "U24") (pin "E15") (pinfunction "PA9_E15_E15") (pintype "bidirectional"))
    )
    (net (code "214") (name "unconnected-(U24A-PA10_D15-PadD15)") (class "Default")
      (node (ref "U24") (pin "D15") (pinfunction "PA10_D15_D15") (pintype "bidirectional"))
    )
    (net (code "215") (name "unconnected-(U24A-PA11_C15-PadC15)") (class "Default")
      (node (ref "U24") (pin "C15") (pinfunction "PA11_C15_C15") (pintype "bidirectional"))
    )
    (net (code "216") (name "unconnected-(U24A-PA12_B15-PadB15)") (class "Default")
      (node (ref "U24") (pin "B15") (pinfunction "PA12_B15_B15") (pintype "bidirectional"))
    )
    (net (code "217") (name "unconnected-(U24A-PA15_A13-PadA13)") (class "Default")
      (node (ref "U24") (pin "A13") (pinfunction "PA15_A13_A13") (pintype "bidirectional"))
    )
    (net (code "218") (name "unconnected-(U24B-PB0_R5-PadR5)") (class "Default")
      (node (ref "U24") (pin "R5") (pinfunction "PB0_R5_R5") (pintype "bidirectional"))
    )
    (net (code "219") (name "unconnected-(U24B-PB3_A10-PadA10)") (class "Default")
      (node (ref "U24") (pin "A10") (pinfunction "PB3_A10_A10") (pintype "bidirectional"))
    )
    (net (code "220") (name "unconnected-(U24B-PB4_A9-PadA9)") (class "Default")
      (node (ref "U24") (pin "A9") (pinfunction "PB4_A9_A9") (pintype "bidirectional"))
    )
    (net (code "221") (name "unconnected-(U24B-PB5_A6-PadA6)") (class "Default")
      (node (ref "U24") (pin "A6") (pinfunction "PB5_A6_A6") (pintype "bidirectional"))
    )
    (net (code "222") (name "unconnected-(U24B-PB6_B6-PadB6)") (class "Default")
      (node (ref "U24") (pin "B6") (pinfunction "PB6_B6_B6") (pintype "bidirectional"))
    )
    (net (code "223") (name "unconnected-(U24B-PB7_B5-PadB5)") (class "Default")
      (node (ref "U24") (pin "B5") (pinfunction "PB7_B5_B5") (pintype "bidirectional"))
    )
    (net (code "224") (name "unconnected-(U24B-PB8_A5-PadA5)") (class "Default")
      (node (ref "U24") (pin "A5") (pinfunction "PB8_A5_A5") (pintype "bidirectional"))
    )
    (net (code "225") (name "unconnected-(U24B-PB9_B4-PadB4)") (class "Default")
      (node (ref "U24") (pin "B4") (pinfunction "PB9_B4_B4") (pintype "bidirectional"))
    )
    (net (code "226") (name "unconnected-(U24C-PC0_M2-PadM2)") (class "Default")
      (node (ref "U24") (pin "M2") (pinfunction "PC0_M2_M2") (pintype "bidirectional"))
    )
    (net (code "227") (name "unconnected-(U24C-PC1_M3-PadM3)") (class "Default")
      (node (ref "U24") (pin "M3") (pinfunction "PC1_M3_M3") (pintype "bidirectional"))
    )
    (net (code "228") (name "unconnected-(U24C-PC2_M4-PadM4)") (class "Default")
      (node (ref "U24") (pin "M4") (pinfunction "PC2_M4_M4") (pintype "bidirectional"))
    )
    (net (code "229") (name "unconnected-(U24C-PC3_M5-PadM5)") (class "Default")
      (node (ref "U24") (pin "M5") (pinfunction "PC3_M5_M5") (pintype "bidirectional"))
    )
    (net (code "230") (name "unconnected-(U24C-PC4_N5-PadN5)") (class "Default")
      (node (ref "U24") (pin "N5") (pinfunction "PC4_N5_N5") (pintype "bidirectional"))
    )
    (net (code "231") (name "unconnected-(U24C-PC5_P5-PadP5)") (class "Default")
      (node (ref "U24") (pin "P5") (pinfunction "PC5_P5_P5") (pintype "bidirectional"))
    )
    (net (code "232") (name "unconnected-(U24C-PC6_H15-PadH15)") (class "Default")
      (node (ref "U24") (pin "H15") (pinfunction "PC6_H15_H15") (pintype "bidirectional"))
    )
    (net (code "233") (name "unconnected-(U24C-PC7_G15-PadG15)") (class "Default")
      (node (ref "U24") (pin "G15") (pinfunction "PC7_G15_G15") (pintype "bidirectional"))
    )
    (net (code "234") (name "unconnected-(U24C-PC8_G14-PadG14)") (class "Default")
      (node (ref "U24") (pin "G14") (pinfunction "PC8_G14_G14") (pintype "bidirectional"))
    )
    (net (code "235") (name "unconnected-(U24C-PC9_F14-PadF14)") (class "Default")
      (node (ref "U24") (pin "F14") (pinfunction "PC9_F14_F14") (pintype "bidirectional"))
    )
    (net (code "236") (name "unconnected-(U24C-PC10_B14-PadB14)") (class "Default")
      (node (ref "U24") (pin "B14") (pinfunction "PC10_B14_B14") (pintype "bidirectional"))
    )
    (net (code "237") (name "unconnected-(U24C-PC11_B13-PadB13)") (class "Default")
      (node (ref "U24") (pin "B13") (pinfunction "PC11_B13_B13") (pintype "bidirectional"))
    )
    (net (code "238") (name "unconnected-(U24C-PC12_A12-PadA12)") (class "Default")
      (node (ref "U24") (pin "A12") (pinfunction "PC12_A12_A12") (pintype "bidirectional"))
    )
    (net (code "239") (name "unconnected-(U24C-PC13_D1-PadD1)") (class "Default")
      (node (ref "U24") (pin "D1") (pinfunction "PC13_D1_D1") (pintype "bidirectional"))
    )
    (net (code "240") (name "unconnected-(U24C-PC14_E1-PadE1)") (class "Default")
      (node (ref "U24") (pin "E1") (pinfunction "PC14_E1_E1") (pintype "bidirectional"))
    )
    (net (code "241") (name "unconnected-(U24C-PC15_F1-PadF1)") (class "Default")
      (node (ref "U24") (pin "F1") (pinfunction "PC15_F1_F1") (pintype "bidirectional"))
    )
    (net (code "242") (name "unconnected-(U24D-PD0_B12-PadB12)") (class "Default")
      (node (ref "U24") (pin "B12") (pinfunction "PD0_B12_B12") (pintype "bidirectional"))
    )
    (net (code "243") (name "unconnected-(U24D-PD1_C12-PadC12)") (class "Default")
      (node (ref "U24") (pin "C12") (pinfunction "PD1_C12_C12") (pintype "bidirectional"))
    )
    (net (code "244") (name "unconnected-(U24D-PD2_D12-PadD12)") (class "Default")
      (node (ref "U24") (pin "D12") (pinfunction "PD2_D12_D12") (pintype "bidirectional"))
    )
    (net (code "245") (name "unconnected-(U24D-PD3_D11-PadD11)") (class "Default")
      (node (ref "U24") (pin "D11") (pinfunction "PD3_D11_D11") (pintype "bidirectional"))
    )
    (net (code "246") (name "unconnected-(U24D-PD4_D10-PadD10)") (class "Default")
      (node (ref "U24") (pin "D10") (pinfunction "PD4_D10_D10") (pintype "bidirectional"))
    )
    (net (code "247") (name "unconnected-(U24D-PD5_C11-PadC11)") (class "Default")
      (node (ref "U24") (pin "C11") (pinfunction "PD5_C11_C11") (pintype "bidirectional"))
    )
    (net (code "248") (name "unconnected-(U24D-PD6_B11-PadB11)") (class "Default")
      (node (ref "U24") (pin "B11") (pinfunction "PD6_B11_B11") (pintype "bidirectional"))
    )
    (net (code "249") (name "unconnected-(U24D-PD7_A11-PadA11)") (class "Default")
      (node (ref "U24") (pin "A11") (pinfunction "PD7_A11_A11") (pintype "bidirectional"))
    )
    (net (code "250") (name "unconnected-(U24D-PD8_P15-PadP15)") (class "Default")
      (node (ref "U24") (pin "P15") (pinfunction "PD8_P15_P15") (pintype "bidirectional"))
    )
    (net (code "251") (name "unconnected-(U24D-PD9_P14-PadP14)") (class "Default")
      (node (ref "U24") (pin "P14") (pinfunction "PD9_P14_P14") (pintype "bidirectional"))
    )
    (net (code "252") (name "unconnected-(U24D-PD10_N15-PadN15)") (class "Default")
      (node (ref "U24") (pin "N15") (pinfunction "PD10_N15_N15") (pintype "bidirectional"))
    )
    (net (code "253") (name "unconnected-(U24D-PD11_N14-PadN14)") (class "Default")
      (node (ref "U24") (pin "N14") (pinfunction "PD11_N14_N14") (pintype "bidirectional"))
    )
    (net (code "254") (name "unconnected-(U24D-PD12_N13-PadN13)") (class "Default")
      (node (ref "U24") (pin "N13") (pinfunction "PD12_N13_N13") (pintype "bidirectional"))
    )
    (net (code "255") (name "unconnected-(U24D-PD13_M15-PadM15)") (class "Default")
      (node (ref "U24") (pin "M15") (pinfunction "PD13_M15_M15") (pintype "bidirectional"))
    )
    (net (code "256") (name "unconnected-(U24D-PD14_M14-PadM14)") (class "Default")
      (node (ref "U24") (pin "M14") (pinfunction "PD14_M14_M14") (pintype "bidirectional"))
    )
    (net (code "257") (name "unconnected-(U24D-PD15_L14-PadL14)") (class "Default")
      (node (ref "U24") (pin "L14") (pinfunction "PD15_L14_L14") (pintype "bidirectional"))
    )
    (net (code "258") (name "unconnected-(U24E-PE0_A4-PadA4)") (class "Default")
      (node (ref "U24") (pin "A4") (pinfunction "PE0_A4_A4") (pintype "bidirectional"))
    )
    (net (code "259") (name "unconnected-(U24E-PE1_A3-PadA3)") (class "Default")
      (node (ref "U24") (pin "A3") (pinfunction "PE1_A3_A3") (pintype "bidirectional"))
    )
    (net (code "260") (name "unconnected-(U24E-PE6_B3-PadB3)") (class "Default")
      (node (ref "U24") (pin "B3") (pinfunction "PE6_B3_B3") (pintype "bidirectional"))
    )
    (net (code "261") (name "unconnected-(U24E-PE11_P10-PadP10)") (class "Default")
      (node (ref "U24") (pin "P10") (pinfunction "PE11_P10_P10") (pintype "bidirectional"))
    )
    (net (code "262") (name "unconnected-(U24E-PE13_N11-PadN11)") (class "Default")
      (node (ref "U24") (pin "N11") (pinfunction "PE13_N11_N11") (pintype "bidirectional"))
    )
    (net (code "263") (name "unconnected-(U24E-PE14_P11-PadP11)") (class "Default")
      (node (ref "U24") (pin "P11") (pinfunction "PE14_P11_P11") (pintype "bidirectional"))
    )
    (net (code "264") (name "unconnected-(U24F-PF1_H3-PadH3)") (class "Default")
      (node (ref "U24") (pin "H3") (pinfunction "PF1_H3_H3") (pintype "bidirectional"))
    )
    (net (code "265") (name "unconnected-(U24F-PF2_H2-PadH2)") (class "Default")
      (node (ref "U24") (pin "H2") (pinfunction "PF2_H2_H2") (pintype "bidirectional"))
    )
    (net (code "266") (name "unconnected-(U24F-PF4_J3-PadJ3)") (class "Default")
      (node (ref "U24") (pin "J3") (pinfunction "PF4_J3_J3") (pintype "bidirectional"))
    )
    (net (code "267") (name "unconnected-(U24F-PF10_L1-PadL1)") (class "Default")
      (node (ref "U24") (pin "L1") (pinfunction "PF10_L1_L1") (pintype "bidirectional"))
    )
    (net (code "268") (name "unconnected-(U24F-PF12_P6-PadP6)") (class "Default")
      (node (ref "U24") (pin "P6") (pinfunction "PF12_P6_P6") (pintype "bidirectional"))
    )
    (net (code "269") (name "unconnected-(U24F-PF13_N6-PadN6)") (class "Default")
      (node (ref "U24") (pin "N6") (pinfunction "PF13_N6_N6") (pintype "bidirectional"))
    )
    (net (code "270") (name "unconnected-(U24F-PF14_R7-PadR7)") (class "Default")
      (node (ref "U24") (pin "R7") (pinfunction "PF14_R7_R7") (pintype "bidirectional"))
    )
    (net (code "271") (name "unconnected-(U24F-PF15_P7-PadP7)") (class "Default")
      (node (ref "U24") (pin "P7") (pinfunction "PF15_P7_P7") (pintype "bidirectional"))
    )
    (net (code "272") (name "unconnected-(U24G-PG0_N7-PadN7)") (class "Default")
      (node (ref "U24") (pin "N7") (pinfunction "PG0_N7_N7") (pintype "bidirectional"))
    )
    (net (code "273") (name "unconnected-(U24G-PG1_M7-PadM7)") (class "Default")
      (node (ref "U24") (pin "M7") (pinfunction "PG1_M7_M7") (pintype "bidirectional"))
    )
    (net (code "274") (name "unconnected-(U24G-PG2_L15-PadL15)") (class "Default")
      (node (ref "U24") (pin "L15") (pinfunction "PG2_L15_L15") (pintype "bidirectional"))
    )
    (net (code "275") (name "unconnected-(U24G-PG3_K15-PadK15)") (class "Default")
      (node (ref "U24") (pin "K15") (pinfunction "PG3_K15_K15") (pintype "bidirectional"))
    )
    (net (code "276") (name "unconnected-(U24G-PG4_K14-PadK14)") (class "Default")
      (node (ref "U24") (pin "K14") (pinfunction "PG4_K14_K14") (pintype "bidirectional"))
    )
    (net (code "277") (name "unconnected-(U24G-PG5_K13-PadK13)") (class "Default")
      (node (ref "U24") (pin "K13") (pinfunction "PG5_K13_K13") (pintype "bidirectional"))
    )
    (net (code "278") (name "unconnected-(U24G-PG8_H14-PadH14)") (class "Default")
      (node (ref "U24") (pin "H14") (pinfunction "PG8_H14_H14") (pintype "bidirectional"))
    )
    (net (code "279") (name "unconnected-(U24G-PG9_C10-PadC10)") (class "Default")
      (node (ref "U24") (pin "C10") (pinfunction "PG9_C10_C10") (pintype "bidirectional"))
    )
    (net (code "280") (name "unconnected-(U24G-PG10_B10-PadB10)") (class "Default")
      (node (ref "U24") (pin "B10") (pinfunction "PG10_B10_B10") (pintype "bidirectional"))
    )
    (net (code "281") (name "unconnected-(U24G-PG11_B9-PadB9)") (class "Default")
      (node (ref "U24") (pin "B9") (pinfunction "PG11_B9_B9") (pintype "bidirectional"))
    )
    (net (code "282") (name "unconnected-(U24G-PG12_B8-PadB8)") (class "Default")
      (node (ref "U24") (pin "B8") (pinfunction "PG12_B8_B8") (pintype "bidirectional"))
    )
    (net (code "283") (name "unconnected-(U24G-PG13_A8-PadA8)") (class "Default")
      (node (ref "U24") (pin "A8") (pinfunction "PG13_A8_A8") (pintype "bidirectional"))
    )
    (net (code "284") (name "unconnected-(U24G-PG14_A7-PadA7)") (class "Default")
      (node (ref "U24") (pin "A7") (pinfunction "PG14_A7_A7") (pintype "bidirectional"))
    )
    (net (code "285") (name "unconnected-(U24G-PG15_B7-PadB7)") (class "Default")
      (node (ref "U24") (pin "B7") (pinfunction "PG15_B7_B7") (pintype "bidirectional"))
    )
    (net (code "286") (name "unconnected-(U24H-PH1_H1-PadH1)") (class "Default")
      (node (ref "U24") (pin "H1") (pinfunction "PH1_H1_H1") (pintype "bidirectional"))
    )
    (net (code "287") (name "unconnected-(U24H-PH2_F4-PadF4)") (class "Default")
      (node (ref "U24") (pin "F4") (pinfunction "PH2_F4_F4") (pintype "bidirectional"))
    )
    (net (code "288") (name "unconnected-(U24H-PH3_G4-PadG4)") (class "Default")
      (node (ref "U24") (pin "G4") (pinfunction "PH3_G4_G4") (pintype "bidirectional"))
    )
    (net (code "289") (name "unconnected-(U24H-PH4_H4-PadH4)") (class "Default")
      (node (ref "U24") (pin "H4") (pinfunction "PH4_H4_H4") (pintype "bidirectional"))
    )
    (net (code "290") (name "unconnected-(U24H-PH5_J4-PadJ4)") (class "Default")
      (node (ref "U24") (pin "J4") (pinfunction "PH5_J4_J4") (pintype "bidirectional"))
    )
    (net (code "291") (name "unconnected-(U24H-PH6_M11-PadM11)") (class "Default")
      (node (ref "U24") (pin "M11") (pinfunction "PH6_M11_M11") (pintype "bidirectional"))
    )
    (net (code "292") (name "unconnected-(U24H-PH7_N12-PadN12)") (class "Default")
      (node (ref "U24") (pin "N12") (pinfunction "PH7_N12_N12") (pintype "bidirectional"))
    )
    (net (code "293") (name "unconnected-(U24H-PH8_M12-PadM12)") (class "Default")
      (node (ref "U24") (pin "M12") (pinfunction "PH8_M12_M12") (pintype "bidirectional"))
    )
    (net (code "294") (name "unconnected-(U24H-PH9_M13-PadM13)") (class "Default")
      (node (ref "U24") (pin "M13") (pinfunction "PH9_M13_M13") (pintype "bidirectional"))
    )
    (net (code "295") (name "unconnected-(U24H-PH10_L13-PadL13)") (class "Default")
      (node (ref "U24") (pin "L13") (pinfunction "PH10_L13_L13") (pintype "bidirectional"))
    )
    (net (code "296") (name "unconnected-(U24H-PH11_L12-PadL12)") (class "Default")
      (node (ref "U24") (pin "L12") (pinfunction "PH11_L12_L12") (pintype "bidirectional"))
    )
    (net (code "297") (name "unconnected-(U24H-PH12_K12-PadK12)") (class "Default")
      (node (ref "U24") (pin "K12") (pinfunction "PH12_K12_K12") (pintype "bidirectional"))
    )
    (net (code "298") (name "unconnected-(U24H-PH13_E12-PadE12)") (class "Default")
      (node (ref "U24") (pin "E12") (pinfunction "PH13_E12_E12") (pintype "bidirectional"))
    )
    (net (code "299") (name "unconnected-(U24H-PH14_E13-PadE13)") (class "Default")
      (node (ref "U24") (pin "E13") (pinfunction "PH14_E13_E13") (pintype "bidirectional"))
    )
    (net (code "300") (name "unconnected-(U24H-PH15_D13-PadD13)") (class "Default")
      (node (ref "U24") (pin "D13") (pinfunction "PH15_D13_D13") (pintype "bidirectional"))
    )
    (net (code "301") (name "unconnected-(U24I-PI0_E14-PadE14)") (class "Default")
      (node (ref "U24") (pin "E14") (pinfunction "PI0_E14_E14") (pintype "bidirectional"))
    )
    (net (code "302") (name "unconnected-(U24I-PI1_D14-PadD14)") (class "Default")
      (node (ref "U24") (pin "D14") (pinfunction "PI1_D14_D14") (pintype "bidirectional"))
    )
    (net (code "303") (name "unconnected-(U24I-PI2_C14-PadC14)") (class "Default")
      (node (ref "U24") (pin "C14") (pinfunction "PI2_C14_C14") (pintype "bidirectional"))
    )
    (net (code "304") (name "unconnected-(U24I-PI3_C13-PadC13)") (class "Default")
      (node (ref "U24") (pin "C13") (pinfunction "PI3_C13_C13") (pintype "bidirectional"))
    )
    (net (code "305") (name "unconnected-(U24I-PI4_D4-PadD4)") (class "Default")
      (node (ref "U24") (pin "D4") (pinfunction "PI4_D4_D4") (pintype "bidirectional"))
    )
    (net (code "306") (name "unconnected-(U24I-PI5_C4-PadC4)") (class "Default")
      (node (ref "U24") (pin "C4") (pinfunction "PI5_C4_C4") (pintype "bidirectional"))
    )
    (net (code "307") (name "unconnected-(U24I-PI6_C3-PadC3)") (class "Default")
      (node (ref "U24") (pin "C3") (pinfunction "PI6_C3_C3") (pintype "bidirectional"))
    )
    (net (code "308") (name "unconnected-(U24I-PI7_C2-PadC2)") (class "Default")
      (node (ref "U24") (pin "C2") (pinfunction "PI7_C2_C2") (pintype "bidirectional"))
    )
    (net (code "309") (name "unconnected-(U24I-PI9_D3-PadD3)") (class "Default")
      (node (ref "U24") (pin "D3") (pinfunction "PI9_D3_D3") (pintype "bidirectional"))
    )
    (net (code "310") (name "unconnected-(U24I-PI10_E3-PadE3)") (class "Default")
      (node (ref "U24") (pin "E3") (pinfunction "PI10_E3_E3") (pintype "bidirectional"))
    )
    (net (code "311") (name "unconnected-(U24I-PI11_E4-PadE4)") (class "Default")
      (node (ref "U24") (pin "E4") (pinfunction "PI11_E4_E4") (pintype "bidirectional"))
    )
  )
)
